# Allwinner_A13_SCH.net
KiCad netlist of a schematic drawn in Altium Designer
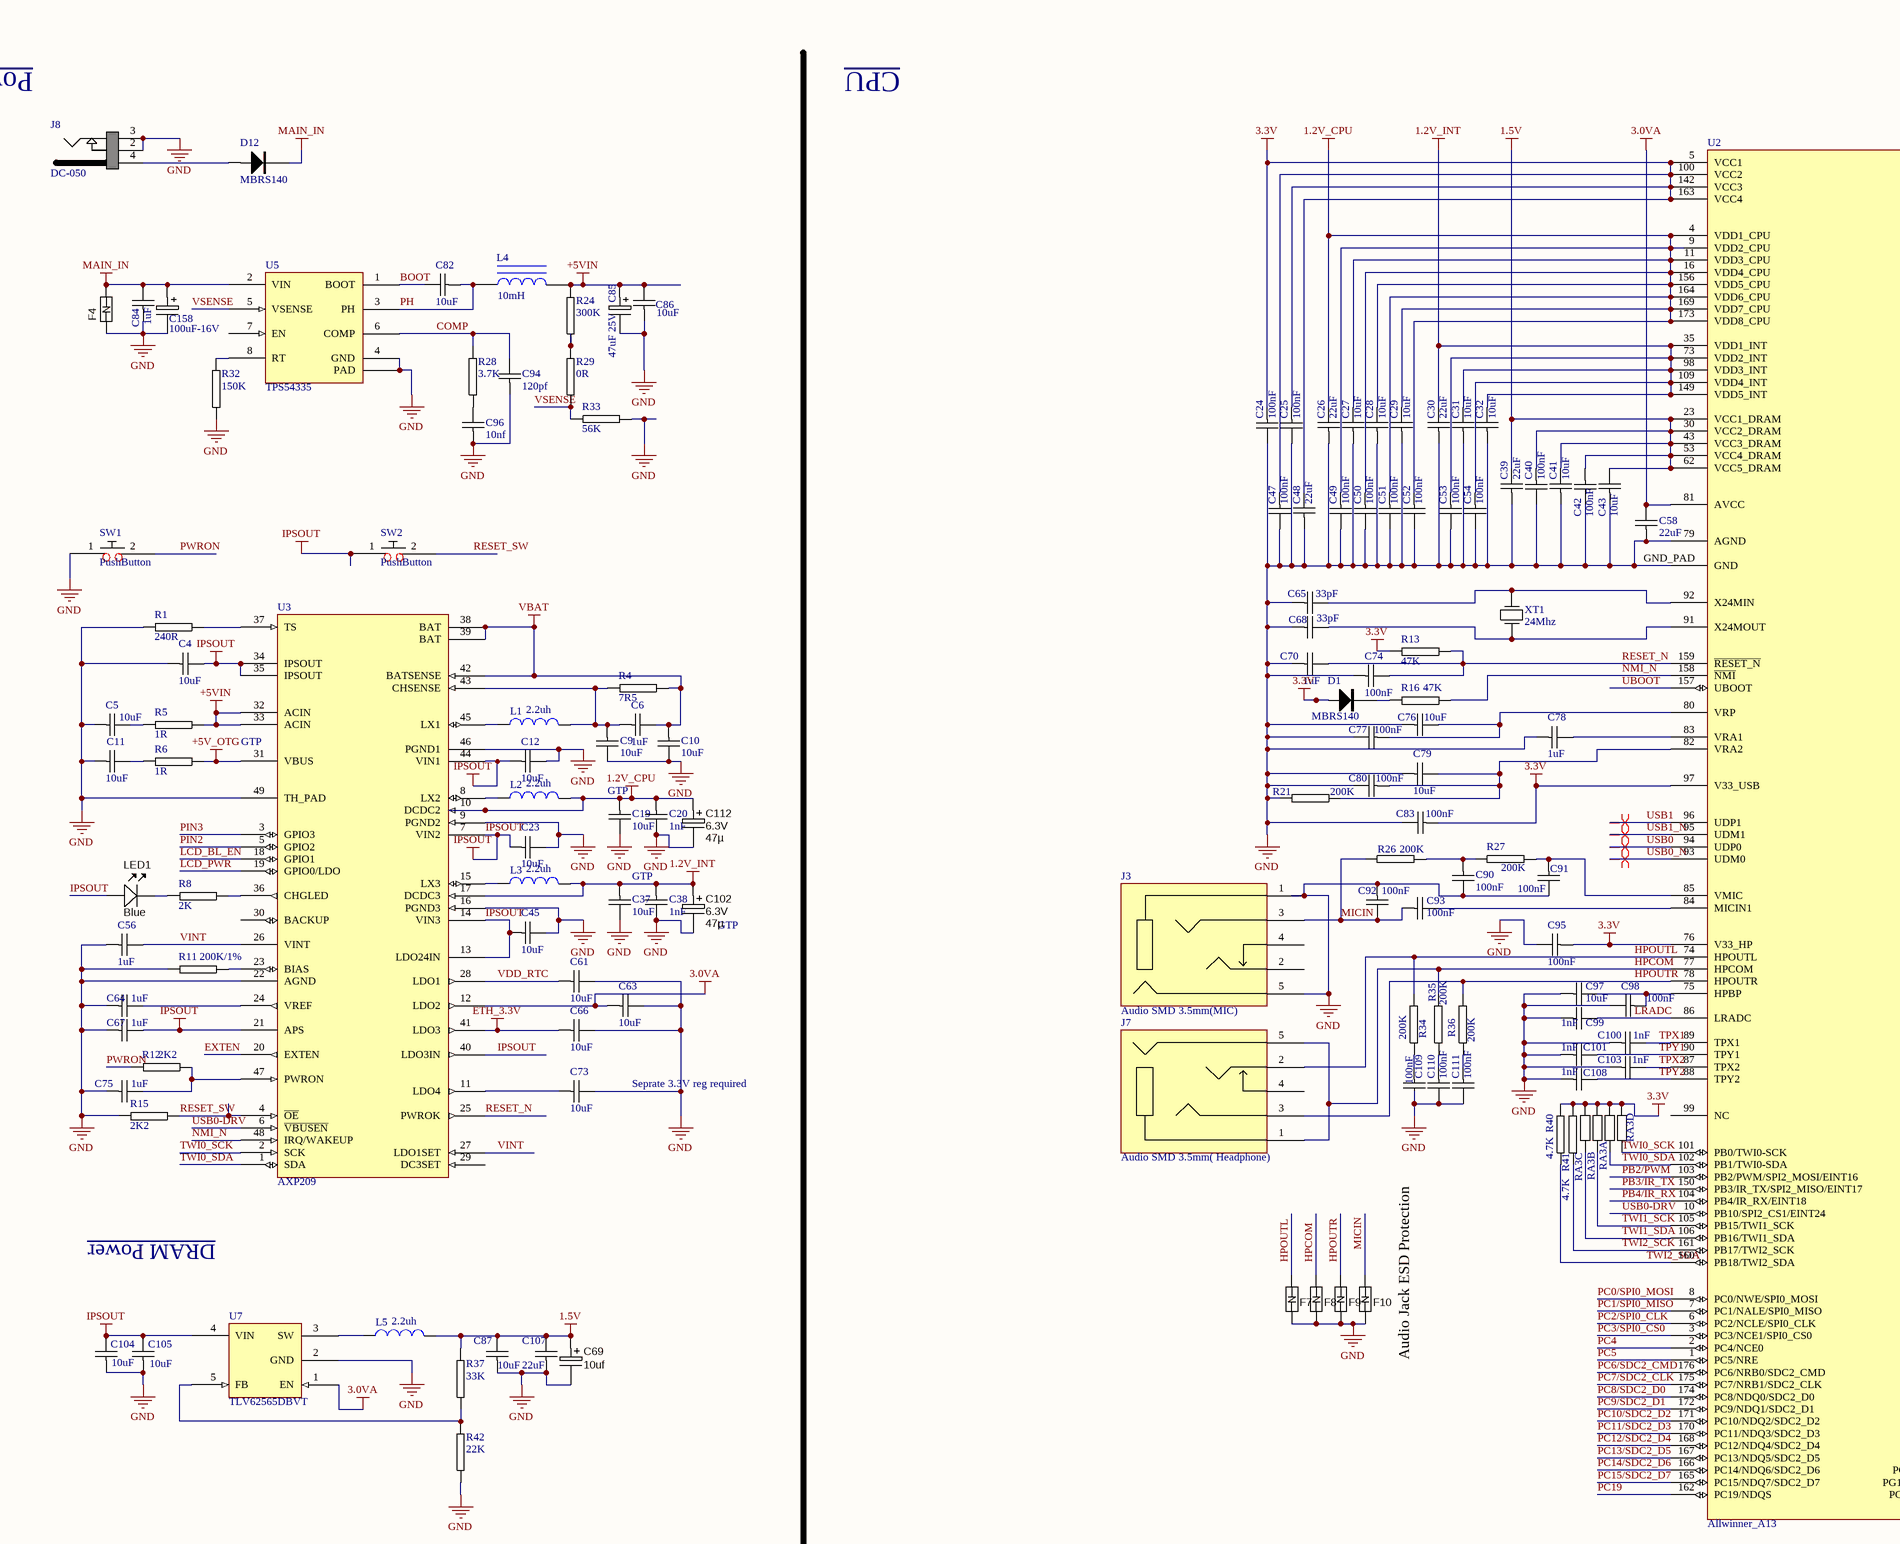
[diagram p0: Allwinner_A13_SCH.SchDoc, top left]
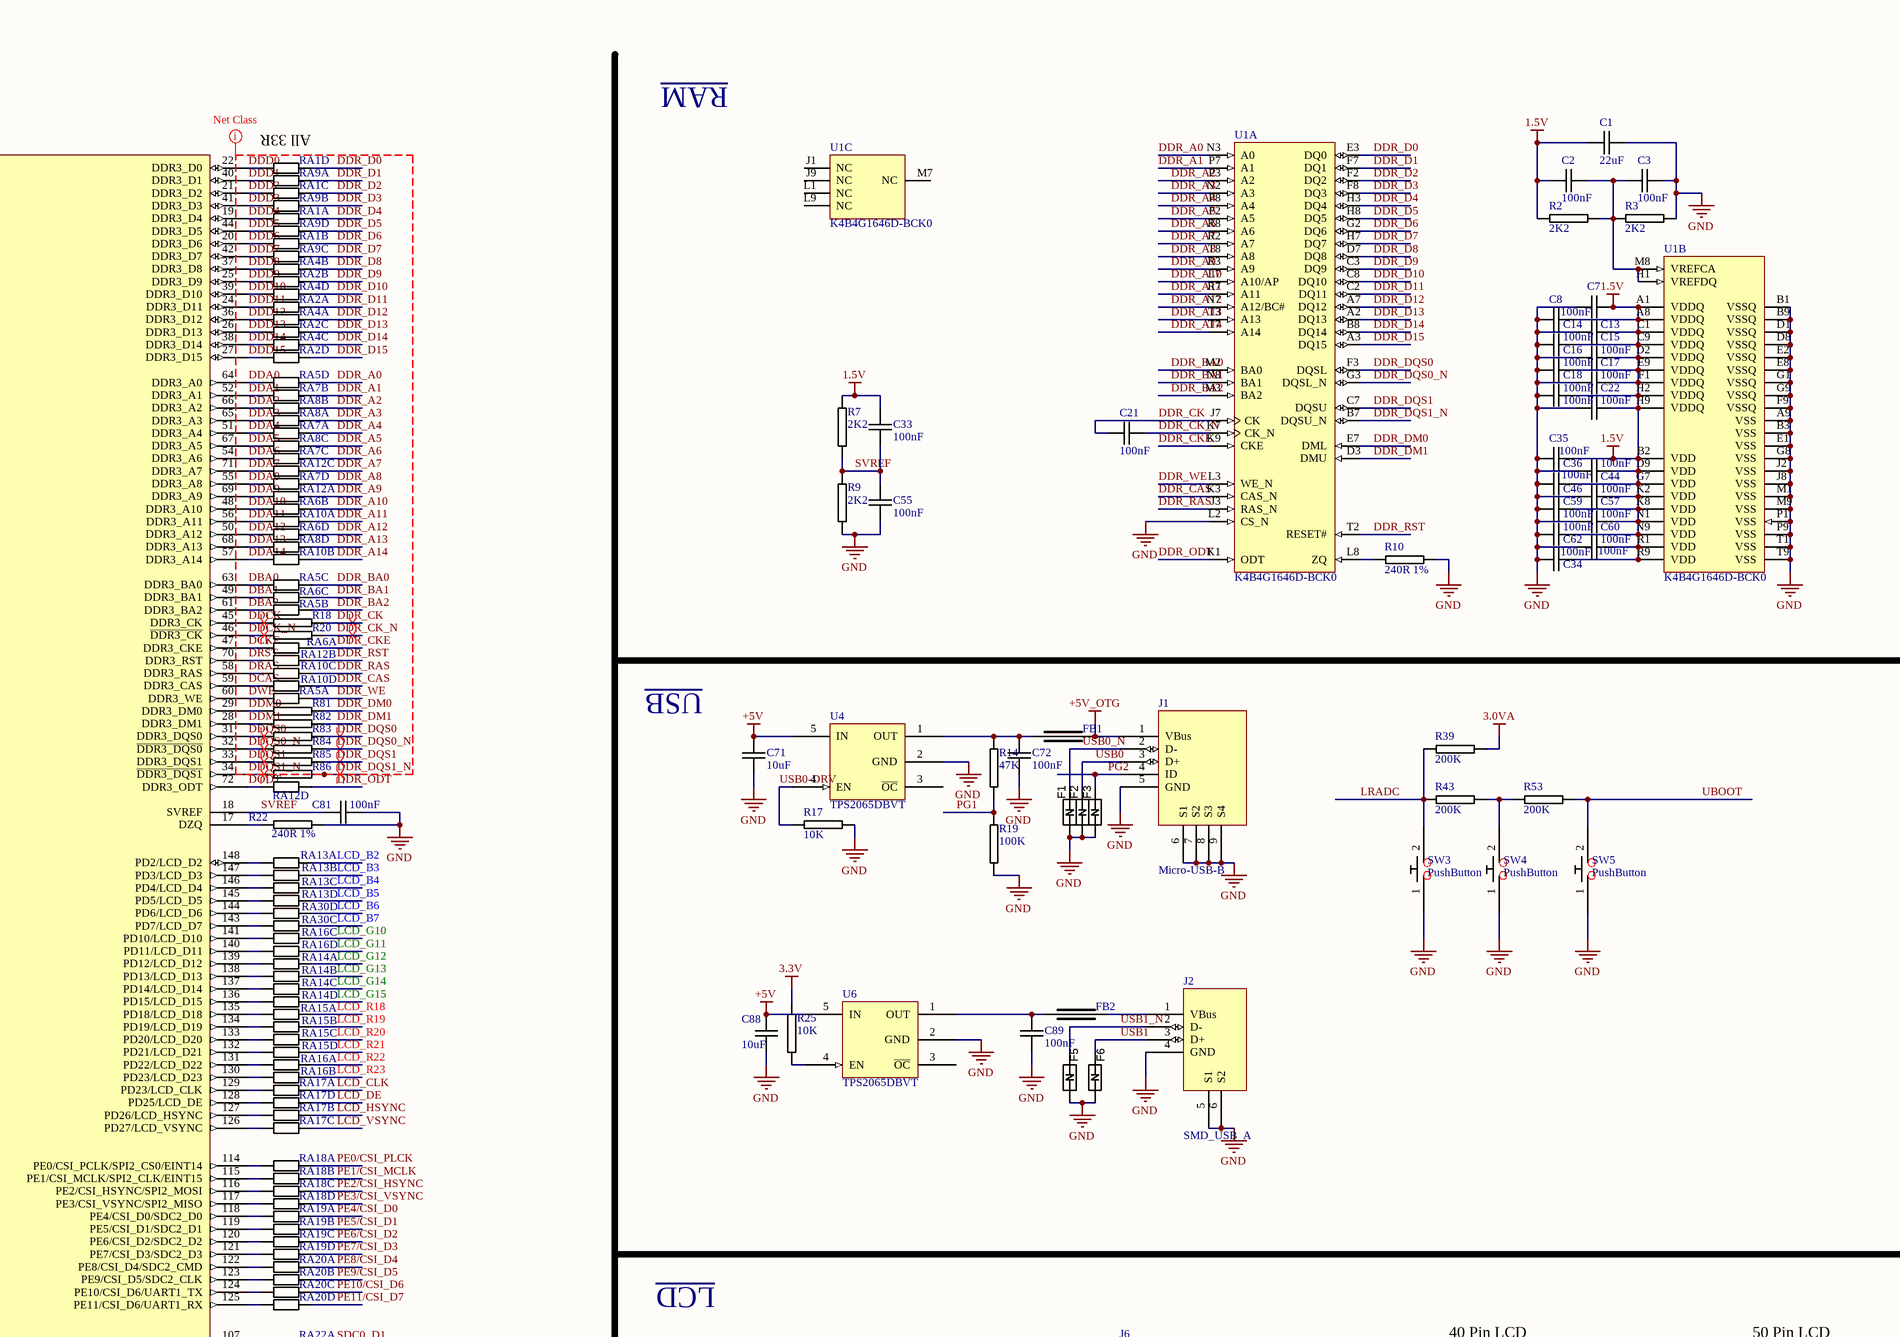
[diagram p1: Allwinner_A13_SCH.SchDoc, top right]
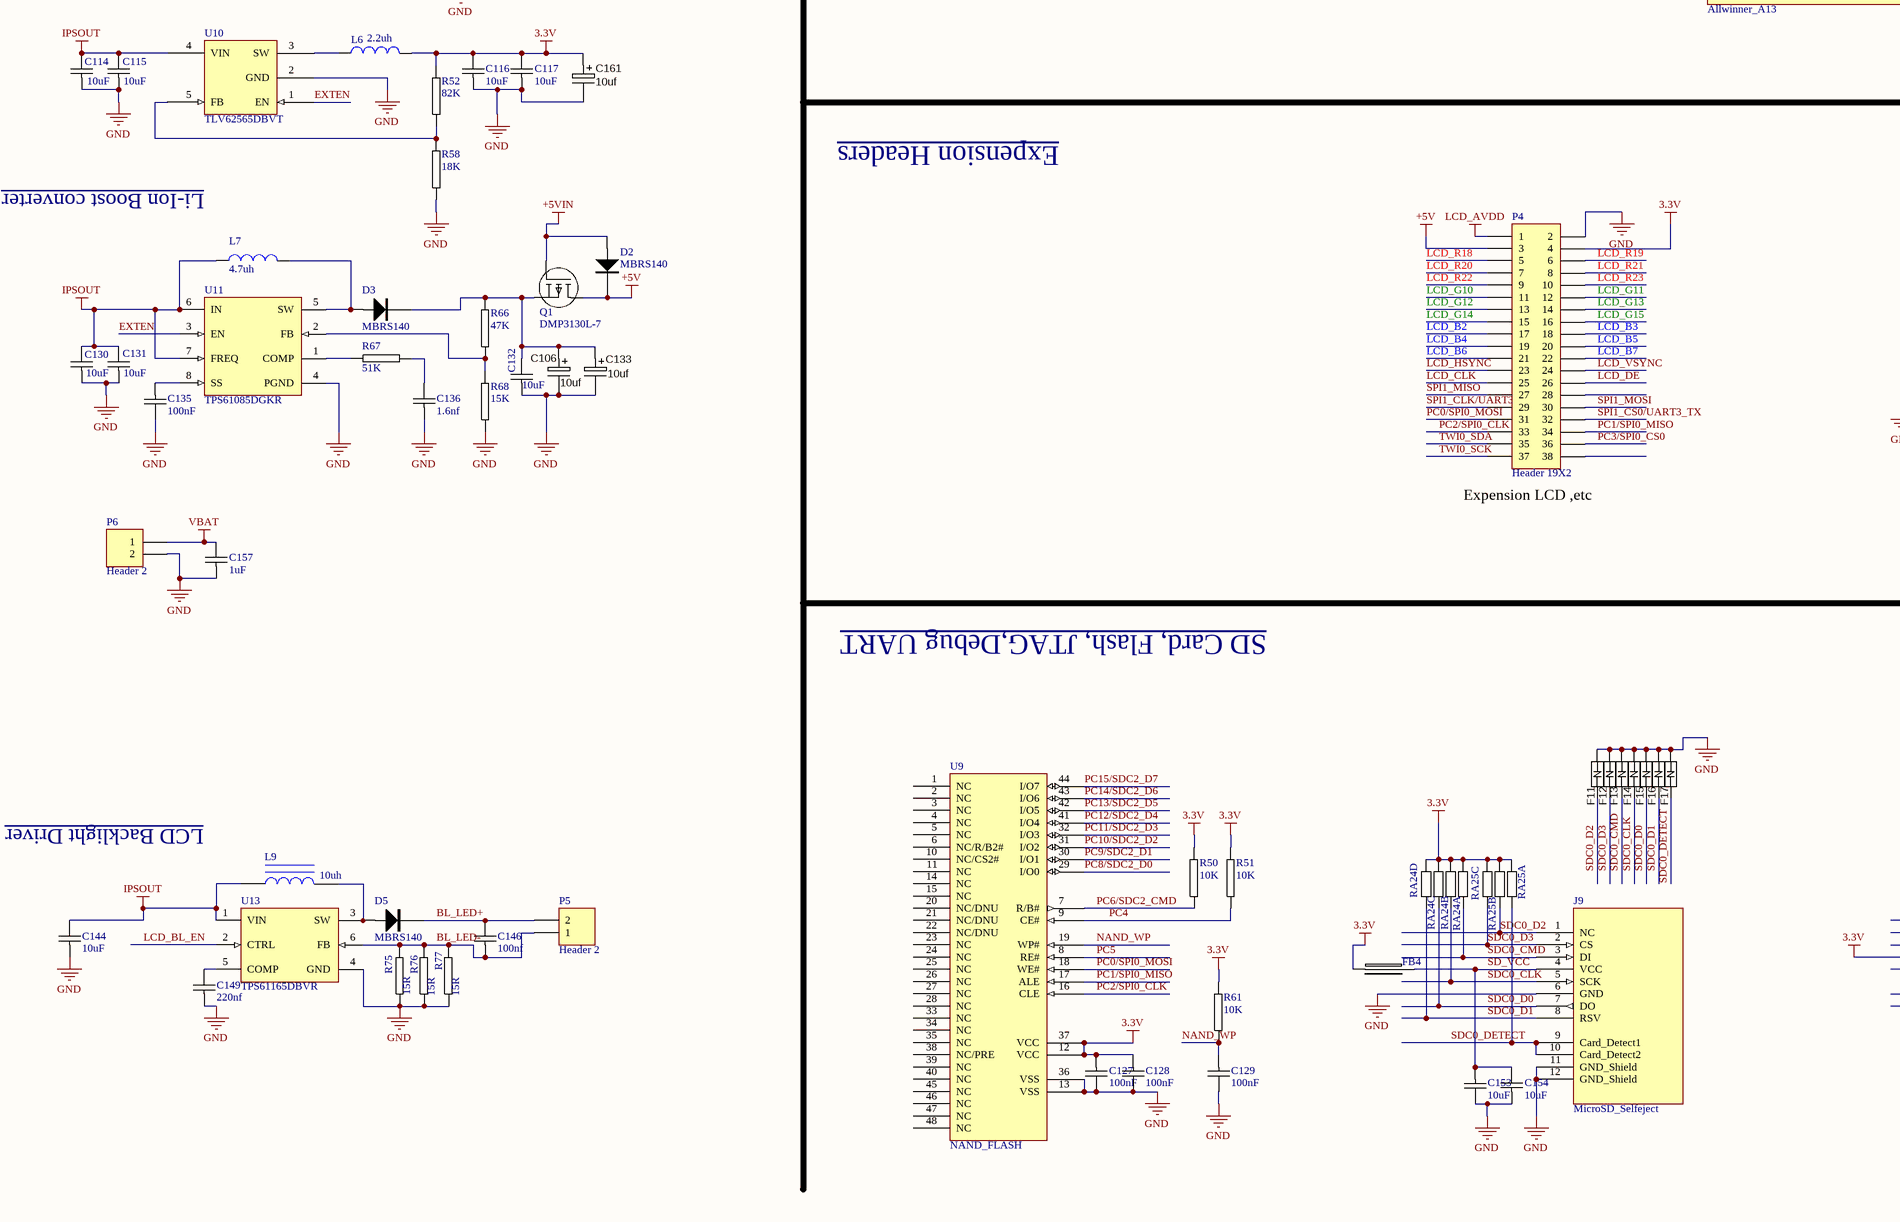
[diagram p2: Allwinner_A13_SCH.SchDoc, bottom left]
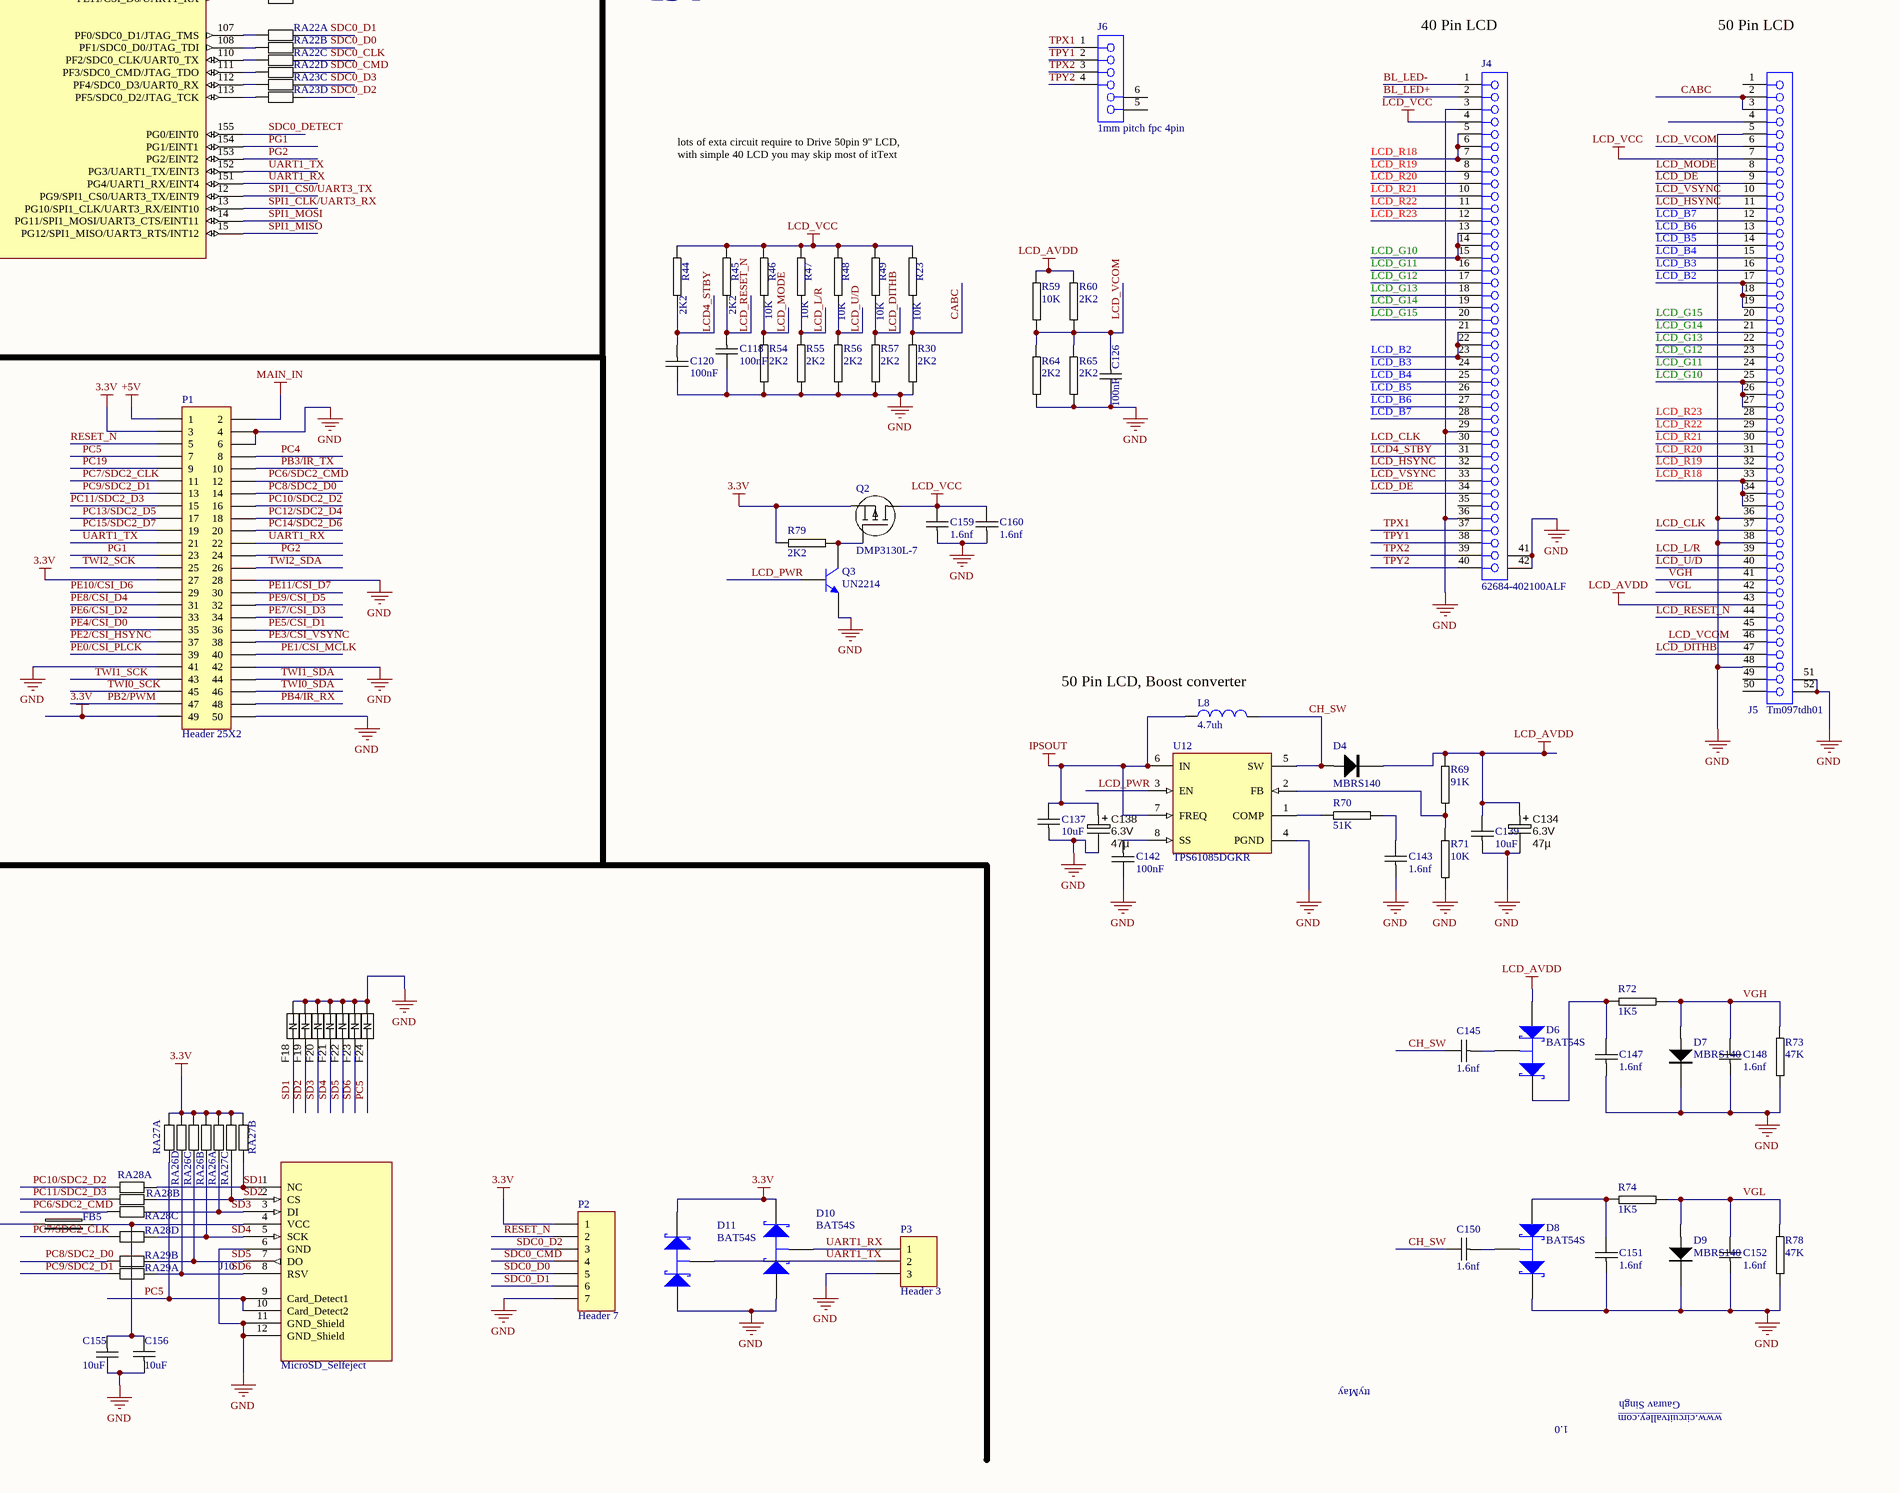
[diagram p3: Allwinner_A13_SCH.SchDoc, bottom right]

(export (version "E")
  (design (tool "Eeschema 10.0.6"))
  (components
    (comp (ref "C1")
      (value "22uF")
      (footprint "0603C-GENERIC")
      (description "CAPACITOR 0603 CERAMIC")
      (fields
        (field (name "MANUFACTURER") "Murata Electronics North America")
        (field (name "MANUFACTURER PART NUMBER") "GRM188R60J106ME47D")
      )
      (libsource (lib "Generic") (part "0603C-10UF-6V3-X5R-MUR"))
    )
    (comp (ref "C2")
      (value "100nF")
      (footprint "0603C-GENERIC")
      (description "CAPACITOR 0603 CERAMIC")
      (fields
        (field (name "MANUFACTURER") "Murata Electronics North America")
        (field (name "MANUFACTURER PART NUMBER") "GRM188R60J106ME47D")
      )
      (libsource (lib "Generic") (part "0603C-10UF-6V3-X5R-MUR"))
    )
    (comp (ref "C3")
      (value "100nF")
      (footprint "0603C-GENERIC")
      (description "CAPACITOR 0603 CERAMIC")
      (fields
        (field (name "MANUFACTURER") "Murata Electronics North America")
        (field (name "MANUFACTURER PART NUMBER") "GRM188R60J106ME47D")
      )
      (libsource (lib "Generic") (part "0603C-10UF-6V3-X5R-MUR"))
    )
    (comp (ref "C4")
      (value "10uF")
      (footprint "0603C-GENERIC")
      (description "CAPACITOR 0603 CERAMIC")
      (fields
        (field (name "MANUFACTURER") "Murata Electronics North America")
        (field (name "MANUFACTURER PART NUMBER") "GRM188R60J106ME47D")
      )
      (libsource (lib "Generic") (part "0603C-10UF-6V3-X5R-MUR"))
    )
    (comp (ref "C5")
      (value "10uF")
      (footprint "0603C-GENERIC")
      (description "CAPACITOR 0603 CERAMIC")
      (fields
        (field (name "MANUFACTURER") "Murata Electronics North America")
        (field (name "MANUFACTURER PART NUMBER") "GRM188R60J106ME47D")
      )
      (libsource (lib "Generic") (part "0603C-10UF-6V3-X5R-MUR"))
    )
    (comp (ref "C6")
      (value "1uF")
      (footprint "0603C-GENERIC")
      (description "CAPACITOR 0603 CERAMIC")
      (libsource (lib "Generic") (part "0603C-1UF-25V-X5R-SAM"))
    )
    (comp (ref "C7")
      (value "100nF")
      (footprint "0603C-GENERIC")
      (description "CAPACITOR 0603 CERAMIC")
      (fields
        (field (name "MANUFACTURER") "Murata Electronics North America")
        (field (name "MANUFACTURER PART NUMBER") "GRM188R60J106ME47D")
      )
      (libsource (lib "Generic") (part "0603C-10UF-6V3-X5R-MUR"))
    )
    (comp (ref "C8")
      (value "100nF")
      (footprint "0603C-GENERIC")
      (description "CAPACITOR 0603 CERAMIC")
      (fields
        (field (name "MANUFACTURER") "Murata Electronics North America")
        (field (name "MANUFACTURER PART NUMBER") "GRM188R60J106ME47D")
      )
      (libsource (lib "Generic") (part "0603C-10UF-6V3-X5R-MUR"))
    )
    (comp (ref "C9")
      (value "10uF")
      (footprint "0603C-GENERIC")
      (description "CAPACITOR 0603 CERAMIC")
      (fields
        (field (name "MANUFACTURER") "Murata Electronics North America")
        (field (name "MANUFACTURER PART NUMBER") "GRM188R60J106ME47D")
      )
      (libsource (lib "Generic") (part "0603C-10UF-6V3-X5R-MUR"))
    )
    (comp (ref "C10")
      (value "10uF")
      (footprint "0603C-GENERIC")
      (description "CAPACITOR 0603 CERAMIC")
      (fields
        (field (name "MANUFACTURER") "Murata Electronics North America")
        (field (name "MANUFACTURER PART NUMBER") "GRM188R60J106ME47D")
      )
      (libsource (lib "Generic") (part "0603C-10UF-6V3-X5R-MUR"))
    )
    (comp (ref "C11")
      (value "10uF")
      (footprint "0603C-GENERIC")
      (description "CAPACITOR 0603 CERAMIC")
      (fields
        (field (name "MANUFACTURER") "Murata Electronics North America")
        (field (name "MANUFACTURER PART NUMBER") "GRM188R60J106ME47D")
      )
      (libsource (lib "Generic") (part "0603C-10UF-6V3-X5R-MUR"))
    )
    (comp (ref "C12")
      (value "10uF")
      (footprint "0603C-GENERIC")
      (description "CAPACITOR 0603 CERAMIC")
      (fields
        (field (name "MANUFACTURER") "Murata Electronics North America")
        (field (name "MANUFACTURER PART NUMBER") "GRM188R60J106ME47D")
      )
      (libsource (lib "Generic") (part "0603C-10UF-6V3-X5R-MUR"))
    )
    (comp (ref "C13")
      (value "100nF")
      (footprint "0603C-GENERIC")
      (description "CAPACITOR 0603 CERAMIC")
      (fields
        (field (name "MANUFACTURER") "Murata Electronics North America")
        (field (name "MANUFACTURER PART NUMBER") "GRM188R60J106ME47D")
      )
      (libsource (lib "Generic") (part "0603C-10UF-6V3-X5R-MUR"))
    )
    (comp (ref "C14")
      (value "100nF")
      (footprint "0603C-GENERIC")
      (description "CAPACITOR 0603 CERAMIC")
      (fields
        (field (name "MANUFACTURER") "Murata Electronics North America")
        (field (name "MANUFACTURER PART NUMBER") "GRM188R60J106ME47D")
      )
      (libsource (lib "Generic") (part "0603C-10UF-6V3-X5R-MUR"))
    )
    (comp (ref "C15")
      (value "100nF")
      (footprint "0603C-GENERIC")
      (description "CAPACITOR 0603 CERAMIC")
      (fields
        (field (name "MANUFACTURER") "Murata Electronics North America")
        (field (name "MANUFACTURER PART NUMBER") "GRM188R60J106ME47D")
      )
      (libsource (lib "Generic") (part "0603C-10UF-6V3-X5R-MUR"))
    )
    (comp (ref "C16")
      (value "100nF")
      (footprint "0603C-GENERIC")
      (description "CAPACITOR 0603 CERAMIC")
      (fields
        (field (name "MANUFACTURER") "Murata Electronics North America")
        (field (name "MANUFACTURER PART NUMBER") "GRM188R60J106ME47D")
      )
      (libsource (lib "Generic") (part "0603C-10UF-6V3-X5R-MUR"))
    )
    (comp (ref "C17")
      (value "100nF")
      (footprint "0603C-GENERIC")
      (description "CAPACITOR 0603 CERAMIC")
      (fields
        (field (name "MANUFACTURER") "Murata Electronics North America")
        (field (name "MANUFACTURER PART NUMBER") "GRM188R60J106ME47D")
      )
      (libsource (lib "Generic") (part "0603C-10UF-6V3-X5R-MUR"))
    )
    (comp (ref "C18")
      (value "100nF")
      (footprint "0603C-GENERIC")
      (description "CAPACITOR 0603 CERAMIC")
      (fields
        (field (name "MANUFACTURER") "Murata Electronics North America")
        (field (name "MANUFACTURER PART NUMBER") "GRM188R60J106ME47D")
      )
      (libsource (lib "Generic") (part "0603C-10UF-6V3-X5R-MUR"))
    )
    (comp (ref "C19")
      (value "10uF")
      (footprint "0603C-GENERIC")
      (description "CAPACITOR 0603 CERAMIC")
      (fields
        (field (name "MANUFACTURER") "Murata Electronics North America")
        (field (name "MANUFACTURER PART NUMBER") "GRM188R60J106ME47D")
      )
      (libsource (lib "Generic") (part "0603C-10UF-6V3-X5R-MUR"))
    )
    (comp (ref "C20")
      (value "1nF")
      (footprint "0603C-GENERIC")
      (description "CAPACITOR 0603 CERAMIC")
      (libsource (lib "Generic") (part "0603C-1NF-50V-X7R-KEM"))
    )
    (comp (ref "C21")
      (value "100nF")
      (footprint "0603C-GENERIC")
      (description "CAPACITOR 0603 CERAMIC")
      (fields
        (field (name "MANUFACTURER") "Murata Electronics North America")
        (field (name "MANUFACTURER PART NUMBER") "GRM188R60J106ME47D")
      )
      (libsource (lib "Generic") (part "0603C-10UF-6V3-X5R-MUR"))
    )
    (comp (ref "C22")
      (value "100nF")
      (footprint "0603C-GENERIC")
      (description "CAPACITOR 0603 CERAMIC")
      (fields
        (field (name "MANUFACTURER") "Murata Electronics North America")
        (field (name "MANUFACTURER PART NUMBER") "GRM188R60J106ME47D")
      )
      (libsource (lib "Generic") (part "0603C-10UF-6V3-X5R-MUR"))
    )
    (comp (ref "C23")
      (value "10uF")
      (footprint "0603C-GENERIC")
      (description "CAPACITOR 0603 CERAMIC")
      (fields
        (field (name "MANUFACTURER") "Murata Electronics North America")
        (field (name "MANUFACTURER PART NUMBER") "GRM188R60J106ME47D")
      )
      (libsource (lib "Generic") (part "0603C-10UF-6V3-X5R-MUR"))
    )
    (comp (ref "C24")
      (value "100nF")
      (footprint "0603C-GENERIC")
      (description "CAPACITOR 0603 CERAMIC")
      (fields
        (field (name "MANUFACTURER PART NUMBER") "C1608X7R1E104K")
        (field (name "MANUFACTURER") "TDK Corporation")
      )
      (libsource (lib "Generic") (part "0603C-100NF-25V-X7R-TDK"))
    )
    (comp (ref "C25")
      (value "100nF")
      (footprint "0603C-GENERIC")
      (description "CAPACITOR 0603 CERAMIC")
      (fields
        (field (name "MANUFACTURER PART NUMBER") "C1608X7R1E104K")
        (field (name "MANUFACTURER") "TDK Corporation")
      )
      (libsource (lib "Generic") (part "0603C-100NF-25V-X7R-TDK"))
    )
    (comp (ref "C26")
      (value "22uF")
      (footprint "0603C-GENERIC")
      (description "CAPACITOR 0603 CERAMIC")
      (fields
        (field (name "MANUFACTURER") "Murata Electronics North America")
        (field (name "MANUFACTURER PART NUMBER") "GRM188R60J106ME47D")
      )
      (libsource (lib "Generic") (part "0603C-10UF-6V3-X5R-MUR"))
    )
    (comp (ref "C27")
      (value "10uF")
      (footprint "0603C-GENERIC")
      (description "CAPACITOR 0603 CERAMIC")
      (fields
        (field (name "MANUFACTURER") "Murata Electronics North America")
        (field (name "MANUFACTURER PART NUMBER") "GRM188R60J106ME47D")
      )
      (libsource (lib "Generic") (part "0603C-10UF-6V3-X5R-MUR"))
    )
    (comp (ref "C28")
      (value "10uF")
      (footprint "0603C-GENERIC")
      (description "CAPACITOR 0603 CERAMIC")
      (fields
        (field (name "MANUFACTURER") "Murata Electronics North America")
        (field (name "MANUFACTURER PART NUMBER") "GRM188R60J106ME47D")
      )
      (libsource (lib "Generic") (part "0603C-10UF-6V3-X5R-MUR"))
    )
    (comp (ref "C29")
      (value "10uF")
      (footprint "0603C-GENERIC")
      (description "CAPACITOR 0603 CERAMIC")
      (fields
        (field (name "MANUFACTURER") "Murata Electronics North America")
        (field (name "MANUFACTURER PART NUMBER") "GRM188R60J106ME47D")
      )
      (libsource (lib "Generic") (part "0603C-10UF-6V3-X5R-MUR"))
    )
    (comp (ref "C30")
      (value "22uF")
      (footprint "0603C-GENERIC")
      (description "CAPACITOR 0603 CERAMIC")
      (fields
        (field (name "MANUFACTURER") "Murata Electronics North America")
        (field (name "MANUFACTURER PART NUMBER") "GRM188R60J106ME47D")
      )
      (libsource (lib "Generic") (part "0603C-10UF-6V3-X5R-MUR"))
    )
    (comp (ref "C31")
      (value "10uF")
      (footprint "0603C-GENERIC")
      (description "CAPACITOR 0603 CERAMIC")
      (fields
        (field (name "MANUFACTURER") "Murata Electronics North America")
        (field (name "MANUFACTURER PART NUMBER") "GRM188R60J106ME47D")
      )
      (libsource (lib "Generic") (part "0603C-10UF-6V3-X5R-MUR"))
    )
    (comp (ref "C32")
      (value "10uF")
      (footprint "0603C-GENERIC")
      (description "CAPACITOR 0603 CERAMIC")
      (fields
        (field (name "MANUFACTURER") "Murata Electronics North America")
        (field (name "MANUFACTURER PART NUMBER") "GRM188R60J106ME47D")
      )
      (libsource (lib "Generic") (part "0603C-10UF-6V3-X5R-MUR"))
    )
    (comp (ref "C33")
      (value "100nF")
      (footprint "0603C-GENERIC")
      (description "CAPACITOR 0603 CERAMIC")
      (fields
        (field (name "MANUFACTURER") "Murata Electronics North America")
        (field (name "MANUFACTURER PART NUMBER") "GRM188R60J106ME47D")
      )
      (libsource (lib "Generic") (part "0603C-10UF-6V3-X5R-MUR"))
    )
    (comp (ref "C34")
      (value "100nF")
      (footprint "0603C-GENERIC")
      (description "CAPACITOR 0603 CERAMIC")
      (fields
        (field (name "MANUFACTURER") "Murata Electronics North America")
        (field (name "MANUFACTURER PART NUMBER") "GRM188R60J106ME47D")
      )
      (libsource (lib "Generic") (part "0603C-10UF-6V3-X5R-MUR"))
    )
    (comp (ref "C35")
      (value "100nF")
      (footprint "0603C-GENERIC")
      (description "CAPACITOR 0603 CERAMIC")
      (fields
        (field (name "MANUFACTURER") "Murata Electronics North America")
        (field (name "MANUFACTURER PART NUMBER") "GRM188R60J106ME47D")
      )
      (libsource (lib "Generic") (part "0603C-10UF-6V3-X5R-MUR"))
    )
    (comp (ref "C36")
      (value "100nF")
      (footprint "0603C-GENERIC")
      (description "CAPACITOR 0603 CERAMIC")
      (fields
        (field (name "MANUFACTURER") "Murata Electronics North America")
        (field (name "MANUFACTURER PART NUMBER") "GRM188R60J106ME47D")
      )
      (libsource (lib "Generic") (part "0603C-10UF-6V3-X5R-MUR"))
    )
    (comp (ref "C37")
      (value "10uF")
      (footprint "0603C-GENERIC")
      (description "CAPACITOR 0603 CERAMIC")
      (fields
        (field (name "MANUFACTURER") "Murata Electronics North America")
        (field (name "MANUFACTURER PART NUMBER") "GRM188R60J106ME47D")
      )
      (libsource (lib "Generic") (part "0603C-10UF-6V3-X5R-MUR"))
    )
    (comp (ref "C38")
      (value "1nF")
      (footprint "0603C-GENERIC")
      (description "CAPACITOR 0603 CERAMIC")
      (libsource (lib "Generic") (part "0603C-1NF-50V-X7R-KEM"))
    )
    (comp (ref "C39")
      (value "22uF")
      (footprint "0603C-GENERIC")
      (description "CAPACITOR 0603 CERAMIC")
      (fields
        (field (name "MANUFACTURER") "Murata Electronics North America")
        (field (name "MANUFACTURER PART NUMBER") "GRM188R60J106ME47D")
      )
      (libsource (lib "Generic") (part "0603C-10UF-6V3-X5R-MUR"))
    )
    (comp (ref "C40")
      (value "100nF")
      (footprint "0603C-GENERIC")
      (description "CAPACITOR 0603 CERAMIC")
      (fields
        (field (name "MANUFACTURER PART NUMBER") "C1608X7R1E104K")
        (field (name "MANUFACTURER") "TDK Corporation")
      )
      (libsource (lib "Generic") (part "0603C-100NF-25V-X7R-TDK"))
    )
    (comp (ref "C41")
      (value "10uF")
      (footprint "0603C-GENERIC")
      (description "CAPACITOR 0603 CERAMIC")
      (fields
        (field (name "MANUFACTURER") "Murata Electronics North America")
        (field (name "MANUFACTURER PART NUMBER") "GRM188R60J106ME47D")
      )
      (libsource (lib "Generic") (part "0603C-10UF-6V3-X5R-MUR"))
    )
    (comp (ref "C42")
      (value "100nF")
      (footprint "0603C-GENERIC")
      (description "CAPACITOR 0603 CERAMIC")
      (fields
        (field (name "MANUFACTURER PART NUMBER") "C1608X7R1E104K")
        (field (name "MANUFACTURER") "TDK Corporation")
      )
      (libsource (lib "Generic") (part "0603C-100NF-25V-X7R-TDK"))
    )
    (comp (ref "C43")
      (value "10uF")
      (footprint "0603C-GENERIC")
      (description "CAPACITOR 0603 CERAMIC")
      (fields
        (field (name "MANUFACTURER") "Murata Electronics North America")
        (field (name "MANUFACTURER PART NUMBER") "GRM188R60J106ME47D")
      )
      (libsource (lib "Generic") (part "0603C-10UF-6V3-X5R-MUR"))
    )
    (comp (ref "C44")
      (value "100nF")
      (footprint "0603C-GENERIC")
      (description "CAPACITOR 0603 CERAMIC")
      (fields
        (field (name "MANUFACTURER") "Murata Electronics North America")
        (field (name "MANUFACTURER PART NUMBER") "GRM188R60J106ME47D")
      )
      (libsource (lib "Generic") (part "0603C-10UF-6V3-X5R-MUR"))
    )
    (comp (ref "C45")
      (value "10uF")
      (footprint "0603C-GENERIC")
      (description "CAPACITOR 0603 CERAMIC")
      (fields
        (field (name "MANUFACTURER") "Murata Electronics North America")
        (field (name "MANUFACTURER PART NUMBER") "GRM188R60J106ME47D")
      )
      (libsource (lib "Generic") (part "0603C-10UF-6V3-X5R-MUR"))
    )
    (comp (ref "C46")
      (value "100nF")
      (footprint "0603C-GENERIC")
      (description "CAPACITOR 0603 CERAMIC")
      (fields
        (field (name "MANUFACTURER") "Murata Electronics North America")
        (field (name "MANUFACTURER PART NUMBER") "GRM188R60J106ME47D")
      )
      (libsource (lib "Generic") (part "0603C-10UF-6V3-X5R-MUR"))
    )
    (comp (ref "C47")
      (value "100nF")
      (footprint "0603C-GENERIC")
      (description "CAPACITOR 0603 CERAMIC")
      (fields
        (field (name "MANUFACTURER PART NUMBER") "C1608X7R1E104K")
        (field (name "MANUFACTURER") "TDK Corporation")
      )
      (libsource (lib "Generic") (part "0603C-100NF-25V-X7R-TDK"))
    )
    (comp (ref "C48")
      (value "22uF")
      (footprint "0603C-GENERIC")
      (description "CAPACITOR 0603 CERAMIC")
      (fields
        (field (name "MANUFACTURER") "Murata Electronics North America")
        (field (name "MANUFACTURER PART NUMBER") "GRM188R60J106ME47D")
      )
      (libsource (lib "Generic") (part "0603C-10UF-6V3-X5R-MUR"))
    )
    (comp (ref "C49")
      (value "100nF")
      (footprint "0603C-GENERIC")
      (description "CAPACITOR 0603 CERAMIC")
      (fields
        (field (name "MANUFACTURER PART NUMBER") "C1608X7R1E104K")
        (field (name "MANUFACTURER") "TDK Corporation")
      )
      (libsource (lib "Generic") (part "0603C-100NF-25V-X7R-TDK"))
    )
    (comp (ref "C50")
      (value "100nF")
      (footprint "0603C-GENERIC")
      (description "CAPACITOR 0603 CERAMIC")
      (fields
        (field (name "MANUFACTURER PART NUMBER") "C1608X7R1E104K")
        (field (name "MANUFACTURER") "TDK Corporation")
      )
      (libsource (lib "Generic") (part "0603C-100NF-25V-X7R-TDK"))
    )
    (comp (ref "C51")
      (value "100nF")
      (footprint "0603C-GENERIC")
      (description "CAPACITOR 0603 CERAMIC")
      (fields
        (field (name "MANUFACTURER PART NUMBER") "C1608X7R1E104K")
        (field (name "MANUFACTURER") "TDK Corporation")
      )
      (libsource (lib "Generic") (part "0603C-100NF-25V-X7R-TDK"))
    )
    (comp (ref "C52")
      (value "100nF")
      (footprint "0603C-GENERIC")
      (description "CAPACITOR 0603 CERAMIC")
      (fields
        (field (name "MANUFACTURER PART NUMBER") "C1608X7R1E104K")
        (field (name "MANUFACTURER") "TDK Corporation")
      )
      (libsource (lib "Generic") (part "0603C-100NF-25V-X7R-TDK"))
    )
    (comp (ref "C53")
      (value "100nF")
      (footprint "0603C-GENERIC")
      (description "CAPACITOR 0603 CERAMIC")
      (fields
        (field (name "MANUFACTURER PART NUMBER") "C1608X7R1E104K")
        (field (name "MANUFACTURER") "TDK Corporation")
      )
      (libsource (lib "Generic") (part "0603C-100NF-25V-X7R-TDK"))
    )
    (comp (ref "C54")
      (value "100nF")
      (footprint "0603C-GENERIC")
      (description "CAPACITOR 0603 CERAMIC")
      (fields
        (field (name "MANUFACTURER PART NUMBER") "C1608X7R1E104K")
        (field (name "MANUFACTURER") "TDK Corporation")
      )
      (libsource (lib "Generic") (part "0603C-100NF-25V-X7R-TDK"))
    )
    (comp (ref "C55")
      (value "100nF")
      (footprint "0603C-GENERIC")
      (description "CAPACITOR 0603 CERAMIC")
      (fields
        (field (name "MANUFACTURER") "Murata Electronics North America")
        (field (name "MANUFACTURER PART NUMBER") "GRM188R60J106ME47D")
      )
      (libsource (lib "Generic") (part "0603C-10UF-6V3-X5R-MUR"))
    )
    (comp (ref "C56")
      (value "1uF")
      (footprint "0603C-GENERIC")
      (description "CAPACITOR 0603 CERAMIC")
      (libsource (lib "Generic") (part "0603C-1UF-25V-X5R-SAM"))
    )
    (comp (ref "C57")
      (value "100nF")
      (footprint "0603C-GENERIC")
      (description "CAPACITOR 0603 CERAMIC")
      (fields
        (field (name "MANUFACTURER") "Murata Electronics North America")
        (field (name "MANUFACTURER PART NUMBER") "GRM188R60J106ME47D")
      )
      (libsource (lib "Generic") (part "0603C-10UF-6V3-X5R-MUR"))
    )
    (comp (ref "C58")
      (value "22uF")
      (footprint "0603C-GENERIC")
      (description "CAPACITOR 0603 CERAMIC")
      (fields
        (field (name "MANUFACTURER") "Murata Electronics North America")
        (field (name "MANUFACTURER PART NUMBER") "GRM188R60J106ME47D")
      )
      (libsource (lib "Generic") (part "0603C-10UF-6V3-X5R-MUR"))
    )
    (comp (ref "C59")
      (value "100nF")
      (footprint "0603C-GENERIC")
      (description "CAPACITOR 0603 CERAMIC")
      (fields
        (field (name "MANUFACTURER") "Murata Electronics North America")
        (field (name "MANUFACTURER PART NUMBER") "GRM188R60J106ME47D")
      )
      (libsource (lib "Generic") (part "0603C-10UF-6V3-X5R-MUR"))
    )
    (comp (ref "C60")
      (value "100nF")
      (footprint "0603C-GENERIC")
      (description "CAPACITOR 0603 CERAMIC")
      (fields
        (field (name "MANUFACTURER") "Murata Electronics North America")
        (field (name "MANUFACTURER PART NUMBER") "GRM188R60J106ME47D")
      )
      (libsource (lib "Generic") (part "0603C-10UF-6V3-X5R-MUR"))
    )
    (comp (ref "C61")
      (value "10uF")
      (footprint "0603C-GENERIC")
      (description "CAPACITOR 0603 CERAMIC")
      (fields
        (field (name "MANUFACTURER") "Murata Electronics North America")
        (field (name "MANUFACTURER PART NUMBER") "GRM188R60J106ME47D")
      )
      (libsource (lib "Generic") (part "0603C-10UF-6V3-X5R-MUR"))
    )
    (comp (ref "C62")
      (value "100nF")
      (footprint "0603C-GENERIC")
      (description "CAPACITOR 0603 CERAMIC")
      (fields
        (field (name "MANUFACTURER") "Murata Electronics North America")
        (field (name "MANUFACTURER PART NUMBER") "GRM188R60J106ME47D")
      )
      (libsource (lib "Generic") (part "0603C-10UF-6V3-X5R-MUR"))
    )
    (comp (ref "C63")
      (value "10uF")
      (footprint "0603C-GENERIC")
      (description "CAPACITOR 0603 CERAMIC")
      (fields
        (field (name "MANUFACTURER") "Murata Electronics North America")
        (field (name "MANUFACTURER PART NUMBER") "GRM188R60J106ME47D")
      )
      (libsource (lib "Generic") (part "0603C-10UF-6V3-X5R-MUR"))
    )
    (comp (ref "C64")
      (value "1uF")
      (footprint "0603C-GENERIC")
      (description "CAPACITOR 0603 CERAMIC")
      (libsource (lib "Generic") (part "0603C-1UF-25V-X5R-SAM"))
    )
    (comp (ref "C65")
      (value "33pF")
      (footprint "0603C-GENERIC")
      (description "CAPACITOR 0603 CERAMIC")
      (libsource (lib "Generic") (part "0603C-33PF-50V-C0G-PAN"))
    )
    (comp (ref "C66")
      (value "10uF")
      (footprint "0603C-GENERIC")
      (description "CAPACITOR 0603 CERAMIC")
      (fields
        (field (name "MANUFACTURER") "Murata Electronics North America")
        (field (name "MANUFACTURER PART NUMBER") "GRM188R60J106ME47D")
      )
      (libsource (lib "Generic") (part "0603C-10UF-6V3-X5R-MUR"))
    )
    (comp (ref "C67")
      (value "1uF")
      (footprint "0603C-GENERIC")
      (description "CAPACITOR 0603 CERAMIC")
      (libsource (lib "Generic") (part "0603C-1UF-25V-X5R-SAM"))
    )
    (comp (ref "C68")
      (value "33pF")
      (footprint "0603C-GENERIC")
      (description "CAPACITOR 0603 CERAMIC")
      (libsource (lib "Generic") (part "0603C-33PF-50V-C0G-PAN"))
    )
    (comp (ref "C69")
      (value "10uf")
      (footprint "CAPMP3528X210N")
      (description "Capacitor SMD Tantalum 47uF 20% 6.3V 1210")
      (fields (field (name "TOLERANCE") "±20%"))
      (libsource (lib "PBL - Capacitors") (part "CAPT_47u_1210_6V3"))
    )
    (comp (ref "C70")
      (value "1uF")
      (footprint "0603C-GENERIC")
      (description "CAPACITOR 0603 CERAMIC")
      (libsource (lib "Generic") (part "0603C-1UF-25V-X5R-SAM"))
    )
    (comp (ref "C71")
      (value "10uF")
      (footprint "0603C-GENERIC")
      (description "CAPACITOR 0603 CERAMIC")
      (fields
        (field (name "MANUFACTURER") "Murata Electronics North America")
        (field (name "MANUFACTURER PART NUMBER") "GRM188R60J106ME47D")
      )
      (libsource (lib "Generic") (part "0603C-10UF-6V3-X5R-MUR"))
    )
    (comp (ref "C72")
      (value "100nF")
      (footprint "0603C-GENERIC")
      (description "CAPACITOR 0603 CERAMIC")
      (fields
        (field (name "MANUFACTURER") "Murata Electronics North America")
        (field (name "MANUFACTURER PART NUMBER") "GRM188R60J106ME47D")
      )
      (libsource (lib "Generic") (part "0603C-10UF-6V3-X5R-MUR"))
    )
    (comp (ref "C73")
      (value "10uF")
      (footprint "0603C-GENERIC")
      (description "CAPACITOR 0603 CERAMIC")
      (fields
        (field (name "MANUFACTURER") "Murata Electronics North America")
        (field (name "MANUFACTURER PART NUMBER") "GRM188R60J106ME47D")
      )
      (libsource (lib "Generic") (part "0603C-10UF-6V3-X5R-MUR"))
    )
    (comp (ref "C74")
      (value "100nF")
      (footprint "0603C-GENERIC")
      (description "CAPACITOR 0603 CERAMIC")
      (fields
        (field (name "MANUFACTURER PART NUMBER") "C1608X7R1E104K")
        (field (name "MANUFACTURER") "TDK Corporation")
      )
      (libsource (lib "Generic") (part "0603C-100NF-25V-X7R-TDK"))
    )
    (comp (ref "C75")
      (value "1uF")
      (footprint "0603C-GENERIC")
      (description "CAPACITOR 0603 CERAMIC")
      (libsource (lib "Generic") (part "0603C-1UF-25V-X5R-SAM"))
    )
    (comp (ref "C76")
      (value "10uF")
      (footprint "0603C-GENERIC")
      (description "CAPACITOR 0603 CERAMIC")
      (fields
        (field (name "MANUFACTURER") "Murata Electronics North America")
        (field (name "MANUFACTURER PART NUMBER") "GRM188R60J106ME47D")
      )
      (libsource (lib "Generic") (part "0603C-10UF-6V3-X5R-MUR"))
    )
    (comp (ref "C77")
      (value "100nF")
      (footprint "0603C-GENERIC")
      (description "CAPACITOR 0603 CERAMIC")
      (fields
        (field (name "MANUFACTURER PART NUMBER") "C1608X7R1E104K")
        (field (name "MANUFACTURER") "TDK Corporation")
      )
      (libsource (lib "Generic") (part "0603C-100NF-25V-X7R-TDK"))
    )
    (comp (ref "C78")
      (value "1uF")
      (footprint "0603C-GENERIC")
      (description "CAPACITOR 0603 CERAMIC")
      (libsource (lib "Generic") (part "0603C-1UF-25V-X5R-SAM"))
    )
    (comp (ref "C79")
      (value "10uF")
      (footprint "0603C-GENERIC")
      (description "CAPACITOR 0603 CERAMIC")
      (fields
        (field (name "MANUFACTURER") "Murata Electronics North America")
        (field (name "MANUFACTURER PART NUMBER") "GRM188R60J106ME47D")
      )
      (libsource (lib "Generic") (part "0603C-10UF-6V3-X5R-MUR"))
    )
    (comp (ref "C80")
      (value "100nF")
      (footprint "0603C-GENERIC")
      (description "CAPACITOR 0603 CERAMIC")
      (fields
        (field (name "MANUFACTURER PART NUMBER") "C1608X7R1E104K")
        (field (name "MANUFACTURER") "TDK Corporation")
      )
      (libsource (lib "Generic") (part "0603C-100NF-25V-X7R-TDK"))
    )
    (comp (ref "C81")
      (value "100nF")
      (footprint "0603C-GENERIC")
      (description "CAPACITOR 0603 CERAMIC")
      (fields
        (field (name "MANUFACTURER") "Murata Electronics North America")
        (field (name "MANUFACTURER PART NUMBER") "GRM188R60J106ME47D")
      )
      (libsource (lib "Generic") (part "0603C-10UF-6V3-X5R-MUR"))
    )
    (comp (ref "C82")
      (value "10uF")
      (footprint "0603C-GENERIC")
      (description "CAPACITOR 0603 CERAMIC")
      (fields
        (field (name "MANUFACTURER") "Murata Electronics North America")
        (field (name "MANUFACTURER PART NUMBER") "GRM188R60J106ME47D")
      )
      (libsource (lib "Generic") (part "0603C-10UF-6V3-X5R-MUR"))
    )
    (comp (ref "C83")
      (value "100nF")
      (footprint "0603C-GENERIC")
      (description "CAPACITOR 0603 CERAMIC")
      (fields
        (field (name "MANUFACTURER PART NUMBER") "C1608X7R1E104K")
        (field (name "MANUFACTURER") "TDK Corporation")
      )
      (libsource (lib "Generic") (part "0603C-100NF-25V-X7R-TDK"))
    )
    (comp (ref "C84")
      (value "1uF")
      (footprint "0603C-GENERIC")
      (description "CAPACITOR 0603 CERAMIC")
      (libsource (lib "Generic") (part "0603C-1UF-25V-X5R-SAM"))
    )
    (comp (ref "C85")
      (value "47uF 25V")
      (footprint "PANACAP-E-GENERIC")
      (description "GENERIC CAPACITOR POLARISED")
      (libsource (lib "Generic") (part "PANACAP-47UF-50V-FK"))
    )
    (comp (ref "C86")
      (value "10uF")
      (footprint "0603C-GENERIC")
      (description "CAPACITOR 0603 CERAMIC")
      (fields
        (field (name "MANUFACTURER") "Murata Electronics North America")
        (field (name "MANUFACTURER PART NUMBER") "GRM188R60J106ME47D")
      )
      (libsource (lib "Generic") (part "0603C-10UF-6V3-X5R-MUR"))
    )
    (comp (ref "C87")
      (value "10uF")
      (footprint "0603C-GENERIC")
      (description "CAPACITOR 0603 CERAMIC")
      (fields
        (field (name "MANUFACTURER") "Murata Electronics North America")
        (field (name "MANUFACTURER PART NUMBER") "GRM188R60J106ME47D")
      )
      (libsource (lib "Generic") (part "0603C-10UF-6V3-X5R-MUR"))
    )
    (comp (ref "C88")
      (value "10uF")
      (footprint "0603C-GENERIC")
      (description "CAPACITOR 0603 CERAMIC")
      (fields
        (field (name "MANUFACTURER") "Murata Electronics North America")
        (field (name "MANUFACTURER PART NUMBER") "GRM188R60J106ME47D")
      )
      (libsource (lib "Generic") (part "0603C-10UF-6V3-X5R-MUR"))
    )
    (comp (ref "C89")
      (value "100nF")
      (footprint "0603C-GENERIC")
      (description "CAPACITOR 0603 CERAMIC")
      (fields
        (field (name "MANUFACTURER") "Murata Electronics North America")
        (field (name "MANUFACTURER PART NUMBER") "GRM188R60J106ME47D")
      )
      (libsource (lib "Generic") (part "0603C-10UF-6V3-X5R-MUR"))
    )
    (comp (ref "C90")
      (value "100nF")
      (footprint "0603C-GENERIC")
      (description "CAPACITOR 0603 CERAMIC")
      (fields
        (field (name "MANUFACTURER PART NUMBER") "C1608X7R1E104K")
        (field (name "MANUFACTURER") "TDK Corporation")
      )
      (libsource (lib "Generic") (part "0603C-100NF-25V-X7R-TDK"))
    )
    (comp (ref "C91")
      (value "100nF")
      (footprint "0603C-GENERIC")
      (description "CAPACITOR 0603 CERAMIC")
      (fields
        (field (name "MANUFACTURER PART NUMBER") "C1608X7R1E104K")
        (field (name "MANUFACTURER") "TDK Corporation")
      )
      (libsource (lib "Generic") (part "0603C-100NF-25V-X7R-TDK"))
    )
    (comp (ref "C92")
      (value "100nF")
      (footprint "0603C-GENERIC")
      (description "CAPACITOR 0603 CERAMIC")
      (fields
        (field (name "MANUFACTURER PART NUMBER") "C1608X7R1E104K")
        (field (name "MANUFACTURER") "TDK Corporation")
      )
      (libsource (lib "Generic") (part "0603C-100NF-25V-X7R-TDK"))
    )
    (comp (ref "C93")
      (value "100nF")
      (footprint "0603C-GENERIC")
      (description "CAPACITOR 0603 CERAMIC")
      (fields
        (field (name "MANUFACTURER PART NUMBER") "C1608X7R1E104K")
        (field (name "MANUFACTURER") "TDK Corporation")
      )
      (libsource (lib "Generic") (part "0603C-100NF-25V-X7R-TDK"))
    )
    (comp (ref "C94")
      (value "120pf")
      (footprint "0603C-GENERIC")
      (description "CAPACITOR 0603 CERAMIC")
      (fields
        (field (name "MANUFACTURER") "Murata Electronics North America")
        (field (name "MANUFACTURER PART NUMBER") "GRM188R60J106ME47D")
      )
      (libsource (lib "Generic") (part "0603C-10UF-6V3-X5R-MUR"))
    )
    (comp (ref "C95")
      (value "100nF")
      (footprint "0603C-GENERIC")
      (description "CAPACITOR 0603 CERAMIC")
      (fields
        (field (name "MANUFACTURER PART NUMBER") "C1608X7R1E104K")
        (field (name "MANUFACTURER") "TDK Corporation")
      )
      (libsource (lib "Generic") (part "0603C-100NF-25V-X7R-TDK"))
    )
    (comp (ref "C96")
      (value "10nf")
      (footprint "0603C-GENERIC")
      (description "CAPACITOR 0603 CERAMIC")
      (fields
        (field (name "MANUFACTURER") "Murata Electronics North America")
        (field (name "MANUFACTURER PART NUMBER") "GRM188R60J106ME47D")
      )
      (libsource (lib "Generic") (part "0603C-10UF-6V3-X5R-MUR"))
    )
    (comp (ref "C97")
      (value "10uF")
      (footprint "0603C-GENERIC")
      (description "CAPACITOR 0603 CERAMIC")
      (fields
        (field (name "MANUFACTURER") "Murata Electronics North America")
        (field (name "MANUFACTURER PART NUMBER") "GRM188R60J106ME47D")
      )
      (libsource (lib "Generic") (part "0603C-10UF-6V3-X5R-MUR"))
    )
    (comp (ref "C98")
      (value "100nF")
      (footprint "0603C-GENERIC")
      (description "CAPACITOR 0603 CERAMIC")
      (fields
        (field (name "MANUFACTURER PART NUMBER") "C1608X7R1E104K")
        (field (name "MANUFACTURER") "TDK Corporation")
      )
      (libsource (lib "Generic") (part "0603C-100NF-25V-X7R-TDK"))
    )
    (comp (ref "C99")
      (value "1nF")
      (footprint "0603C-GENERIC")
      (description "CAPACITOR 0603 CERAMIC")
      (libsource (lib "Generic") (part "0603C-1NF-50V-X7R"))
    )
    (comp (ref "C100")
      (value "1nF")
      (footprint "0603C-GENERIC")
      (description "CAPACITOR 0603 CERAMIC")
      (libsource (lib "Generic") (part "0603C-1NF-50V-X7R"))
    )
    (comp (ref "C101")
      (value "1nF")
      (footprint "0603C-GENERIC")
      (description "CAPACITOR 0603 CERAMIC")
      (libsource (lib "Generic") (part "0603C-1NF-50V-X7R"))
    )
    (comp (ref "C102")
      (value "47µ")
      (footprint "CAPMP3528X210N")
      (description "Capacitor SMD Tantalum 47uF 20% 6.3V 1210")
      (fields (field (name "TOLERANCE") "±20%") (field (name "RATINGS") "6.3V"))
      (libsource (lib "PBL - Capacitors") (part "CAPT_47u_1210_6V3"))
    )
    (comp (ref "C103")
      (value "1nF")
      (footprint "0603C-GENERIC")
      (description "CAPACITOR 0603 CERAMIC")
      (libsource (lib "Generic") (part "0603C-1NF-50V-X7R"))
    )
    (comp (ref "C104")
      (value "10uF")
      (footprint "0603C-GENERIC")
      (description "CAPACITOR 0603 CERAMIC")
      (fields
        (field (name "MANUFACTURER") "Murata Electronics North America")
        (field (name "MANUFACTURER PART NUMBER") "GRM188R60J106ME47D")
      )
      (libsource (lib "Generic") (part "0603C-10UF-6V3-X5R-MUR"))
    )
    (comp (ref "C105")
      (value "10uF")
      (footprint "0603C-GENERIC")
      (description "CAPACITOR 0603 CERAMIC")
      (fields
        (field (name "MANUFACTURER") "Murata Electronics North America")
        (field (name "MANUFACTURER PART NUMBER") "GRM188R60J106ME47D")
      )
      (libsource (lib "Generic") (part "0603C-10UF-6V3-X5R-MUR"))
    )
    (comp (ref "C106")
      (value "10uf")
      (footprint "CAPMP3528X210N")
      (description "Capacitor SMD Tantalum 47uF 20% 6.3V 1210")
      (fields (field (name "TOLERANCE") "±20%"))
      (libsource (lib "PBL - Capacitors") (part "CAPT_47u_1210_6V3"))
    )
    (comp (ref "C107")
      (value "22uF")
      (footprint "0603C-GENERIC")
      (description "CAPACITOR 0603 CERAMIC")
      (fields
        (field (name "MANUFACTURER") "Murata Electronics North America")
        (field (name "MANUFACTURER PART NUMBER") "GRM188R60J106ME47D")
      )
      (libsource (lib "Generic") (part "0603C-10UF-6V3-X5R-MUR"))
    )
    (comp (ref "C108")
      (value "1nF")
      (footprint "0603C-GENERIC")
      (description "CAPACITOR 0603 CERAMIC")
      (libsource (lib "Generic") (part "0603C-1NF-50V-X7R"))
    )
    (comp (ref "C109")
      (value "100nF")
      (footprint "0603C-GENERIC")
      (description "CAPACITOR 0603 CERAMIC")
      (fields
        (field (name "MANUFACTURER PART NUMBER") "C1608X7R1E104K")
        (field (name "MANUFACTURER") "TDK Corporation")
      )
      (libsource (lib "Generic") (part "0603C-100NF-25V-X7R-TDK"))
    )
    (comp (ref "C110")
      (value "100nF")
      (footprint "0603C-GENERIC")
      (description "CAPACITOR 0603 CERAMIC")
      (fields
        (field (name "MANUFACTURER PART NUMBER") "C1608X7R1E104K")
        (field (name "MANUFACTURER") "TDK Corporation")
      )
      (libsource (lib "Generic") (part "0603C-100NF-25V-X7R-TDK"))
    )
    (comp (ref "C111")
      (value "100nF")
      (footprint "0603C-GENERIC")
      (description "CAPACITOR 0603 CERAMIC")
      (fields
        (field (name "MANUFACTURER PART NUMBER") "C1608X7R1E104K")
        (field (name "MANUFACTURER") "TDK Corporation")
      )
      (libsource (lib "Generic") (part "0603C-100NF-25V-X7R-TDK"))
    )
    (comp (ref "C112")
      (value "47µ")
      (footprint "CAPMP3528X210N")
      (description "Capacitor SMD Tantalum 47uF 20% 6.3V 1210")
      (fields (field (name "TOLERANCE") "±20%") (field (name "RATINGS") "6.3V"))
      (libsource (lib "PBL - Capacitors") (part "CAPT_47u_1210_6V3"))
    )
    (comp (ref "C114")
      (value "10uF")
      (footprint "0603C-GENERIC")
      (description "CAPACITOR 0603 CERAMIC")
      (fields
        (field (name "MANUFACTURER") "Murata Electronics North America")
        (field (name "MANUFACTURER PART NUMBER") "GRM188R60J106ME47D")
      )
      (libsource (lib "Generic") (part "0603C-10UF-6V3-X5R-MUR"))
    )
    (comp (ref "C115")
      (value "10uF")
      (footprint "0603C-GENERIC")
      (description "CAPACITOR 0603 CERAMIC")
      (fields
        (field (name "MANUFACTURER") "Murata Electronics North America")
        (field (name "MANUFACTURER PART NUMBER") "GRM188R60J106ME47D")
      )
      (libsource (lib "Generic") (part "0603C-10UF-6V3-X5R-MUR"))
    )
    (comp (ref "C116")
      (value "10uF")
      (footprint "0603C-GENERIC")
      (description "CAPACITOR 0603 CERAMIC")
      (fields
        (field (name "MANUFACTURER") "Murata Electronics North America")
        (field (name "MANUFACTURER PART NUMBER") "GRM188R60J106ME47D")
      )
      (libsource (lib "Generic") (part "0603C-10UF-6V3-X5R-MUR"))
    )
    (comp (ref "C117")
      (value "10uF")
      (footprint "0603C-GENERIC")
      (description "CAPACITOR 0603 CERAMIC")
      (fields
        (field (name "MANUFACTURER") "Murata Electronics North America")
        (field (name "MANUFACTURER PART NUMBER") "GRM188R60J106ME47D")
      )
      (libsource (lib "Generic") (part "0603C-10UF-6V3-X5R-MUR"))
    )
    (comp (ref "C118")
      (value "100nF")
      (footprint "0603C-GENERIC")
      (description "CAPACITOR 0603 CERAMIC")
      (fields
        (field (name "MANUFACTURER PART NUMBER") "C1608X7R1E104K")
        (field (name "MANUFACTURER") "TDK Corporation")
      )
      (libsource (lib "Generic") (part "0603C-100NF-25V-X7R-TDK"))
    )
    (comp (ref "C120")
      (value "100nF")
      (footprint "0603C-GENERIC")
      (description "CAPACITOR 0603 CERAMIC")
      (fields
        (field (name "MANUFACTURER PART NUMBER") "C1608X7R1E104K")
        (field (name "MANUFACTURER") "TDK Corporation")
      )
      (libsource (lib "Generic") (part "0603C-100NF-25V-X7R-TDK"))
    )
    (comp (ref "C126")
      (value "100nF")
      (footprint "0603C-GENERIC")
      (description "CAPACITOR 0603 CERAMIC")
      (fields
        (field (name "MANUFACTURER PART NUMBER") "C1608X7R1E104K")
        (field (name "MANUFACTURER") "TDK Corporation")
      )
      (libsource (lib "Generic") (part "0603C-100NF-25V-X7R-TDK"))
    )
    (comp (ref "C127")
      (value "100nF")
      (footprint "0603C-GENERIC")
      (description "CAPACITOR 0603 CERAMIC")
      (fields
        (field (name "MANUFACTURER PART NUMBER") "C1608X7R1E104K")
        (field (name "MANUFACTURER") "TDK Corporation")
      )
      (libsource (lib "Generic") (part "0603C-100NF-25V-X7R-TDK"))
    )
    (comp (ref "C128")
      (value "100nF")
      (footprint "0603C-GENERIC")
      (description "CAPACITOR 0603 CERAMIC")
      (fields
        (field (name "MANUFACTURER PART NUMBER") "C1608X7R1E104K")
        (field (name "MANUFACTURER") "TDK Corporation")
      )
      (libsource (lib "Generic") (part "0603C-100NF-25V-X7R-TDK"))
    )
    (comp (ref "C129")
      (value "100nF")
      (footprint "0603C-GENERIC")
      (description "CAPACITOR 0603 CERAMIC")
      (fields
        (field (name "MANUFACTURER PART NUMBER") "C1608X7R1E104K")
        (field (name "MANUFACTURER") "TDK Corporation")
      )
      (libsource (lib "Generic") (part "0603C-100NF-25V-X7R-TDK"))
    )
    (comp (ref "C130")
      (value "10uF")
      (footprint "0603C-GENERIC")
      (description "CAPACITOR 0603 CERAMIC")
      (fields
        (field (name "MANUFACTURER") "Murata Electronics North America")
        (field (name "MANUFACTURER PART NUMBER") "GRM188R60J106ME47D")
      )
      (libsource (lib "Generic") (part "0603C-10UF-6V3-X5R-MUR"))
    )
    (comp (ref "C131")
      (value "10uF")
      (footprint "0603C-GENERIC")
      (description "CAPACITOR 0603 CERAMIC")
      (fields
        (field (name "MANUFACTURER") "Murata Electronics North America")
        (field (name "MANUFACTURER PART NUMBER") "GRM188R60J106ME47D")
      )
      (libsource (lib "Generic") (part "0603C-10UF-6V3-X5R-MUR"))
    )
    (comp (ref "C132")
      (value "10uF")
      (footprint "0603C-GENERIC")
      (description "CAPACITOR 0603 CERAMIC")
      (fields
        (field (name "MANUFACTURER") "Murata Electronics North America")
        (field (name "MANUFACTURER PART NUMBER") "GRM188R60J106ME47D")
      )
      (libsource (lib "Generic") (part "0603C-10UF-6V3-X5R-MUR"))
    )
    (comp (ref "C133")
      (value "10uf")
      (footprint "CAPMP6032X280N")
      (description "Capacitor SMD Tantalum 47uF 10% 16V 6032-28")
      (fields (field (name "TOLERANCE") "±10%"))
      (libsource (lib "PBL - Capacitors") (part "CAPT_47u_6032_16V"))
    )
    (comp (ref "C134")
      (value "47µ")
      (footprint "CAPMP3528X210N")
      (description "Capacitor SMD Tantalum 47uF 20% 6.3V 1210")
      (fields (field (name "TOLERANCE") "±20%") (field (name "RATINGS") "6.3V"))
      (libsource (lib "PBL - Capacitors") (part "CAPT_47u_1210_6V3"))
    )
    (comp (ref "C135")
      (value "100nF")
      (footprint "0603C-GENERIC")
      (description "CAPACITOR 0603 CERAMIC")
      (fields
        (field (name "MANUFACTURER PART NUMBER") "C1608X7R1E104K")
        (field (name "MANUFACTURER") "TDK Corporation")
      )
      (libsource (lib "Generic") (part "0603C-100NF-25V-X7R-TDK"))
    )
    (comp (ref "C136")
      (value "1.6nf")
      (footprint "0603C-GENERIC")
      (description "CAPACITOR 0603 CERAMIC")
      (fields
        (field (name "MANUFACTURER") "Murata Electronics North America")
        (field (name "MANUFACTURER PART NUMBER") "GRM188R60J106ME47D")
      )
      (libsource (lib "Generic") (part "0603C-10UF-6V3-X5R-MUR"))
    )
    (comp (ref "C137")
      (value "10uF")
      (footprint "0603C-GENERIC")
      (description "CAPACITOR 0603 CERAMIC")
      (fields
        (field (name "MANUFACTURER") "Murata Electronics North America")
        (field (name "MANUFACTURER PART NUMBER") "GRM188R60J106ME47D")
      )
      (libsource (lib "Generic") (part "0603C-10UF-6V3-X5R-MUR"))
    )
    (comp (ref "C138")
      (value "47µ")
      (footprint "CAPMP3528X210N")
      (description "Capacitor SMD Tantalum 47uF 20% 6.3V 1210")
      (fields (field (name "TOLERANCE") "±20%") (field (name "RATINGS") "6.3V"))
      (libsource (lib "PBL - Capacitors") (part "CAPT_47u_1210_6V3"))
    )
    (comp (ref "C139")
      (value "10uF")
      (footprint "0603C-GENERIC")
      (description "CAPACITOR 0603 CERAMIC")
      (fields
        (field (name "MANUFACTURER") "Murata Electronics North America")
        (field (name "MANUFACTURER PART NUMBER") "GRM188R60J106ME47D")
      )
      (libsource (lib "Generic") (part "0603C-10UF-6V3-X5R-MUR"))
    )
    (comp (ref "C142")
      (value "100nF")
      (footprint "0603C-GENERIC")
      (description "CAPACITOR 0603 CERAMIC")
      (fields
        (field (name "MANUFACTURER PART NUMBER") "C1608X7R1E104K")
        (field (name "MANUFACTURER") "TDK Corporation")
      )
      (libsource (lib "Generic") (part "0603C-100NF-25V-X7R-TDK"))
    )
    (comp (ref "C143")
      (value "1.6nf")
      (footprint "0603C-GENERIC")
      (description "CAPACITOR 0603 CERAMIC")
      (fields
        (field (name "MANUFACTURER") "Murata Electronics North America")
        (field (name "MANUFACTURER PART NUMBER") "GRM188R60J106ME47D")
      )
      (libsource (lib "Generic") (part "0603C-10UF-6V3-X5R-MUR"))
    )
    (comp (ref "C144")
      (value "10uF")
      (footprint "0603C-GENERIC")
      (description "CAPACITOR 0603 CERAMIC")
      (fields
        (field (name "MANUFACTURER") "Murata Electronics North America")
        (field (name "MANUFACTURER PART NUMBER") "GRM188R60J106ME47D")
      )
      (libsource (lib "Generic") (part "0603C-10UF-6V3-X5R-MUR"))
    )
    (comp (ref "C145")
      (value "1.6nf")
      (footprint "0603C-GENERIC")
      (description "CAPACITOR 0603 CERAMIC")
      (fields
        (field (name "MANUFACTURER") "Murata Electronics North America")
        (field (name "MANUFACTURER PART NUMBER") "GRM188R60J106ME47D")
      )
      (libsource (lib "Generic") (part "0603C-10UF-6V3-X5R-MUR"))
    )
    (comp (ref "C146")
      (value "100nf")
      (footprint "0603C-GENERIC")
      (description "CAPACITOR 0603 CERAMIC")
      (fields
        (field (name "MANUFACTURER") "Murata Electronics North America")
        (field (name "MANUFACTURER PART NUMBER") "GRM188R60J106ME47D")
      )
      (libsource (lib "Generic") (part "0603C-10UF-6V3-X5R-MUR"))
    )
    (comp (ref "C147")
      (value "1.6nf")
      (footprint "0603C-GENERIC")
      (description "CAPACITOR 0603 CERAMIC")
      (fields
        (field (name "MANUFACTURER") "Murata Electronics North America")
        (field (name "MANUFACTURER PART NUMBER") "GRM188R60J106ME47D")
      )
      (libsource (lib "Generic") (part "0603C-10UF-6V3-X5R-MUR"))
    )
    (comp (ref "C148")
      (value "1.6nf")
      (footprint "0603C-GENERIC")
      (description "CAPACITOR 0603 CERAMIC")
      (fields
        (field (name "MANUFACTURER") "Murata Electronics North America")
        (field (name "MANUFACTURER PART NUMBER") "GRM188R60J106ME47D")
      )
      (libsource (lib "Generic") (part "0603C-10UF-6V3-X5R-MUR"))
    )
    (comp (ref "C149")
      (value "220nf")
      (footprint "0603C-GENERIC")
      (description "CAPACITOR 0603 CERAMIC")
      (libsource (lib "Generic") (part "0603C-1UF-25V-X5R-SAM"))
    )
    (comp (ref "C150")
      (value "1.6nf")
      (footprint "0603C-GENERIC")
      (description "CAPACITOR 0603 CERAMIC")
      (fields
        (field (name "MANUFACTURER") "Murata Electronics North America")
        (field (name "MANUFACTURER PART NUMBER") "GRM188R60J106ME47D")
      )
      (libsource (lib "Generic") (part "0603C-10UF-6V3-X5R-MUR"))
    )
    (comp (ref "C151")
      (value "1.6nf")
      (footprint "0603C-GENERIC")
      (description "CAPACITOR 0603 CERAMIC")
      (fields
        (field (name "MANUFACTURER") "Murata Electronics North America")
        (field (name "MANUFACTURER PART NUMBER") "GRM188R60J106ME47D")
      )
      (libsource (lib "Generic") (part "0603C-10UF-6V3-X5R-MUR"))
    )
    (comp (ref "C152")
      (value "1.6nf")
      (footprint "0603C-GENERIC")
      (description "CAPACITOR 0603 CERAMIC")
      (fields
        (field (name "MANUFACTURER") "Murata Electronics North America")
        (field (name "MANUFACTURER PART NUMBER") "GRM188R60J106ME47D")
      )
      (libsource (lib "Generic") (part "0603C-10UF-6V3-X5R-MUR"))
    )
    (comp (ref "C153")
      (value "10uF")
      (footprint "0603C-GENERIC")
      (description "CAPACITOR 0603 CERAMIC")
      (fields
        (field (name "MANUFACTURER") "Murata Electronics North America")
        (field (name "MANUFACTURER PART NUMBER") "GRM188R60J106ME47D")
      )
      (libsource (lib "Generic") (part "0603C-10UF-6V3-X5R-MUR"))
    )
    (comp (ref "C154")
      (value "10uF")
      (footprint "0603C-GENERIC")
      (description "CAPACITOR 0603 CERAMIC")
      (fields
        (field (name "MANUFACTURER") "Murata Electronics North America")
        (field (name "MANUFACTURER PART NUMBER") "GRM188R60J106ME47D")
      )
      (libsource (lib "Generic") (part "0603C-10UF-6V3-X5R-MUR"))
    )
    (comp (ref "C155")
      (value "10uF")
      (footprint "0603C-GENERIC")
      (description "CAPACITOR 0603 CERAMIC")
      (fields
        (field (name "MANUFACTURER") "Murata Electronics North America")
        (field (name "MANUFACTURER PART NUMBER") "GRM188R60J106ME47D")
      )
      (libsource (lib "Generic") (part "0603C-10UF-6V3-X5R-MUR"))
    )
    (comp (ref "C156")
      (value "10uF")
      (footprint "0603C-GENERIC")
      (description "CAPACITOR 0603 CERAMIC")
      (fields
        (field (name "MANUFACTURER") "Murata Electronics North America")
        (field (name "MANUFACTURER PART NUMBER") "GRM188R60J106ME47D")
      )
      (libsource (lib "Generic") (part "0603C-10UF-6V3-X5R-MUR"))
    )
    (comp (ref "C157")
      (value "1uF")
      (footprint "0603C-GENERIC")
      (description "CAPACITOR 0603 CERAMIC")
      (libsource (lib "Generic") (part "0603C-1UF-25V-X5R-SAM"))
    )
    (comp (ref "C158")
      (value "100uF-16V")
      (footprint "PANACAP-D-GENERIC")
      (description "GENERIC CAPACITOR POLARISED")
      (libsource (lib "Generic") (part "PANACAP-100UF-16V-FK"))
    )
    (comp (ref "C159")
      (value "1.6nf")
      (footprint "0603C-GENERIC")
      (description "CAPACITOR 0603 CERAMIC")
      (fields
        (field (name "MANUFACTURER") "Murata Electronics North America")
        (field (name "MANUFACTURER PART NUMBER") "GRM188R60J106ME47D")
      )
      (libsource (lib "Generic") (part "0603C-10UF-6V3-X5R-MUR"))
    )
    (comp (ref "C160")
      (value "1.6nf")
      (footprint "0603C-GENERIC")
      (description "CAPACITOR 0603 CERAMIC")
      (fields
        (field (name "MANUFACTURER") "Murata Electronics North America")
        (field (name "MANUFACTURER PART NUMBER") "GRM188R60J106ME47D")
      )
      (libsource (lib "Generic") (part "0603C-10UF-6V3-X5R-MUR"))
    )
    (comp (ref "C161")
      (value "10uf")
      (footprint "CAPMP3528X210N")
      (description "Capacitor SMD Tantalum 47uF 20% 6.3V 1210")
      (fields (field (name "TOLERANCE") "±20%"))
      (libsource (lib "PBL - Capacitors") (part "CAPT_47u_1210_6V3"))
    )
    (comp (ref "D1")
      (value "MBRS140")
      (footprint "DIODE-SMA")
      (description "DIODE")
      (libsource (lib "Generic") (part "MBRS140"))
    )
    (comp (ref "D2")
      (value "MBRS140")
      (footprint "DIODE-SMA")
      (description "DIODE")
      (libsource (lib "Generic") (part "MBRS140"))
    )
    (comp (ref "D3")
      (value "MBRS140")
      (footprint "DIODE-SMA")
      (description "DIODE")
      (libsource (lib "Generic") (part "MBRS140"))
    )
    (comp (ref "D4")
      (value "MBRS140")
      (footprint "DIODE-SMA")
      (description "DIODE")
      (libsource (lib "Generic") (part "MBRS140"))
    )
    (comp (ref "D5")
      (value "MBRS140")
      (footprint "DIODE-SMA")
      (description "DIODE")
      (libsource (lib "Generic") (part "MBRS140"))
    )
    (comp (ref "D6")
      (value "BAT54S")
      (footprint "SOT23_N")
      (description "Schottky Barrier Double Diode")
      (fields (field (name "PUBLISHER") "Altium Limited"))
      (libsource (lib "Philips Discrete Diode - Schottky") (part "BAT54S"))
    )
    (comp (ref "D7")
      (value "MBRS140")
      (footprint "DIODE-SMA")
      (description "DIODE")
      (libsource (lib "Generic") (part "MBRS140"))
    )
    (comp (ref "D8")
      (value "BAT54S")
      (footprint "SOT23_N")
      (description "Schottky Barrier Double Diode")
      (fields (field (name "PUBLISHER") "Altium Limited"))
      (libsource (lib "Philips Discrete Diode - Schottky") (part "BAT54S"))
    )
    (comp (ref "D9")
      (value "MBRS140")
      (footprint "DIODE-SMA")
      (description "DIODE")
      (libsource (lib "Generic") (part "MBRS140"))
    )
    (comp (ref "D10")
      (value "BAT54S")
      (footprint "SOT23_N")
      (description "Schottky Barrier Double Diode")
      (fields (field (name "PUBLISHER") "Altium Limited"))
      (libsource (lib "Philips Discrete Diode - Schottky") (part "BAT54S"))
    )
    (comp (ref "D11")
      (value "BAT54S")
      (footprint "SOT23_N")
      (description "Schottky Barrier Double Diode")
      (fields (field (name "PUBLISHER") "Altium Limited"))
      (libsource (lib "Philips Discrete Diode - Schottky") (part "BAT54S"))
    )
    (comp (ref "D12")
      (value "MBRS140")
      (footprint "DIODE-SMA")
      (description "DIODE")
      (libsource (lib "Generic") (part "MBRS140"))
    )
    (comp (ref "F1")
      (value "ESD suppressor")
      (footprint "0603ESDA")
      (description "ESD Suppressor 24VDC 0603 SMD")
      (libsource (lib "PBL - Fuses and Protection") (part "ESD_SUPPRESSOR_24VDC"))
    )
    (comp (ref "F2")
      (value "ESD suppressor")
      (footprint "0603ESDA")
      (description "ESD Suppressor 24VDC 0603 SMD")
      (libsource (lib "PBL - Fuses and Protection") (part "ESD_SUPPRESSOR_24VDC"))
    )
    (comp (ref "F3")
      (value "ESD suppressor")
      (footprint "0603ESDA")
      (description "ESD Suppressor 24VDC 0603 SMD")
      (libsource (lib "PBL - Fuses and Protection") (part "ESD_SUPPRESSOR_24VDC"))
    )
    (comp (ref "F4")
      (value "ESD suppressor")
      (footprint "0603ESDA")
      (description "ESD Suppressor 24VDC 0603 SMD")
      (libsource (lib "PBL - Fuses and Protection") (part "ESD_SUPPRESSOR_24VDC"))
    )
    (comp (ref "F5")
      (value "ESD suppressor")
      (footprint "0603ESDA")
      (description "ESD Suppressor 24VDC 0603 SMD")
      (libsource (lib "PBL - Fuses and Protection") (part "ESD_SUPPRESSOR_24VDC"))
    )
    (comp (ref "F6")
      (value "ESD suppressor")
      (footprint "0603ESDA")
      (description "ESD Suppressor 24VDC 0603 SMD")
      (libsource (lib "PBL - Fuses and Protection") (part "ESD_SUPPRESSOR_24VDC"))
    )
    (comp (ref "F7")
      (value "ESD suppressor")
      (footprint "0603ESDA")
      (description "ESD Suppressor 24VDC 0603 SMD")
      (libsource (lib "PBL - Fuses and Protection") (part "ESD_SUPPRESSOR_24VDC"))
    )
    (comp (ref "F8")
      (value "ESD suppressor")
      (footprint "0603ESDA")
      (description "ESD Suppressor 24VDC 0603 SMD")
      (libsource (lib "PBL - Fuses and Protection") (part "ESD_SUPPRESSOR_24VDC"))
    )
    (comp (ref "F9")
      (value "ESD suppressor")
      (footprint "0603ESDA")
      (description "ESD Suppressor 24VDC 0603 SMD")
      (libsource (lib "PBL - Fuses and Protection") (part "ESD_SUPPRESSOR_24VDC"))
    )
    (comp (ref "F10")
      (value "ESD suppressor")
      (footprint "0603ESDA")
      (description "ESD Suppressor 24VDC 0603 SMD")
      (libsource (lib "PBL - Fuses and Protection") (part "ESD_SUPPRESSOR_24VDC"))
    )
    (comp (ref "F11")
      (value "ESD suppressor")
      (footprint "0603ESDA")
      (description "ESD Suppressor 24VDC 0603 SMD")
      (libsource (lib "PBL - Fuses and Protection") (part "ESD_SUPPRESSOR_24VDC"))
    )
    (comp (ref "F12")
      (value "ESD suppressor")
      (footprint "0603ESDA")
      (description "ESD Suppressor 24VDC 0603 SMD")
      (libsource (lib "PBL - Fuses and Protection") (part "ESD_SUPPRESSOR_24VDC"))
    )
    (comp (ref "F13")
      (value "ESD suppressor")
      (footprint "0603ESDA")
      (description "ESD Suppressor 24VDC 0603 SMD")
      (libsource (lib "PBL - Fuses and Protection") (part "ESD_SUPPRESSOR_24VDC"))
    )
    (comp (ref "F14")
      (value "ESD suppressor")
      (footprint "0603ESDA")
      (description "ESD Suppressor 24VDC 0603 SMD")
      (libsource (lib "PBL - Fuses and Protection") (part "ESD_SUPPRESSOR_24VDC"))
    )
    (comp (ref "F15")
      (value "ESD suppressor")
      (footprint "0603ESDA")
      (description "ESD Suppressor 24VDC 0603 SMD")
      (libsource (lib "PBL - Fuses and Protection") (part "ESD_SUPPRESSOR_24VDC"))
    )
    (comp (ref "F16")
      (value "ESD suppressor")
      (footprint "0603ESDA")
      (description "ESD Suppressor 24VDC 0603 SMD")
      (libsource (lib "PBL - Fuses and Protection") (part "ESD_SUPPRESSOR_24VDC"))
    )
    (comp (ref "F17")
      (value "ESD suppressor")
      (footprint "0603ESDA")
      (description "ESD Suppressor 24VDC 0603 SMD")
      (libsource (lib "PBL - Fuses and Protection") (part "ESD_SUPPRESSOR_24VDC"))
    )
    (comp (ref "F18")
      (value "ESD suppressor")
      (footprint "0603ESDA")
      (description "ESD Suppressor 24VDC 0603 SMD")
      (libsource (lib "PBL - Fuses and Protection") (part "ESD_SUPPRESSOR_24VDC"))
    )
    (comp (ref "F19")
      (value "ESD suppressor")
      (footprint "0603ESDA")
      (description "ESD Suppressor 24VDC 0603 SMD")
      (libsource (lib "PBL - Fuses and Protection") (part "ESD_SUPPRESSOR_24VDC"))
    )
    (comp (ref "F20")
      (value "ESD suppressor")
      (footprint "0603ESDA")
      (description "ESD Suppressor 24VDC 0603 SMD")
      (libsource (lib "PBL - Fuses and Protection") (part "ESD_SUPPRESSOR_24VDC"))
    )
    (comp (ref "F21")
      (value "ESD suppressor")
      (footprint "0603ESDA")
      (description "ESD Suppressor 24VDC 0603 SMD")
      (libsource (lib "PBL - Fuses and Protection") (part "ESD_SUPPRESSOR_24VDC"))
    )
    (comp (ref "F22")
      (value "ESD suppressor")
      (footprint "0603ESDA")
      (description "ESD Suppressor 24VDC 0603 SMD")
      (libsource (lib "PBL - Fuses and Protection") (part "ESD_SUPPRESSOR_24VDC"))
    )
    (comp (ref "F23")
      (value "ESD suppressor")
      (footprint "0603ESDA")
      (description "ESD Suppressor 24VDC 0603 SMD")
      (libsource (lib "PBL - Fuses and Protection") (part "ESD_SUPPRESSOR_24VDC"))
    )
    (comp (ref "F24")
      (value "ESD suppressor")
      (footprint "0603ESDA")
      (description "ESD Suppressor 24VDC 0603 SMD")
      (libsource (lib "PBL - Fuses and Protection") (part "ESD_SUPPRESSOR_24VDC"))
    )
    (comp (ref "FB1")
      (value "~")
      (footprint "0805FB-GENERIC")
      (description "FERRITE BEAD SMD")
      (libsource (lib "Generic") (part "0805FB-GENERIC"))
    )
    (comp (ref "FB2")
      (value "~")
      (footprint "0805FB-GENERIC")
      (description "FERRITE BEAD SMD")
      (libsource (lib "Generic") (part "0805FB-GENERIC"))
    )
    (comp (ref "FB4")
      (value "~")
      (footprint "0805FB-GENERIC")
      (description "FERRITE BEAD SMD")
      (libsource (lib "Generic") (part "0805FB-GENERIC"))
    )
    (comp (ref "FB5")
      (value "~")
      (footprint "0805FB-GENERIC")
      (description "FERRITE BEAD SMD")
      (libsource (lib "Generic") (part "0805FB-GENERIC"))
    )
    (comp (ref "J1")
      (value "Micro-USB-B")
      (footprint "USB-MICRO-HW-MC-5F")
      (libsource (lib "USB-MICROB-HW-MC-5F") (part "Micro-USB-B"))
    )
    (comp (ref "J2")
      (value "SMD_USB_A")
      (footprint "USBA_HW-UAF-12")
      (libsource (lib "USB-MICROB-HW-MC-5F") (part "SMD_USB_A"))
    )
    (comp (ref "J3")
      (value "Audio SMD 3.5mm(MIC)")
      (footprint "SMDAudio3.5mm")
      (libsource (lib "") (part "Audio SMD 3.5mm_1"))
    )
    (comp (ref "J4")
      (value "62684-402100ALF")
      (footprint "62684-402100ALF")
      (libsource (lib "FCI_FPC") (part "62684-402100ALF"))
    )
    (comp (ref "J5")
      (value "Tm097tdh01")
      (footprint "FH12A-50S-0.5SH")
      (description "FH12 Series, \"Flip-Lock\" SMT/ZIF FFC/FPC Connector - 0.5mm Spaced Top Contact")
      (fields (field (name "PUBLISHER") "Altium Limited"))
      (libsource (lib "HRS FPC-FFC FH12 Series") (part "CL586-0559-3"))
    )
    (comp (ref "J6")
      (value "1mm pitch fpc 4pin")
      (footprint "52793-0470")
      (libsource (lib "Molexfpc") (part "52793-0470"))
    )
    (comp (ref "J7")
      (value "Audio SMD 3.5mm( Headphone)")
      (footprint "SMDAudio3.5mm")
      (libsource (lib "Audio SMD 3.5mm") (part "Audio SMD 3.5mm"))
    )
    (comp (ref "J8") (value "DC-050") (footprint "DC-050") (libsource (lib "DC_JACK") (part "DC-050")))
    (comp (ref "J9")
      (value "MicroSD_Selfeject")
      (footprint "MicroSD_Selfeject")
      (libsource (lib "MicroSDCard") (part "MicroSD_Selfeject"))
    )
    (comp (ref "J10")
      (value "MicroSD_Selfeject")
      (footprint "MicroSD_Selfeject")
      (libsource (lib "MicroSDCard") (part "MicroSD_Selfeject"))
    )
    (comp (ref "L1")
      (value "2.2uh")
      (footprint "TAIYO_NRS4018T2R2MDGJ")
      (libsource (lib "Inductor") (part "inductor_smd"))
    )
    (comp (ref "L2")
      (value "2.2uh")
      (footprint "TAIYO_NRS4018T2R2MDGJ")
      (libsource (lib "Inductor") (part "inductor_smd"))
    )
    (comp (ref "L3")
      (value "2.2uh")
      (footprint "TAIYO_NRS4018T2R2MDGJ")
      (libsource (lib "Inductor") (part "inductor_smd"))
    )
    (comp (ref "L4")
      (value "10mH")
      (footprint "Inductor-Multicomp-MCSDC060")
      (description "Magnetic-Core Inductor")
      (fields (field (name "PUBLISHER") "Altium Limited"))
      (libsource (lib "Miscellaneous Devices") (part "Inductor Iron"))
    )
    (comp (ref "L5")
      (value "2.2uh")
      (footprint "TAIYO_NRS4018T2R2MDGJ")
      (libsource (lib "Inductor") (part "inductor_smd"))
    )
    (comp (ref "L6")
      (value "2.2uh")
      (footprint "TAIYO_NRS4018T2R2MDGJ")
      (libsource (lib "Inductor") (part "inductor_smd"))
    )
    (comp (ref "L7")
      (value "4.7uh")
      (footprint "TAIYO_NR6028T4R7M")
      (libsource (lib "Inductor") (part "inductor_smd"))
    )
    (comp (ref "L8")
      (value "4.7uh")
      (footprint "TAIYO_NR6028T4R7M")
      (libsource (lib "Inductor") (part "inductor_smd"))
    )
    (comp (ref "L9")
      (value "10uh")
      (footprint "Inductor-Multicomp-MCSDC060")
      (description "Magnetic-Core Inductor")
      (fields (field (name "PUBLISHER") "Altium Limited"))
      (libsource (lib "Miscellaneous Devices") (part "Inductor Iron"))
    )
    (comp (ref "LED1")
      (value "Blue")
      (footprint "LED-0805-K")
      (description "LED 0805 SMD Blue 100mcd 470nm")
      (fields (field (name "COLOR") "Blue"))
      (libsource (lib "PBL - Light Sources") (part "LED_SMD_Blue_0805_100mcd"))
    )
    (comp (ref "P1")
      (value "Header 25X2")
      (footprint "HDR2X25")
      (description "Header, 25-Pin, Dual row")
      (fields (field (name "PUBLISHER") "Altium Limited"))
      (libsource (lib "Miscellaneous Connectors") (part "Header 25X2"))
    )
    (comp (ref "P2")
      (value "Header 7")
      (footprint "HDR1X7")
      (description "Header, 7-Pin")
      (fields (field (name "PUBLISHER") "Altium Limited"))
      (libsource (lib "Miscellaneous Connectors") (part "Header 7"))
    )
    (comp (ref "P3")
      (value "Header 3")
      (footprint "HDR1X3")
      (description "Header, 3-Pin")
      (fields (field (name "PUBLISHER") "Altium Limited"))
      (libsource (lib "Miscellaneous Connectors") (part "Header 3"))
    )
    (comp (ref "P4")
      (value "Header 19X2")
      (footprint "HDR2X19")
      (description "Header, 19-Pin, Dual row")
      (fields (field (name "PUBLISHER") "Altium Limited"))
      (libsource (lib "Miscellaneous Connectors") (part "Header 19X2"))
    )
    (comp (ref "P5")
      (value "Header 2")
      (footprint "HDR1X2")
      (description "Header, 2-Pin")
      (fields (field (name "PUBLISHER") "Altium Limited"))
      (libsource (lib "") (part "Header 2_1"))
    )
    (comp (ref "P6")
      (value "Header 2")
      (footprint "HDR1X2")
      (description "Header, 2-Pin")
      (fields (field (name "PUBLISHER") "Altium Limited"))
      (libsource (lib "Miscellaneous Connectors") (part "Header 2"))
    )
    (comp (ref "Q1")
      (value "DMP3130L-7")
      (footprint "SOT23-GDS")
      (description "P CHANNEL MOSFET")
      (fields
        (field (name "MANUFACTURER PART NUMBER") "DMP2305U-7")
        (field (name "MANUFACTURER") "Diodes Inc")
      )
      (libsource (lib "Generic") (part "DMP2305"))
    )
    (comp (ref "Q2")
      (value "DMP3130L-7")
      (footprint "SOT23-GDS")
      (description "P CHANNEL MOSFET")
      (fields
        (field (name "MANUFACTURER PART NUMBER") "DMP2305U-7")
        (field (name "MANUFACTURER") "Diodes Inc")
      )
      (libsource (lib "Generic") (part "DMP2305"))
    )
    (comp (ref "Q3")
      (value "UN2214")
      (footprint "SOT23_N")
      (description "NPN General-purpose Transistor")
      (fields (field (name "PUBLISHER") "Altium Limited"))
      (libsource (lib "Philips Discrete BJT - Low Power") (part "BC847"))
    )
    (comp (ref "R1")
      (value "240R")
      (footprint "0603R-GENERIC")
      (description "GENERIC RESISTOR 0603")
      (fields (field (name "MANUFACTURER PART NUMBER") "RMCF 1/16 15K 1% R") (field (name "TOLERANCE") "±1%"))
      (libsource (lib "Generic") (part "0603R-240"))
    )
    (comp (ref "R2")
      (value "2K2")
      (footprint "0603R-10K")
      (description "GENERIC RESISTOR 0603")
      (fields (field (name "MANUFACTURER") "Stackpole Electronics Inc") (field (name "TOLERANCE") "±1%"))
      (libsource (lib "Generic") (part "0603R-10K"))
    )
    (comp (ref "R3")
      (value "2K2")
      (footprint "0603R-10K")
      (description "GENERIC RESISTOR 0603")
      (fields (field (name "MANUFACTURER") "Stackpole Electronics Inc") (field (name "TOLERANCE") "±1%"))
      (libsource (lib "Generic") (part "0603R-10K"))
    )
    (comp (ref "R4")
      (value "7R5")
      (footprint "2512R-GENERIC")
      (description "GENERIC RESISTOR 2512")
      (fields
        (field (name "MANUFACTURER PART NUMBER") "CRCW25127R50JNEG")
        (field (name "MANUFACTURER") "Vishay/Dale")
      )
      (libsource (lib "Generic") (part "2512R-7R5"))
    )
    (comp (ref "R5")
      (value "1R")
      (footprint "0603R-GENERIC")
      (description "GENERIC RESISTOR 0603")
      (fields
        (field (name "MANUFACTURER PART NUMBER") "CSR 1/8 1 1% I")
        (field (name "MANUFACTURER") "Stackpole Electronics Inc")
      )
      (libsource (lib "Generic") (part "0603R-1R"))
    )
    (comp (ref "R6")
      (value "1R")
      (footprint "0603R-GENERIC")
      (description "GENERIC RESISTOR 0603")
      (fields
        (field (name "MANUFACTURER PART NUMBER") "CSR 1/8 1 1% I")
        (field (name "MANUFACTURER") "Stackpole Electronics Inc")
      )
      (libsource (lib "Generic") (part "0603R-1R"))
    )
    (comp (ref "R7")
      (value "2K2")
      (footprint "0603R-10K")
      (description "GENERIC RESISTOR 0603")
      (fields (field (name "MANUFACTURER") "Stackpole Electronics Inc") (field (name "TOLERANCE") "±1%"))
      (libsource (lib "Generic") (part "0603R-10K"))
    )
    (comp (ref "R8")
      (value "2K")
      (footprint "0603R-220K")
      (description "GENERIC RESISTOR 0603")
      (fields
        (field (name "MANUFACTURER") "Stackpole Electronics Inc")
        (field (name "MANUFACTURER PART NUMBER") "RMCF 1/16 220K 1% R")
      )
      (libsource (lib "Generic") (part "0603R-220K"))
    )
    (comp (ref "R9")
      (value "2K2")
      (footprint "0603R-10K")
      (description "GENERIC RESISTOR 0603")
      (fields (field (name "MANUFACTURER") "Stackpole Electronics Inc") (field (name "TOLERANCE") "±1%"))
      (libsource (lib "Generic") (part "0603R-10K"))
    )
    (comp (ref "R10")
      (value "240R 1%")
      (footprint "0603R-10K")
      (description "GENERIC RESISTOR 0603")
      (fields (field (name "MANUFACTURER") "Stackpole Electronics Inc") (field (name "TOLERANCE") "±1%"))
      (libsource (lib "Generic") (part "0603R-10K"))
    )
    (comp (ref "R11")
      (value "200K/1%")
      (footprint "0603R-220K")
      (description "GENERIC RESISTOR 0603")
      (fields
        (field (name "MANUFACTURER") "Stackpole Electronics Inc")
        (field (name "MANUFACTURER PART NUMBER") "RMCF 1/16 220K 1% R")
      )
      (libsource (lib "Generic") (part "0603R-220K"))
    )
    (comp (ref "R12")
      (value "2K2")
      (footprint "0603R-2K2")
      (description "GENERIC RESISTOR 0603")
      (fields
        (field (name "MANUFACTURER PART NUMBER") "RMC 1/16 2.2K 1% R")
        (field (name "MANUFACTURER") "Stackpole Electronics Inc")
      )
      (libsource (lib "Generic") (part "0603R-2K2"))
    )
    (comp (ref "R13")
      (value "47K")
      (footprint "0603R-47K")
      (description "GENERIC RESISTOR 0603")
      (fields (field (name "TOLERANCE") "±1%") (field (name "MANUFACTURER") "Stackpole Electronics Inc"))
      (libsource (lib "Generic") (part "0603R-47K"))
    )
    (comp (ref "R14")
      (value "47K")
      (footprint "0603R-10K")
      (description "GENERIC RESISTOR 0603")
      (fields (field (name "MANUFACTURER") "Stackpole Electronics Inc") (field (name "TOLERANCE") "±1%"))
      (libsource (lib "Generic") (part "0603R-10K"))
    )
    (comp (ref "R15")
      (value "2K2")
      (footprint "0603R-2K2")
      (description "GENERIC RESISTOR 0603")
      (fields
        (field (name "MANUFACTURER PART NUMBER") "RMC 1/16 2.2K 1% R")
        (field (name "MANUFACTURER") "Stackpole Electronics Inc")
      )
      (libsource (lib "Generic") (part "0603R-2K2"))
    )
    (comp (ref "R16")
      (value "47K")
      (footprint "0603R-47K")
      (description "GENERIC RESISTOR 0603")
      (fields (field (name "TOLERANCE") "±1%") (field (name "MANUFACTURER") "Stackpole Electronics Inc"))
      (libsource (lib "Generic") (part "0603R-47K"))
    )
    (comp (ref "R17")
      (value "10K")
      (footprint "0603R-10K")
      (description "GENERIC RESISTOR 0603")
      (fields (field (name "MANUFACTURER") "Stackpole Electronics Inc") (field (name "TOLERANCE") "±1%"))
      (libsource (lib "Generic") (part "0603R-10K"))
    )
    (comp (ref "R18")
      (value "~")
      (footprint "0402R-GENERIC")
      (description "RESISTOR 0402 GENERIC")
      (libsource (lib "Generic") (part "0402R-GENERIC"))
    )
    (comp (ref "R19")
      (value "100K")
      (footprint "0603R-10K")
      (description "GENERIC RESISTOR 0603")
      (fields (field (name "MANUFACTURER") "Stackpole Electronics Inc") (field (name "TOLERANCE") "±1%"))
      (libsource (lib "Generic") (part "0603R-10K"))
    )
    (comp (ref "R20")
      (value "~")
      (footprint "0402R-GENERIC")
      (description "RESISTOR 0402 GENERIC")
      (libsource (lib "Generic") (part "0402R-GENERIC"))
    )
    (comp (ref "R21")
      (value "200K")
      (footprint "0603R-220K")
      (description "GENERIC RESISTOR 0603")
      (fields
        (field (name "MANUFACTURER") "Stackpole Electronics Inc")
        (field (name "MANUFACTURER PART NUMBER") "RMCF 1/16 220K 1% R")
      )
      (libsource (lib "Generic") (part "0603R-220K"))
    )
    (comp (ref "R22")
      (value "240R 1%")
      (footprint "0603R-10K")
      (description "GENERIC RESISTOR 0603")
      (fields (field (name "MANUFACTURER") "Stackpole Electronics Inc") (field (name "TOLERANCE") "±1%"))
      (libsource (lib "Generic") (part "0603R-10K"))
    )
    (comp (ref "R23")
      (value "10K")
      (footprint "0603R-10K")
      (description "GENERIC RESISTOR 0603")
      (fields (field (name "MANUFACTURER") "Stackpole Electronics Inc") (field (name "TOLERANCE") "±1%"))
      (libsource (lib "Generic") (part "0603R-10K"))
    )
    (comp (ref "R24")
      (value "300K")
      (footprint "0603R-2K2")
      (description "GENERIC RESISTOR 0603")
      (fields
        (field (name "MANUFACTURER PART NUMBER") "RMC 1/16 2.2K 1% R")
        (field (name "MANUFACTURER") "Stackpole Electronics Inc")
      )
      (libsource (lib "Generic") (part "0603R-2K2"))
    )
    (comp (ref "R25")
      (value "10K")
      (footprint "0603R-10K")
      (description "GENERIC RESISTOR 0603")
      (fields (field (name "MANUFACTURER") "Stackpole Electronics Inc") (field (name "TOLERANCE") "±1%"))
      (libsource (lib "Generic") (part "0603R-10K"))
    )
    (comp (ref "R26")
      (value "200K")
      (footprint "0603R-220K")
      (description "GENERIC RESISTOR 0603")
      (fields
        (field (name "MANUFACTURER") "Stackpole Electronics Inc")
        (field (name "MANUFACTURER PART NUMBER") "RMCF 1/16 220K 1% R")
      )
      (libsource (lib "Generic") (part "0603R-220K"))
    )
    (comp (ref "R27")
      (value "200K")
      (footprint "0603R-220K")
      (description "GENERIC RESISTOR 0603")
      (fields
        (field (name "MANUFACTURER") "Stackpole Electronics Inc")
        (field (name "MANUFACTURER PART NUMBER") "RMCF 1/16 220K 1% R")
      )
      (libsource (lib "Generic") (part "0603R-220K"))
    )
    (comp (ref "R28")
      (value "3.7K")
      (footprint "0603R-2K2")
      (description "GENERIC RESISTOR 0603")
      (fields
        (field (name "MANUFACTURER PART NUMBER") "RMC 1/16 2.2K 1% R")
        (field (name "MANUFACTURER") "Stackpole Electronics Inc")
      )
      (libsource (lib "Generic") (part "0603R-2K2"))
    )
    (comp (ref "R29")
      (value "0R")
      (footprint "0603R-2K2")
      (description "GENERIC RESISTOR 0603")
      (fields
        (field (name "MANUFACTURER PART NUMBER") "RMC 1/16 2.2K 1% R")
        (field (name "MANUFACTURER") "Stackpole Electronics Inc")
      )
      (libsource (lib "Generic") (part "0603R-2K2"))
    )
    (comp (ref "R30")
      (value "2K2")
      (footprint "0603R-2K2")
      (description "GENERIC RESISTOR 0603")
      (fields
        (field (name "MANUFACTURER PART NUMBER") "RMC 1/16 2.2K 1% R")
        (field (name "MANUFACTURER") "Stackpole Electronics Inc")
      )
      (libsource (lib "Generic") (part "0603R-2K2"))
    )
    (comp (ref "R32")
      (value "150K")
      (footprint "0603R-2K2")
      (description "GENERIC RESISTOR 0603")
      (fields
        (field (name "MANUFACTURER PART NUMBER") "RMC 1/16 2.2K 1% R")
        (field (name "MANUFACTURER") "Stackpole Electronics Inc")
      )
      (libsource (lib "Generic") (part "0603R-2K2"))
    )
    (comp (ref "R33")
      (value "56K")
      (footprint "0603R-2K2")
      (description "GENERIC RESISTOR 0603")
      (fields
        (field (name "MANUFACTURER PART NUMBER") "RMC 1/16 2.2K 1% R")
        (field (name "MANUFACTURER") "Stackpole Electronics Inc")
      )
      (libsource (lib "Generic") (part "0603R-2K2"))
    )
    (comp (ref "R34")
      (value "200K")
      (footprint "0603R-220K")
      (description "GENERIC RESISTOR 0603")
      (fields
        (field (name "MANUFACTURER") "Stackpole Electronics Inc")
        (field (name "MANUFACTURER PART NUMBER") "RMCF 1/16 220K 1% R")
      )
      (libsource (lib "Generic") (part "0603R-220K"))
    )
    (comp (ref "R35")
      (value "200K")
      (footprint "0603R-220K")
      (description "GENERIC RESISTOR 0603")
      (fields
        (field (name "MANUFACTURER") "Stackpole Electronics Inc")
        (field (name "MANUFACTURER PART NUMBER") "RMCF 1/16 220K 1% R")
      )
      (libsource (lib "Generic") (part "0603R-220K"))
    )
    (comp (ref "R36")
      (value "200K")
      (footprint "0603R-220K")
      (description "GENERIC RESISTOR 0603")
      (fields
        (field (name "MANUFACTURER") "Stackpole Electronics Inc")
        (field (name "MANUFACTURER PART NUMBER") "RMCF 1/16 220K 1% R")
      )
      (libsource (lib "Generic") (part "0603R-220K"))
    )
    (comp (ref "R37")
      (value "33K")
      (footprint "0603R-2K2")
      (description "GENERIC RESISTOR 0603")
      (fields
        (field (name "MANUFACTURER PART NUMBER") "RMC 1/16 2.2K 1% R")
        (field (name "MANUFACTURER") "Stackpole Electronics Inc")
      )
      (libsource (lib "Generic") (part "0603R-2K2"))
    )
    (comp (ref "R39")
      (value "200K")
      (footprint "0603R-220K")
      (description "GENERIC RESISTOR 0603")
      (fields
        (field (name "MANUFACTURER") "Stackpole Electronics Inc")
        (field (name "MANUFACTURER PART NUMBER") "RMCF 1/16 220K 1% R")
      )
      (libsource (lib "Generic") (part "0603R-220K"))
    )
    (comp (ref "R40")
      (value "4.7K")
      (footprint "0603R-220K")
      (description "GENERIC RESISTOR 0603")
      (fields
        (field (name "MANUFACTURER") "Stackpole Electronics Inc")
        (field (name "MANUFACTURER PART NUMBER") "RMCF 1/16 220K 1% R")
      )
      (libsource (lib "Generic") (part "0603R-220K"))
    )
    (comp (ref "R41")
      (value "4.7K")
      (footprint "0603R-220K")
      (description "GENERIC RESISTOR 0603")
      (fields
        (field (name "MANUFACTURER") "Stackpole Electronics Inc")
        (field (name "MANUFACTURER PART NUMBER") "RMCF 1/16 220K 1% R")
      )
      (libsource (lib "Generic") (part "0603R-220K"))
    )
    (comp (ref "R42")
      (value "22K")
      (footprint "0603R-2K2")
      (description "GENERIC RESISTOR 0603")
      (fields
        (field (name "MANUFACTURER PART NUMBER") "RMC 1/16 2.2K 1% R")
        (field (name "MANUFACTURER") "Stackpole Electronics Inc")
      )
      (libsource (lib "Generic") (part "0603R-2K2"))
    )
    (comp (ref "R43")
      (value "200K")
      (footprint "0603R-220K")
      (description "GENERIC RESISTOR 0603")
      (fields
        (field (name "MANUFACTURER") "Stackpole Electronics Inc")
        (field (name "MANUFACTURER PART NUMBER") "RMCF 1/16 220K 1% R")
      )
      (libsource (lib "Generic") (part "0603R-220K"))
    )
    (comp (ref "R44")
      (value "2K2")
      (footprint "0603R-2K2")
      (description "GENERIC RESISTOR 0603")
      (fields
        (field (name "MANUFACTURER PART NUMBER") "RMC 1/16 2.2K 1% R")
        (field (name "MANUFACTURER") "Stackpole Electronics Inc")
      )
      (libsource (lib "Generic") (part "0603R-2K2"))
    )
    (comp (ref "R45")
      (value "2K2")
      (footprint "0603R-2K2")
      (description "GENERIC RESISTOR 0603")
      (fields
        (field (name "MANUFACTURER PART NUMBER") "RMC 1/16 2.2K 1% R")
        (field (name "MANUFACTURER") "Stackpole Electronics Inc")
      )
      (libsource (lib "Generic") (part "0603R-2K2"))
    )
    (comp (ref "R46")
      (value "10K")
      (footprint "0603R-10K")
      (description "GENERIC RESISTOR 0603")
      (fields (field (name "MANUFACTURER") "Stackpole Electronics Inc") (field (name "TOLERANCE") "±1%"))
      (libsource (lib "Generic") (part "0603R-10K"))
    )
    (comp (ref "R47")
      (value "10K")
      (footprint "0603R-10K")
      (description "GENERIC RESISTOR 0603")
      (fields (field (name "MANUFACTURER") "Stackpole Electronics Inc") (field (name "TOLERANCE") "±1%"))
      (libsource (lib "Generic") (part "0603R-10K"))
    )
    (comp (ref "R48")
      (value "10K")
      (footprint "0603R-10K")
      (description "GENERIC RESISTOR 0603")
      (fields (field (name "MANUFACTURER") "Stackpole Electronics Inc") (field (name "TOLERANCE") "±1%"))
      (libsource (lib "Generic") (part "0603R-10K"))
    )
    (comp (ref "R49")
      (value "10K")
      (footprint "0603R-10K")
      (description "GENERIC RESISTOR 0603")
      (fields (field (name "MANUFACTURER") "Stackpole Electronics Inc") (field (name "TOLERANCE") "±1%"))
      (libsource (lib "Generic") (part "0603R-10K"))
    )
    (comp (ref "R50")
      (value "10K")
      (footprint "0603R-220K")
      (description "GENERIC RESISTOR 0603")
      (fields
        (field (name "MANUFACTURER") "Stackpole Electronics Inc")
        (field (name "MANUFACTURER PART NUMBER") "RMCF 1/16 220K 1% R")
      )
      (libsource (lib "Generic") (part "0603R-220K"))
    )
    (comp (ref "R51")
      (value "10K")
      (footprint "0603R-220K")
      (description "GENERIC RESISTOR 0603")
      (fields
        (field (name "MANUFACTURER") "Stackpole Electronics Inc")
        (field (name "MANUFACTURER PART NUMBER") "RMCF 1/16 220K 1% R")
      )
      (libsource (lib "Generic") (part "0603R-220K"))
    )
    (comp (ref "R52")
      (value "82K")
      (footprint "0603R-2K2")
      (description "GENERIC RESISTOR 0603")
      (fields
        (field (name "MANUFACTURER PART NUMBER") "RMC 1/16 2.2K 1% R")
        (field (name "MANUFACTURER") "Stackpole Electronics Inc")
      )
      (libsource (lib "Generic") (part "0603R-2K2"))
    )
    (comp (ref "R53")
      (value "200K")
      (footprint "0603R-220K")
      (description "GENERIC RESISTOR 0603")
      (fields
        (field (name "MANUFACTURER") "Stackpole Electronics Inc")
        (field (name "MANUFACTURER PART NUMBER") "RMCF 1/16 220K 1% R")
      )
      (libsource (lib "Generic") (part "0603R-220K"))
    )
    (comp (ref "R54")
      (value "2K2")
      (footprint "0603R-2K2")
      (description "GENERIC RESISTOR 0603")
      (fields
        (field (name "MANUFACTURER PART NUMBER") "RMC 1/16 2.2K 1% R")
        (field (name "MANUFACTURER") "Stackpole Electronics Inc")
      )
      (libsource (lib "Generic") (part "0603R-2K2"))
    )
    (comp (ref "R55")
      (value "2K2")
      (footprint "0603R-2K2")
      (description "GENERIC RESISTOR 0603")
      (fields
        (field (name "MANUFACTURER PART NUMBER") "RMC 1/16 2.2K 1% R")
        (field (name "MANUFACTURER") "Stackpole Electronics Inc")
      )
      (libsource (lib "Generic") (part "0603R-2K2"))
    )
    (comp (ref "R56")
      (value "2K2")
      (footprint "0603R-2K2")
      (description "GENERIC RESISTOR 0603")
      (fields
        (field (name "MANUFACTURER PART NUMBER") "RMC 1/16 2.2K 1% R")
        (field (name "MANUFACTURER") "Stackpole Electronics Inc")
      )
      (libsource (lib "Generic") (part "0603R-2K2"))
    )
    (comp (ref "R57")
      (value "2K2")
      (footprint "0603R-2K2")
      (description "GENERIC RESISTOR 0603")
      (fields
        (field (name "MANUFACTURER PART NUMBER") "RMC 1/16 2.2K 1% R")
        (field (name "MANUFACTURER") "Stackpole Electronics Inc")
      )
      (libsource (lib "Generic") (part "0603R-2K2"))
    )
    (comp (ref "R58")
      (value "18K")
      (footprint "0603R-2K2")
      (description "GENERIC RESISTOR 0603")
      (fields
        (field (name "MANUFACTURER PART NUMBER") "RMC 1/16 2.2K 1% R")
        (field (name "MANUFACTURER") "Stackpole Electronics Inc")
      )
      (libsource (lib "Generic") (part "0603R-2K2"))
    )
    (comp (ref "R59")
      (value "10K")
      (footprint "0603R-10K")
      (description "GENERIC RESISTOR 0603")
      (fields (field (name "MANUFACTURER") "Stackpole Electronics Inc") (field (name "TOLERANCE") "±1%"))
      (libsource (lib "Generic") (part "0603R-10K"))
    )
    (comp (ref "R60")
      (value "2K2")
      (footprint "0603R-2K2")
      (description "GENERIC RESISTOR 0603")
      (fields
        (field (name "MANUFACTURER PART NUMBER") "RMC 1/16 2.2K 1% R")
        (field (name "MANUFACTURER") "Stackpole Electronics Inc")
      )
      (libsource (lib "Generic") (part "0603R-2K2"))
    )
    (comp (ref "R61")
      (value "10K")
      (footprint "0603R-220K")
      (description "GENERIC RESISTOR 0603")
      (fields
        (field (name "MANUFACTURER") "Stackpole Electronics Inc")
        (field (name "MANUFACTURER PART NUMBER") "RMCF 1/16 220K 1% R")
      )
      (libsource (lib "Generic") (part "0603R-220K"))
    )
    (comp (ref "R64")
      (value "2K2")
      (footprint "0603R-2K2")
      (description "GENERIC RESISTOR 0603")
      (fields
        (field (name "MANUFACTURER PART NUMBER") "RMC 1/16 2.2K 1% R")
        (field (name "MANUFACTURER") "Stackpole Electronics Inc")
      )
      (libsource (lib "Generic") (part "0603R-2K2"))
    )
    (comp (ref "R65")
      (value "2K2")
      (footprint "0603R-2K2")
      (description "GENERIC RESISTOR 0603")
      (fields
        (field (name "MANUFACTURER PART NUMBER") "RMC 1/16 2.2K 1% R")
        (field (name "MANUFACTURER") "Stackpole Electronics Inc")
      )
      (libsource (lib "Generic") (part "0603R-2K2"))
    )
    (comp (ref "R66")
      (value "47K")
      (footprint "0603R-2K2")
      (description "GENERIC RESISTOR 0603")
      (fields
        (field (name "MANUFACTURER PART NUMBER") "RMC 1/16 2.2K 1% R")
        (field (name "MANUFACTURER") "Stackpole Electronics Inc")
      )
      (libsource (lib "Generic") (part "0603R-2K2"))
    )
    (comp (ref "R67")
      (value "51K")
      (footprint "0603R-2K2")
      (description "GENERIC RESISTOR 0603")
      (fields
        (field (name "MANUFACTURER PART NUMBER") "RMC 1/16 2.2K 1% R")
        (field (name "MANUFACTURER") "Stackpole Electronics Inc")
      )
      (libsource (lib "Generic") (part "0603R-2K2"))
    )
    (comp (ref "R68")
      (value "15K")
      (footprint "0603R-2K2")
      (description "GENERIC RESISTOR 0603")
      (fields
        (field (name "MANUFACTURER PART NUMBER") "RMC 1/16 2.2K 1% R")
        (field (name "MANUFACTURER") "Stackpole Electronics Inc")
      )
      (libsource (lib "Generic") (part "0603R-2K2"))
    )
    (comp (ref "R69")
      (value "91K")
      (footprint "0603R-2K2")
      (description "GENERIC RESISTOR 0603")
      (fields
        (field (name "MANUFACTURER PART NUMBER") "RMC 1/16 2.2K 1% R")
        (field (name "MANUFACTURER") "Stackpole Electronics Inc")
      )
      (libsource (lib "Generic") (part "0603R-2K2"))
    )
    (comp (ref "R70")
      (value "51K")
      (footprint "0603R-2K2")
      (description "GENERIC RESISTOR 0603")
      (fields
        (field (name "MANUFACTURER PART NUMBER") "RMC 1/16 2.2K 1% R")
        (field (name "MANUFACTURER") "Stackpole Electronics Inc")
      )
      (libsource (lib "Generic") (part "0603R-2K2"))
    )
    (comp (ref "R71")
      (value "10K")
      (footprint "0603R-2K2")
      (description "GENERIC RESISTOR 0603")
      (fields
        (field (name "MANUFACTURER PART NUMBER") "RMC 1/16 2.2K 1% R")
        (field (name "MANUFACTURER") "Stackpole Electronics Inc")
      )
      (libsource (lib "Generic") (part "0603R-2K2"))
    )
    (comp (ref "R72")
      (value "1K5")
      (footprint "0603R-2K2")
      (description "GENERIC RESISTOR 0603")
      (fields
        (field (name "MANUFACTURER PART NUMBER") "RMC 1/16 2.2K 1% R")
        (field (name "MANUFACTURER") "Stackpole Electronics Inc")
      )
      (libsource (lib "Generic") (part "0603R-2K2"))
    )
    (comp (ref "R73")
      (value "47K")
      (footprint "0603R-2K2")
      (description "GENERIC RESISTOR 0603")
      (fields
        (field (name "MANUFACTURER PART NUMBER") "RMC 1/16 2.2K 1% R")
        (field (name "MANUFACTURER") "Stackpole Electronics Inc")
      )
      (libsource (lib "Generic") (part "0603R-2K2"))
    )
    (comp (ref "R74")
      (value "1K5")
      (footprint "0603R-2K2")
      (description "GENERIC RESISTOR 0603")
      (fields
        (field (name "MANUFACTURER PART NUMBER") "RMC 1/16 2.2K 1% R")
        (field (name "MANUFACTURER") "Stackpole Electronics Inc")
      )
      (libsource (lib "Generic") (part "0603R-2K2"))
    )
    (comp (ref "R75")
      (value "15R")
      (footprint "0603R-2K2")
      (description "GENERIC RESISTOR 0603")
      (fields
        (field (name "MANUFACTURER PART NUMBER") "RMC 1/16 2.2K 1% R")
        (field (name "MANUFACTURER") "Stackpole Electronics Inc")
      )
      (libsource (lib "Generic") (part "0603R-2K2"))
    )
    (comp (ref "R76")
      (value "15R")
      (footprint "0603R-2K2")
      (description "GENERIC RESISTOR 0603")
      (fields
        (field (name "MANUFACTURER PART NUMBER") "RMC 1/16 2.2K 1% R")
        (field (name "MANUFACTURER") "Stackpole Electronics Inc")
      )
      (libsource (lib "Generic") (part "0603R-2K2"))
    )
    (comp (ref "R77")
      (value "15R")
      (footprint "0603R-2K2")
      (description "GENERIC RESISTOR 0603")
      (fields
        (field (name "MANUFACTURER PART NUMBER") "RMC 1/16 2.2K 1% R")
        (field (name "MANUFACTURER") "Stackpole Electronics Inc")
      )
      (libsource (lib "Generic") (part "0603R-2K2"))
    )
    (comp (ref "R78")
      (value "47K")
      (footprint "0603R-2K2")
      (description "GENERIC RESISTOR 0603")
      (fields
        (field (name "MANUFACTURER PART NUMBER") "RMC 1/16 2.2K 1% R")
        (field (name "MANUFACTURER") "Stackpole Electronics Inc")
      )
      (libsource (lib "Generic") (part "0603R-2K2"))
    )
    (comp (ref "R79")
      (value "2K2")
      (footprint "0603R-2K2")
      (description "GENERIC RESISTOR 0603")
      (fields
        (field (name "MANUFACTURER PART NUMBER") "RMC 1/16 2.2K 1% R")
        (field (name "MANUFACTURER") "Stackpole Electronics Inc")
      )
      (libsource (lib "Generic") (part "0603R-2K2"))
    )
    (comp (ref "R81")
      (value "~")
      (footprint "0402R-GENERIC")
      (description "RESISTOR 0402 GENERIC")
      (libsource (lib "Generic") (part "0402R-GENERIC"))
    )
    (comp (ref "R82")
      (value "~")
      (footprint "0402R-GENERIC")
      (description "RESISTOR 0402 GENERIC")
      (libsource (lib "Generic") (part "0402R-GENERIC"))
    )
    (comp (ref "R83")
      (value "~")
      (footprint "0402R-GENERIC")
      (description "RESISTOR 0402 GENERIC")
      (libsource (lib "Generic") (part "0402R-GENERIC"))
    )
    (comp (ref "R84")
      (value "~")
      (footprint "0402R-GENERIC")
      (description "RESISTOR 0402 GENERIC")
      (libsource (lib "Generic") (part "0402R-GENERIC"))
    )
    (comp (ref "R85")
      (value "~")
      (footprint "0402R-GENERIC")
      (description "RESISTOR 0402 GENERIC")
      (libsource (lib "Generic") (part "0402R-GENERIC"))
    )
    (comp (ref "R86")
      (value "~")
      (footprint "0402R-GENERIC")
      (description "RESISTOR 0402 GENERIC")
      (libsource (lib "Generic") (part "0402R-GENERIC"))
    )
    (comp (ref "RA1")
      (value "Thick Film")
      (footprint "EXV28V")
      (description "Resistor array 4-pack 5% 0402 SMD")
      (libsource (lib "resistors") (part "RES_ARRAY_0402_5%"))
    )
    (comp (ref "RA2")
      (value "Thick Film")
      (footprint "EXV28V")
      (description "Resistor array 4-pack 5% 0402 SMD")
      (libsource (lib "resistors") (part "RES_ARRAY_0402_5%"))
    )
    (comp (ref "RA3")
      (value "Thick Film")
      (footprint "EXV28V")
      (description "Resistor array 4-pack 5% 0402 SMD")
      (libsource (lib "") (part "RES_ARRAY_0402_5%_1"))
    )
    (comp (ref "RA4")
      (value "Thick Film")
      (footprint "EXV28V")
      (description "Resistor array 4-pack 5% 0402 SMD")
      (libsource (lib "resistors") (part "RES_ARRAY_0402_5%"))
    )
    (comp (ref "RA5")
      (value "Thick Film")
      (footprint "EXV28V")
      (description "Resistor array 4-pack 5% 0402 SMD")
      (libsource (lib "resistors") (part "RES_ARRAY_0402_5%"))
    )
    (comp (ref "RA6")
      (value "Thick Film")
      (footprint "EXV28V")
      (description "Resistor array 4-pack 5% 0402 SMD")
      (libsource (lib "resistors") (part "RES_ARRAY_0402_5%"))
    )
    (comp (ref "RA7")
      (value "Thick Film")
      (footprint "EXV28V")
      (description "Resistor array 4-pack 5% 0402 SMD")
      (libsource (lib "resistors") (part "RES_ARRAY_0402_5%"))
    )
    (comp (ref "RA8")
      (value "Thick Film")
      (footprint "EXV28V")
      (description "Resistor array 4-pack 5% 0402 SMD")
      (libsource (lib "resistors") (part "RES_ARRAY_0402_5%"))
    )
    (comp (ref "RA9")
      (value "Thick Film")
      (footprint "EXV28V")
      (description "Resistor array 4-pack 5% 0402 SMD")
      (libsource (lib "resistors") (part "RES_ARRAY_0402_5%"))
    )
    (comp (ref "RA10")
      (value "Thick Film")
      (footprint "EXV28V")
      (description "Resistor array 4-pack 5% 0402 SMD")
      (libsource (lib "resistors") (part "RES_ARRAY_0402_5%"))
    )
    (comp (ref "RA12")
      (value "Thick Film")
      (footprint "EXV28V")
      (description "Resistor array 4-pack 5% 0402 SMD")
      (libsource (lib "resistors") (part "RES_ARRAY_0402_5%"))
    )
    (comp (ref "RA13")
      (value "Thick Film")
      (footprint "EXV28V")
      (description "Resistor array 4-pack 5% 0402 SMD")
      (libsource (lib "resistors") (part "RES_ARRAY_0402_5%"))
    )
    (comp (ref "RA14")
      (value "Thick Film")
      (footprint "EXV28V")
      (description "Resistor array 4-pack 5% 0402 SMD")
      (libsource (lib "resistors") (part "RES_ARRAY_0402_5%"))
    )
    (comp (ref "RA15")
      (value "Thick Film")
      (footprint "EXV28V")
      (description "Resistor array 4-pack 5% 0402 SMD")
      (libsource (lib "resistors") (part "RES_ARRAY_0402_5%"))
    )
    (comp (ref "RA16")
      (value "Thick Film")
      (footprint "EXV28V")
      (description "Resistor array 4-pack 5% 0402 SMD")
      (libsource (lib "resistors") (part "RES_ARRAY_0402_5%"))
    )
    (comp (ref "RA17")
      (value "Thick Film")
      (footprint "EXV28V")
      (description "Resistor array 4-pack 5% 0402 SMD")
      (libsource (lib "resistors") (part "RES_ARRAY_0402_5%"))
    )
    (comp (ref "RA18")
      (value "Thick Film")
      (footprint "EXV28V")
      (description "Resistor array 4-pack 5% 0402 SMD")
      (libsource (lib "resistors") (part "RES_ARRAY_0402_5%"))
    )
    (comp (ref "RA19")
      (value "Thick Film")
      (footprint "EXV28V")
      (description "Resistor array 4-pack 5% 0402 SMD")
      (libsource (lib "resistors") (part "RES_ARRAY_0402_5%"))
    )
    (comp (ref "RA20")
      (value "Thick Film")
      (footprint "EXV28V")
      (description "Resistor array 4-pack 5% 0402 SMD")
      (libsource (lib "resistors") (part "RES_ARRAY_0402_5%"))
    )
    (comp (ref "RA22")
      (value "Thick Film")
      (footprint "EXV28V")
      (description "Resistor array 4-pack 5% 0402 SMD")
      (libsource (lib "resistors") (part "RES_ARRAY_0402_5%"))
    )
    (comp (ref "RA23")
      (value "Thick Film")
      (footprint "EXV28V")
      (description "Resistor array 4-pack 5% 0402 SMD")
      (libsource (lib "resistors") (part "RES_ARRAY_0402_5%"))
    )
    (comp (ref "RA24")
      (value "Thick Film")
      (footprint "EXV28V")
      (description "Resistor array 4-pack 5% 0402 SMD")
      (libsource (lib "") (part "RES_ARRAY_0402_5%_1"))
    )
    (comp (ref "RA25")
      (value "Thick Film")
      (footprint "EXV28V")
      (description "Resistor array 4-pack 5% 0402 SMD")
      (libsource (lib "") (part "RES_ARRAY_0402_5%_1"))
    )
    (comp (ref "RA26")
      (value "Thick Film")
      (footprint "EXV28V")
      (description "Resistor array 4-pack 5% 0402 SMD")
      (libsource (lib "") (part "RES_ARRAY_0402_5%_1"))
    )
    (comp (ref "RA27")
      (value "Thick Film")
      (footprint "EXV28V")
      (description "Resistor array 4-pack 5% 0402 SMD")
      (libsource (lib "") (part "RES_ARRAY_0402_5%_1"))
    )
    (comp (ref "RA28")
      (value "Thick Film")
      (footprint "EXV28V")
      (description "Resistor array 4-pack 5% 0402 SMD")
      (libsource (lib "resistors") (part "RES_ARRAY_0402_5%"))
    )
    (comp (ref "RA29")
      (value "Thick Film")
      (footprint "EXV28V")
      (description "Resistor array 4-pack 5% 0402 SMD")
      (libsource (lib "resistors") (part "RES_ARRAY_0402_5%"))
    )
    (comp (ref "RA30")
      (value "Thick Film")
      (footprint "EXV28V")
      (description "Resistor array 4-pack 5% 0402 SMD")
      (libsource (lib "") (part "RES_ARRAY_0402_5%_2"))
    )
    (comp (ref "SW1")
      (value "PushButton")
      (footprint "PushButtonGrid5.08x3.81")
      (libsource (lib "PushSwitchSmall") (part "PushButton"))
    )
    (comp (ref "SW2")
      (value "PushButton")
      (footprint "PushButtonGrid5.08x3.81")
      (libsource (lib "PushSwitchSmall") (part "PushButton"))
    )
    (comp (ref "SW3")
      (value "PushButton")
      (footprint "PushButtonGrid5.08x3.81")
      (libsource (lib "PushSwitchSmall") (part "PushButton"))
    )
    (comp (ref "SW4")
      (value "PushButton")
      (footprint "PushButtonGrid5.08x3.81")
      (libsource (lib "PushSwitchSmall") (part "PushButton"))
    )
    (comp (ref "SW5")
      (value "PushButton")
      (footprint "PushButtonGrid5.08x3.81")
      (libsource (lib "PushSwitchSmall") (part "PushButton"))
    )
    (comp (ref "U1")
      (value "K4B4G1646D-BCK0")
      (footprint "MICT-JT-96")
      (description "1Gb DDR3-1333 SDRAM, 256Mb x 16, 1.5ns, 1.5V, -40 to 95 degC, 96-Ball FBGA, Pb-Free")
      (fields (field (name "VOLTAGE") "1.5V ") (field (name "MANUFACTURER") "Micron"))
      (libsource (lib "samsung_ddr3_ram") (part "K4B4G1646D-BCK0"))
    )
    (comp (ref "U2")
      (value "Allwinner_A13")
      (footprint "LQFP176L")
      (libsource (lib "Allwinner_A13") (part "Allwinner_A13"))
    )
    (comp (ref "U3") (value "AXP209") (footprint "QFN48") (libsource (lib "Allwinner_A13") (part "AXP209")))
    (comp (ref "U4")
      (value "TPS2065DBVT")
      (footprint "TSOT23-5")
      (libsource (lib "TPS62260") (part "TPS2065DBVT"))
    )
    (comp (ref "U5")
      (value "TPS54335")
      (footprint "D008_L_PowerPad")
      (libsource (lib "TI Power Management") (part "TPS54335"))
    )
    (comp (ref "U6")
      (value "TPS2065DBVT")
      (footprint "TSOT23-5")
      (libsource (lib "TPS62260") (part "TPS2065DBVT"))
    )
    (comp (ref "U7")
      (value "TLV62565DBVT")
      (footprint "TSOT23-5")
      (libsource (lib "TPS62260") (part "TLV62565DBVT"))
    )
    (comp (ref "U9")
      (value "NAND_FLASH")
      (footprint "TSOP-48")
      (libsource (lib "nand_flash") (part "NAND_FLASH"))
    )
    (comp (ref "U10")
      (value "TLV62565DBVT")
      (footprint "TSOT23-5")
      (libsource (lib "TPS62260") (part "TLV62565DBVT"))
    )
    (comp (ref "U11")
      (value "TPS61085DGKR")
      (footprint "TI-DGK8_N")
      (fields (field (name "MANUFACTURER") "Texas Instruments"))
      (libsource (lib "TI Power Management Lighting and Display") (part "TPS61085DGKR"))
    )
    (comp (ref "U12")
      (value "TPS61085DGKR")
      (footprint "TI-DGK8_N")
      (fields (field (name "MANUFACTURER") "Texas Instruments"))
      (libsource (lib "TI Power Management Lighting and Display") (part "TPS61085DGKR"))
    )
    (comp (ref "U13")
      (value "TPS61165DBVR")
      (footprint "TI-DBV6_N")
      (fields (field (name "MANUFACTURER") "Texas Instruments"))
      (libsource (lib "TI Power Management Lighting and Display") (part "TPS61165DBVR"))
    )
    (comp (ref "XT1")
      (value "24Mhz")
      (footprint "Ceramic_crystal_5x3.2")
      (libsource (lib "cermaic_crystal") (part "crystal_cermaic"))
    )
  )
  (nets
    (net (code "1") (name "+5V") (class "Default")
      (node (ref "C71") (pin "2") (pintype "passive"))
      (node (ref "C88") (pin "2") (pintype "passive"))
      (node (ref "D2") (pin "K") (pinfunction "K_K") (pintype "passive"))
      (node (ref "P1") (pin "1") (pinfunction "1_1") (pintype "passive"))
      (node (ref "P4") (pin "3") (pinfunction "3_3") (pintype "passive"))
      (node (ref "Q1") (pin "D") (pintype "passive"))
      (node (ref "U4") (pin "5") (pinfunction "IN_5") (pintype "power_in"))
      (node (ref "U6") (pin "5") (pinfunction "IN_5") (pintype "power_in"))
    )
    (net (code "2") (name "+5VIN") (class "Default")
      (node (ref "C85") (pin "+") (pinfunction "+_+") (pintype "passive"))
      (node (ref "C86") (pin "2") (pintype "passive"))
      (node (ref "D2") (pin "A") (pinfunction "A_A") (pintype "passive"))
      (node (ref "L4") (pin "2") (pinfunction "2_2") (pintype "passive"))
      (node (ref "Q1") (pin "G") (pintype "passive"))
      (node (ref "R24") (pin "2") (pintype "passive"))
      (node (ref "R5") (pin "2") (pintype "passive"))
      (node (ref "U3") (pin "32") (pinfunction "ACIN_32") (pintype "power_in"))
      (node (ref "U3") (pin "33") (pinfunction "ACIN_33") (pintype "power_in"))
    )
    (net (code "3") (name "+5V_OTG") (class "Default")
      (node (ref "FB1") (pin "2") (pintype "passive"))
      (node (ref "J1") (pin "1") (pinfunction "VBus_1") (pintype "power_in"))
      (node (ref "R6") (pin "2") (pintype "passive"))
      (node (ref "U3") (pin "31") (pinfunction "VBUS_31") (pintype "power_in"))
    )
    (net (code "4") (name "/BL_LED+") (class "Default")
      (node (ref "C146") (pin "2") (pintype "passive"))
      (node (ref "D5") (pin "K") (pinfunction "K_K") (pintype "passive"))
      (node (ref "J4") (pin "2") (pinfunction "2_2") (pintype "passive"))
      (node (ref "P5") (pin "2") (pinfunction "2_2") (pintype "passive"))
    )
    (net (code "5") (name "/BL_LED-") (class "Default")
      (node (ref "C146") (pin "1") (pintype "passive"))
      (node (ref "J4") (pin "1") (pinfunction "1_1") (pintype "passive"))
      (node (ref "P5") (pin "1") (pinfunction "1_1") (pintype "passive"))
      (node (ref "R75") (pin "2") (pintype "passive"))
      (node (ref "R76") (pin "2") (pintype "passive"))
      (node (ref "R77") (pin "2") (pintype "passive"))
      (node (ref "U13") (pin "6") (pinfunction "FB_6") (pintype "input"))
    )
    (net (code "6") (name "/BOOT") (class "Default")
      (node (ref "C82") (pin "2") (pintype "passive"))
      (node (ref "U5") (pin "1") (pinfunction "BOOT_1") (pintype "passive"))
    )
    (net (code "7") (name "/CABC") (class "Default")
      (node (ref "J5") (pin "2") (pinfunction "2_2") (pintype "passive"))
      (node (ref "J5") (pin "3") (pinfunction "3_3") (pintype "passive"))
      (node (ref "R23") (pin "2") (pintype "passive"))
      (node (ref "R30") (pin "1") (pintype "passive"))
    )
    (net (code "8") (name "/CH_SW") (class "Default")
      (node (ref "C145") (pin "2") (pintype "passive"))
      (node (ref "C150") (pin "2") (pintype "passive"))
      (node (ref "D4") (pin "A") (pinfunction "A_A") (pintype "passive"))
      (node (ref "L8") (pin "2") (pinfunction "2_2") (pintype "passive"))
      (node (ref "U12") (pin "5") (pinfunction "SW_5") (pintype "power_in"))
    )
    (net (code "9") (name "/COMP") (class "Default")
      (node (ref "C94") (pin "2") (pintype "passive"))
      (node (ref "R28") (pin "2") (pintype "passive"))
      (node (ref "U5") (pin "6") (pinfunction "COMP_6") (pintype "passive"))
    )
    (net (code "10") (name "/DBA0") (class "Default")
      (node (ref "RA5") (pin "6") (pinfunction "6_6") (pintype "passive"))
      (node (ref "U2") (pin "63") (pinfunction "DDR3_BA0_63") (pintype "output"))
    )
    (net (code "11") (name "/DBA1") (class "Default")
      (node (ref "RA6") (pin "6") (pinfunction "6_6") (pintype "passive"))
      (node (ref "U2") (pin "49") (pinfunction "DDR3_BA1_49") (pintype "output"))
    )
    (net (code "12") (name "/DBA2") (class "Default")
      (node (ref "RA5") (pin "7") (pinfunction "7_7") (pintype "passive"))
      (node (ref "U2") (pin "61") (pinfunction "DDR3_BA2_61") (pintype "output"))
    )
    (net (code "13") (name "/DCAS") (class "Default")
      (node (ref "RA10") (pin "5") (pinfunction "5_5") (pintype "passive"))
      (node (ref "U2") (pin "59") (pinfunction "DDR3_CAS_59") (pintype "output"))
    )
    (net (code "14") (name "/DCKE") (class "Default")
      (node (ref "RA6") (pin "8") (pinfunction "8_8") (pintype "passive"))
      (node (ref "U2") (pin "47") (pinfunction "DDR3_CKE_47") (pintype "output"))
    )
    (net (code "15") (name "/DDA0") (class "Default")
      (node (ref "RA5") (pin "5") (pinfunction "5_5") (pintype "passive"))
      (node (ref "U2") (pin "64") (pinfunction "DDR3_A0_64") (pintype "output"))
    )
    (net (code "16") (name "/DDA1") (class "Default")
      (node (ref "RA7") (pin "7") (pinfunction "7_7") (pintype "passive"))
      (node (ref "U2") (pin "52") (pinfunction "DDR3_A1_52") (pintype "output"))
    )
    (net (code "17") (name "/DDA2") (class "Default")
      (node (ref "RA8") (pin "7") (pinfunction "7_7") (pintype "passive"))
      (node (ref "U2") (pin "66") (pinfunction "DDR3_A2_66") (pintype "output"))
    )
    (net (code "18") (name "/DDA3") (class "Default")
      (node (ref "RA8") (pin "8") (pinfunction "8_8") (pintype "passive"))
      (node (ref "U2") (pin "65") (pinfunction "DDR3_A3_65") (pintype "output"))
    )
    (net (code "19") (name "/DDA4") (class "Default")
      (node (ref "RA7") (pin "8") (pinfunction "8_8") (pintype "passive"))
      (node (ref "U2") (pin "51") (pinfunction "DDR3_A4_51") (pintype "output"))
    )
    (net (code "20") (name "/DDA5") (class "Default")
      (node (ref "RA8") (pin "6") (pinfunction "6_6") (pintype "passive"))
      (node (ref "U2") (pin "67") (pinfunction "DDR3_A5_67") (pintype "output"))
    )
    (net (code "21") (name "/DDA6") (class "Default")
      (node (ref "RA7") (pin "6") (pinfunction "6_6") (pintype "passive"))
      (node (ref "U2") (pin "54") (pinfunction "DDR3_A6_54") (pintype "output"))
    )
    (net (code "22") (name "/DDA7") (class "Default")
      (node (ref "RA12") (pin "6") (pinfunction "6_6") (pintype "passive"))
      (node (ref "U2") (pin "71") (pinfunction "DDR3_A7_71") (pintype "output"))
    )
    (net (code "23") (name "/DDA8") (class "Default")
      (node (ref "RA7") (pin "5") (pinfunction "5_5") (pintype "passive"))
      (node (ref "U2") (pin "55") (pinfunction "DDR3_A8_55") (pintype "output"))
    )
    (net (code "24") (name "/DDA9") (class "Default")
      (node (ref "RA12") (pin "8") (pinfunction "8_8") (pintype "passive"))
      (node (ref "U2") (pin "69") (pinfunction "DDR3_A9_69") (pintype "output"))
    )
    (net (code "25") (name "/DDA10") (class "Default")
      (node (ref "RA6") (pin "7") (pinfunction "7_7") (pintype "passive"))
      (node (ref "U2") (pin "48") (pinfunction "DDR3_A10_48") (pintype "output"))
    )
    (net (code "26") (name "/DDA11") (class "Default")
      (node (ref "RA10") (pin "8") (pinfunction "8_8") (pintype "passive"))
      (node (ref "U2") (pin "56") (pinfunction "DDR3_A11_56") (pintype "output"))
    )
    (net (code "27") (name "/DDA12") (class "Default")
      (node (ref "RA6") (pin "5") (pinfunction "5_5") (pintype "passive"))
      (node (ref "U2") (pin "50") (pinfunction "DDR3_A12_50") (pintype "output"))
    )
    (net (code "28") (name "/DDA13") (class "Default")
      (node (ref "RA8") (pin "5") (pinfunction "5_5") (pintype "passive"))
      (node (ref "U2") (pin "68") (pinfunction "DDR3_A13_68") (pintype "output"))
    )
    (net (code "29") (name "/DDA14") (class "Default")
      (node (ref "RA10") (pin "7") (pinfunction "7_7") (pintype "passive"))
      (node (ref "U2") (pin "57") (pinfunction "DDR3_A14_57") (pintype "output"))
    )
    (net (code "30") (name "/DDCK") (class "Default")
      (node (ref "R18") (pin "1") (pintype "passive"))
      (node (ref "U2") (pin "45") (pinfunction "DDR3_CK_45") (pintype "output"))
    )
    (net (code "31") (name "/DDCK_N") (class "Default")
      (node (ref "R20") (pin "1") (pintype "passive"))
      (node (ref "U2") (pin "46") (pinfunction "~{DDR3_CK}_46") (pintype "output"))
    )
    (net (code "32") (name "/DDD0") (class "Default")
      (node (ref "RA1") (pin "5") (pinfunction "5_5") (pintype "passive"))
      (node (ref "U2") (pin "22") (pinfunction "DDR3_D0_22") (pintype "bidirectional"))
    )
    (net (code "33") (name "/DDD1") (class "Default")
      (node (ref "RA9") (pin "8") (pinfunction "8_8") (pintype "passive"))
      (node (ref "U2") (pin "40") (pinfunction "DDR3_D1_40") (pintype "bidirectional"))
    )
    (net (code "34") (name "/DDD2") (class "Default")
      (node (ref "RA1") (pin "6") (pinfunction "6_6") (pintype "passive"))
      (node (ref "U2") (pin "21") (pinfunction "DDR3_D2_21") (pintype "bidirectional"))
    )
    (net (code "35") (name "/DDD3") (class "Default")
      (node (ref "RA9") (pin "7") (pinfunction "7_7") (pintype "passive"))
      (node (ref "U2") (pin "41") (pinfunction "DDR3_D3_41") (pintype "bidirectional"))
    )
    (net (code "36") (name "/DDD4") (class "Default")
      (node (ref "RA1") (pin "8") (pinfunction "8_8") (pintype "passive"))
      (node (ref "U2") (pin "19") (pinfunction "DDR3_D4_19") (pintype "bidirectional"))
    )
    (net (code "37") (name "/DDD5") (class "Default")
      (node (ref "RA9") (pin "5") (pinfunction "5_5") (pintype "passive"))
      (node (ref "U2") (pin "44") (pinfunction "DDR3_D5_44") (pintype "bidirectional"))
    )
    (net (code "38") (name "/DDD6") (class "Default")
      (node (ref "RA1") (pin "7") (pinfunction "7_7") (pintype "passive"))
      (node (ref "U2") (pin "20") (pinfunction "DDR3_D6_20") (pintype "bidirectional"))
    )
    (net (code "39") (name "/DDD7") (class "Default")
      (node (ref "RA9") (pin "6") (pinfunction "6_6") (pintype "passive"))
      (node (ref "U2") (pin "42") (pinfunction "DDR3_D7_42") (pintype "bidirectional"))
    )
    (net (code "40") (name "/DDD8") (class "Default")
      (node (ref "RA4") (pin "7") (pinfunction "7_7") (pintype "passive"))
      (node (ref "U2") (pin "37") (pinfunction "DDR3_D8_37") (pintype "bidirectional"))
    )
    (net (code "41") (name "/DDD9") (class "Default")
      (node (ref "RA2") (pin "7") (pinfunction "7_7") (pintype "passive"))
      (node (ref "U2") (pin "25") (pinfunction "DDR3_D9_25") (pintype "bidirectional"))
    )
    (net (code "42") (name "/DDD10") (class "Default")
      (node (ref "RA4") (pin "5") (pinfunction "5_5") (pintype "passive"))
      (node (ref "U2") (pin "39") (pinfunction "DDR3_D10_39") (pintype "bidirectional"))
    )
    (net (code "43") (name "/DDD11") (class "Default")
      (node (ref "RA2") (pin "8") (pinfunction "8_8") (pintype "passive"))
      (node (ref "U2") (pin "24") (pinfunction "DDR3_D11_24") (pintype "bidirectional"))
    )
    (net (code "44") (name "/DDD12") (class "Default")
      (node (ref "RA4") (pin "8") (pinfunction "8_8") (pintype "passive"))
      (node (ref "U2") (pin "36") (pinfunction "DDR3_D12_36") (pintype "bidirectional"))
    )
    (net (code "45") (name "/DDD13") (class "Default")
      (node (ref "RA2") (pin "6") (pinfunction "6_6") (pintype "passive"))
      (node (ref "U2") (pin "26") (pinfunction "DDR3_D13_26") (pintype "bidirectional"))
    )
    (net (code "46") (name "/DDD14") (class "Default")
      (node (ref "RA4") (pin "6") (pinfunction "6_6") (pintype "passive"))
      (node (ref "U2") (pin "38") (pinfunction "DDR3_D14_38") (pintype "bidirectional"))
    )
    (net (code "47") (name "/DDD15") (class "Default")
      (node (ref "RA2") (pin "5") (pinfunction "5_5") (pintype "passive"))
      (node (ref "U2") (pin "27") (pinfunction "DDR3_D15_27") (pintype "bidirectional"))
    )
    (net (code "48") (name "/DDM0") (class "Default")
      (node (ref "R81") (pin "1") (pintype "passive"))
      (node (ref "U2") (pin "29") (pinfunction "DDR3_DM0_29") (pintype "output"))
    )
    (net (code "49") (name "/DDM1") (class "Default")
      (node (ref "R82") (pin "1") (pintype "passive"))
      (node (ref "U2") (pin "28") (pinfunction "DDR3_DM1_28") (pintype "output"))
    )
    (net (code "50") (name "/DDQS0") (class "Default")
      (node (ref "R83") (pin "1") (pintype "passive"))
      (node (ref "U2") (pin "31") (pinfunction "DDR3_DQS0_31") (pintype "output"))
    )
    (net (code "51") (name "/DDQS0_N") (class "Default")
      (node (ref "R84") (pin "1") (pintype "passive"))
      (node (ref "U2") (pin "32") (pinfunction "~{DDR3_DQS0}_32") (pintype "output"))
    )
    (net (code "52") (name "/DDQS1") (class "Default")
      (node (ref "R85") (pin "1") (pintype "passive"))
      (node (ref "U2") (pin "33") (pinfunction "DDR3_DQS1_33") (pintype "output"))
    )
    (net (code "53") (name "/DDQS1_N") (class "Default")
      (node (ref "R86") (pin "1") (pintype "passive"))
      (node (ref "U2") (pin "34") (pinfunction "~{DDR3_DQS1}_34") (pintype "output"))
    )
    (net (code "54") (name "/DDR_A0") (class "Default")
      (node (ref "RA5") (pin "4") (pinfunction "4_4") (pintype "passive"))
      (node (ref "U1") (pin "N3") (pinfunction "A0_N3") (pintype "input"))
    )
    (net (code "55") (name "/DDR_A1") (class "Default")
      (node (ref "RA7") (pin "2") (pinfunction "2_2") (pintype "passive"))
      (node (ref "U1") (pin "P7") (pinfunction "A1_P7") (pintype "input"))
    )
    (net (code "56") (name "/DDR_A2") (class "Default")
      (node (ref "RA8") (pin "2") (pinfunction "2_2") (pintype "passive"))
      (node (ref "U1") (pin "P3") (pinfunction "A2_P3") (pintype "input"))
    )
    (net (code "57") (name "/DDR_A3") (class "Default")
      (node (ref "RA8") (pin "1") (pinfunction "1_1") (pintype "passive"))
      (node (ref "U1") (pin "N2") (pinfunction "A3_N2") (pintype "input"))
    )
    (net (code "58") (name "/DDR_A4") (class "Default")
      (node (ref "RA7") (pin "1") (pinfunction "1_1") (pintype "passive"))
      (node (ref "U1") (pin "P8") (pinfunction "A4_P8") (pintype "input"))
    )
    (net (code "59") (name "/DDR_A5") (class "Default")
      (node (ref "RA8") (pin "3") (pinfunction "3_3") (pintype "passive"))
      (node (ref "U1") (pin "P2") (pinfunction "A5_P2") (pintype "input"))
    )
    (net (code "60") (name "/DDR_A6") (class "Default")
      (node (ref "RA7") (pin "3") (pinfunction "3_3") (pintype "passive"))
      (node (ref "U1") (pin "R8") (pinfunction "A6_R8") (pintype "input"))
    )
    (net (code "61") (name "/DDR_A7") (class "Default")
      (node (ref "RA12") (pin "3") (pinfunction "3_3") (pintype "passive"))
      (node (ref "U1") (pin "R2") (pinfunction "A7_R2") (pintype "input"))
    )
    (net (code "62") (name "/DDR_A8") (class "Default")
      (node (ref "RA7") (pin "4") (pinfunction "4_4") (pintype "passive"))
      (node (ref "U1") (pin "T8") (pinfunction "A8_T8") (pintype "input"))
    )
    (net (code "63") (name "/DDR_A9") (class "Default")
      (node (ref "RA12") (pin "1") (pinfunction "1_1") (pintype "passive"))
      (node (ref "U1") (pin "R3") (pinfunction "A9_R3") (pintype "input"))
    )
    (net (code "64") (name "/DDR_A10") (class "Default")
      (node (ref "RA6") (pin "2") (pinfunction "2_2") (pintype "passive"))
      (node (ref "U1") (pin "L7") (pinfunction "A10/AP_L7") (pintype "input"))
    )
    (net (code "65") (name "/DDR_A11") (class "Default")
      (node (ref "RA10") (pin "1") (pinfunction "1_1") (pintype "passive"))
      (node (ref "U1") (pin "R7") (pinfunction "A11_R7") (pintype "input"))
    )
    (net (code "66") (name "/DDR_A12") (class "Default")
      (node (ref "RA6") (pin "4") (pinfunction "4_4") (pintype "passive"))
      (node (ref "U1") (pin "N7") (pinfunction "A12/BC#_N7") (pintype "input"))
    )
    (net (code "67") (name "/DDR_A13") (class "Default")
      (node (ref "RA8") (pin "4") (pinfunction "4_4") (pintype "passive"))
      (node (ref "U1") (pin "T3") (pinfunction "A13_T3") (pintype "input"))
    )
    (net (code "68") (name "/DDR_A14") (class "Default")
      (node (ref "RA10") (pin "2") (pinfunction "2_2") (pintype "passive"))
      (node (ref "U1") (pin "T7") (pinfunction "A14_T7") (pintype "input"))
    )
    (net (code "69") (name "/DDR_BA0") (class "Default")
      (node (ref "RA5") (pin "3") (pinfunction "3_3") (pintype "passive"))
      (node (ref "U1") (pin "M2") (pinfunction "BA0_M2") (pintype "input"))
    )
    (net (code "70") (name "/DDR_BA1") (class "Default")
      (node (ref "RA6") (pin "3") (pinfunction "3_3") (pintype "passive"))
      (node (ref "U1") (pin "N8") (pinfunction "BA1_N8") (pintype "input"))
    )
    (net (code "71") (name "/DDR_BA2") (class "Default")
      (node (ref "RA5") (pin "2") (pinfunction "2_2") (pintype "passive"))
      (node (ref "U1") (pin "M3") (pinfunction "BA2_M3") (pintype "input"))
    )
    (net (code "72") (name "/DDR_CAS") (class "Default")
      (node (ref "RA10") (pin "4") (pinfunction "4_4") (pintype "passive"))
      (node (ref "U1") (pin "K3") (pinfunction "CAS_N_K3") (pintype "input"))
    )
    (net (code "73") (name "/DDR_CK") (class "Default")
      (node (ref "C21") (pin "2") (pintype "passive"))
      (node (ref "R18") (pin "2") (pintype "passive"))
      (node (ref "U1") (pin "J7") (pinfunction "CK_J7") (pintype "input"))
    )
    (net (code "74") (name "/DDR_CKE") (class "Default")
      (node (ref "RA6") (pin "1") (pinfunction "1_1") (pintype "passive"))
      (node (ref "U1") (pin "K9") (pinfunction "CKE_K9") (pintype "input"))
    )
    (net (code "75") (name "/DDR_CK_N") (class "Default")
      (node (ref "C21") (pin "1") (pintype "passive"))
      (node (ref "R20") (pin "2") (pintype "passive"))
      (node (ref "U1") (pin "K7") (pinfunction "CK_N_K7") (pintype "input"))
    )
    (net (code "76") (name "/DDR_D0") (class "Default")
      (node (ref "RA1") (pin "4") (pinfunction "4_4") (pintype "passive"))
      (node (ref "U1") (pin "E3") (pinfunction "DQ0_E3") (pintype "bidirectional"))
    )
    (net (code "77") (name "/DDR_D1") (class "Default")
      (node (ref "RA9") (pin "1") (pinfunction "1_1") (pintype "passive"))
      (node (ref "U1") (pin "F7") (pinfunction "DQ1_F7") (pintype "bidirectional"))
    )
    (net (code "78") (name "/DDR_D2") (class "Default")
      (node (ref "RA1") (pin "3") (pinfunction "3_3") (pintype "passive"))
      (node (ref "U1") (pin "F2") (pinfunction "DQ2_F2") (pintype "bidirectional"))
    )
    (net (code "79") (name "/DDR_D3") (class "Default")
      (node (ref "RA9") (pin "2") (pinfunction "2_2") (pintype "passive"))
      (node (ref "U1") (pin "F8") (pinfunction "DQ3_F8") (pintype "bidirectional"))
    )
    (net (code "80") (name "/DDR_D4") (class "Default")
      (node (ref "RA1") (pin "1") (pinfunction "1_1") (pintype "passive"))
      (node (ref "U1") (pin "H3") (pinfunction "DQ4_H3") (pintype "bidirectional"))
    )
    (net (code "81") (name "/DDR_D5") (class "Default")
      (node (ref "RA9") (pin "4") (pinfunction "4_4") (pintype "passive"))
      (node (ref "U1") (pin "H8") (pinfunction "DQ5_H8") (pintype "bidirectional"))
    )
    (net (code "82") (name "/DDR_D6") (class "Default")
      (node (ref "RA1") (pin "2") (pinfunction "2_2") (pintype "passive"))
      (node (ref "U1") (pin "G2") (pinfunction "DQ6_G2") (pintype "bidirectional"))
    )
    (net (code "83") (name "/DDR_D7") (class "Default")
      (node (ref "RA9") (pin "3") (pinfunction "3_3") (pintype "passive"))
      (node (ref "U1") (pin "H7") (pinfunction "DQ7_H7") (pintype "bidirectional"))
    )
    (net (code "84") (name "/DDR_D8") (class "Default")
      (node (ref "RA4") (pin "2") (pinfunction "2_2") (pintype "passive"))
      (node (ref "U1") (pin "D7") (pinfunction "DQ8_D7") (pintype "bidirectional"))
    )
    (net (code "85") (name "/DDR_D9") (class "Default")
      (node (ref "RA2") (pin "2") (pinfunction "2_2") (pintype "passive"))
      (node (ref "U1") (pin "C3") (pinfunction "DQ9_C3") (pintype "bidirectional"))
    )
    (net (code "86") (name "/DDR_D10") (class "Default")
      (node (ref "RA4") (pin "4") (pinfunction "4_4") (pintype "passive"))
      (node (ref "U1") (pin "C8") (pinfunction "DQ10_C8") (pintype "bidirectional"))
    )
    (net (code "87") (name "/DDR_D11") (class "Default")
      (node (ref "RA2") (pin "1") (pinfunction "1_1") (pintype "passive"))
      (node (ref "U1") (pin "C2") (pinfunction "DQ11_C2") (pintype "bidirectional"))
    )
    (net (code "88") (name "/DDR_D12") (class "Default")
      (node (ref "RA4") (pin "1") (pinfunction "1_1") (pintype "passive"))
      (node (ref "U1") (pin "A7") (pinfunction "DQ12_A7") (pintype "bidirectional"))
    )
    (net (code "89") (name "/DDR_D13") (class "Default")
      (node (ref "RA2") (pin "3") (pinfunction "3_3") (pintype "passive"))
      (node (ref "U1") (pin "A2") (pinfunction "DQ13_A2") (pintype "bidirectional"))
    )
    (net (code "90") (name "/DDR_D14") (class "Default")
      (node (ref "RA4") (pin "3") (pinfunction "3_3") (pintype "passive"))
      (node (ref "U1") (pin "B8") (pinfunction "DQ14_B8") (pintype "bidirectional"))
    )
    (net (code "91") (name "/DDR_D15") (class "Default")
      (node (ref "RA2") (pin "4") (pinfunction "4_4") (pintype "passive"))
      (node (ref "U1") (pin "A3") (pinfunction "DQ15_A3") (pintype "bidirectional"))
    )
    (net (code "92") (name "/DDR_DM0") (class "Default")
      (node (ref "R81") (pin "2") (pintype "passive"))
      (node (ref "U1") (pin "E7") (pinfunction "DML_E7") (pintype "input"))
    )
    (net (code "93") (name "/DDR_DM1") (class "Default")
      (node (ref "R82") (pin "2") (pintype "passive"))
      (node (ref "U1") (pin "D3") (pinfunction "DMU_D3") (pintype "input"))
    )
    (net (code "94") (name "/DDR_DQS0") (class "Default")
      (node (ref "R83") (pin "2") (pintype "passive"))
      (node (ref "U1") (pin "F3") (pinfunction "DQSL_F3") (pintype "bidirectional"))
    )
    (net (code "95") (name "/DDR_DQS0_N") (class "Default")
      (node (ref "R84") (pin "2") (pintype "passive"))
      (node (ref "U1") (pin "G3") (pinfunction "DQSL_N_G3") (pintype "bidirectional"))
    )
    (net (code "96") (name "/DDR_DQS1") (class "Default")
      (node (ref "R85") (pin "2") (pintype "passive"))
      (node (ref "U1") (pin "C7") (pinfunction "DQSU_C7") (pintype "bidirectional"))
    )
    (net (code "97") (name "/DDR_DQS1_N") (class "Default")
      (node (ref "R86") (pin "2") (pintype "passive"))
      (node (ref "U1") (pin "B7") (pinfunction "DQSU_N_B7") (pintype "bidirectional"))
    )
    (net (code "98") (name "/DDR_ODT") (class "Default")
      (node (ref "RA12") (pin "4") (pinfunction "4_4") (pintype "passive"))
      (node (ref "U1") (pin "K1") (pinfunction "ODT_K1") (pintype "input"))
    )
    (net (code "99") (name "/DDR_RAS") (class "Default")
      (node (ref "RA10") (pin "3") (pinfunction "3_3") (pintype "passive"))
      (node (ref "U1") (pin "J3") (pinfunction "RAS_N_J3") (pintype "input"))
    )
    (net (code "100") (name "/DDR_RST") (class "Default")
      (node (ref "RA12") (pin "2") (pinfunction "2_2") (pintype "passive"))
      (node (ref "U1") (pin "T2") (pinfunction "RESET#_T2") (pintype "input"))
    )
    (net (code "101") (name "/DDR_WE") (class "Default")
      (node (ref "RA5") (pin "1") (pinfunction "1_1") (pintype "passive"))
      (node (ref "U1") (pin "L3") (pinfunction "WE_N_L3") (pintype "input"))
    )
    (net (code "102") (name "/DODT") (class "Default")
      (node (ref "RA12") (pin "5") (pinfunction "5_5") (pintype "passive"))
      (node (ref "U2") (pin "72") (pinfunction "DDR3_ODT_72") (pintype "output"))
    )
    (net (code "103") (name "/DRAS") (class "Default")
      (node (ref "RA10") (pin "6") (pinfunction "6_6") (pintype "passive"))
      (node (ref "U2") (pin "58") (pinfunction "DDR3_RAS_58") (pintype "output"))
    )
    (net (code "104") (name "/DRST") (class "Default")
      (node (ref "RA12") (pin "7") (pinfunction "7_7") (pintype "passive"))
      (node (ref "U2") (pin "70") (pinfunction "DDR3_RST_70") (pintype "output"))
    )
    (net (code "105") (name "/DWE") (class "Default")
      (node (ref "RA5") (pin "8") (pinfunction "8_8") (pintype "passive"))
      (node (ref "U2") (pin "60") (pinfunction "DDR3_WE_60") (pintype "output"))
    )
    (net (code "106") (name "/EXTEN") (class "Default")
      (node (ref "U10") (pin "1") (pinfunction "EN_1") (pintype "input"))
      (node (ref "U11") (pin "3") (pinfunction "EN_3") (pintype "input"))
      (node (ref "U3") (pin "20") (pinfunction "EXTEN_20") (pintype "output"))
    )
    (net (code "107") (name "/HPCOM") (class "Default")
      (node (ref "F8") (pin "2") (pinfunction "2_2") (pintype "passive"))
      (node (ref "J7") (pin "1") (pinfunction "1_1") (pintype "power_in"))
      (node (ref "J7") (pin "5") (pinfunction "5_5") (pintype "power_in"))
      (node (ref "R35") (pin "2") (pintype "passive"))
      (node (ref "U2") (pin "77") (pinfunction "HPCOM_77") (pintype "power_in"))
    )
    (net (code "108") (name "/HPOUTL") (class "Default")
      (node (ref "F7") (pin "2") (pinfunction "2_2") (pintype "passive"))
      (node (ref "J7") (pin "2") (pinfunction "2_2") (pintype "power_in"))
      (node (ref "R34") (pin "2") (pintype "passive"))
      (node (ref "U2") (pin "74") (pinfunction "HPOUTL_74") (pintype "power_in"))
    )
    (net (code "109") (name "/HPOUTR") (class "Default")
      (node (ref "F9") (pin "2") (pinfunction "2_2") (pintype "passive"))
      (node (ref "J7") (pin "3") (pinfunction "3_3") (pintype "power_in"))
      (node (ref "R36") (pin "2") (pintype "passive"))
      (node (ref "U2") (pin "78") (pinfunction "HPOUTR_78") (pintype "power_in"))
    )
    (net (code "110") (name "/LCD4_STBY") (class "Default")
      (node (ref "C120") (pin "1") (pintype "passive"))
      (node (ref "J4") (pin "31") (pinfunction "31_31") (pintype "passive"))
      (node (ref "R44") (pin "2") (pintype "passive"))
    )
    (net (code "111") (name "/LCD_B2") (class "Default")
      (node (ref "J4") (pin "21") (pinfunction "21_21") (pintype "passive"))
      (node (ref "J4") (pin "22") (pinfunction "22_22") (pintype "passive"))
      (node (ref "J4") (pin "23") (pinfunction "23_23") (pintype "passive"))
      (node (ref "J5") (pin "17") (pinfunction "17_17") (pintype "passive"))
      (node (ref "J5") (pin "18") (pinfunction "18_18") (pintype "passive"))
      (node (ref "J5") (pin "19") (pinfunction "19_19") (pintype "passive"))
      (node (ref "P4") (pin "17") (pinfunction "17_17") (pintype "passive"))
      (node (ref "RA13") (pin "1") (pinfunction "1_1") (pintype "passive"))
    )
    (net (code "112") (name "/LCD_B3") (class "Default")
      (node (ref "J4") (pin "24") (pinfunction "24_24") (pintype "passive"))
      (node (ref "J5") (pin "16") (pinfunction "16_16") (pintype "passive"))
      (node (ref "P4") (pin "18") (pinfunction "18_18") (pintype "passive"))
      (node (ref "RA13") (pin "2") (pinfunction "2_2") (pintype "passive"))
    )
    (net (code "113") (name "/LCD_B4") (class "Default")
      (node (ref "J4") (pin "25") (pinfunction "25_25") (pintype "passive"))
      (node (ref "J5") (pin "15") (pinfunction "15_15") (pintype "passive"))
      (node (ref "P4") (pin "19") (pinfunction "19_19") (pintype "passive"))
      (node (ref "RA13") (pin "3") (pinfunction "3_3") (pintype "passive"))
    )
    (net (code "114") (name "/LCD_B5") (class "Default")
      (node (ref "J4") (pin "26") (pinfunction "26_26") (pintype "passive"))
      (node (ref "J5") (pin "14") (pinfunction "14_14") (pintype "passive"))
      (node (ref "P4") (pin "20") (pinfunction "20_20") (pintype "passive"))
      (node (ref "RA13") (pin "4") (pinfunction "4_4") (pintype "passive"))
    )
    (net (code "115") (name "/LCD_B6") (class "Default")
      (node (ref "J4") (pin "27") (pinfunction "27_27") (pintype "passive"))
      (node (ref "J5") (pin "13") (pinfunction "13_13") (pintype "passive"))
      (node (ref "P4") (pin "21") (pinfunction "21_21") (pintype "passive"))
      (node (ref "RA30") (pin "5") (pinfunction "5_5") (pintype "passive"))
    )
    (net (code "116") (name "/LCD_B7") (class "Default")
      (node (ref "J4") (pin "28") (pinfunction "28_28") (pintype "passive"))
      (node (ref "J5") (pin "12") (pinfunction "12_12") (pintype "passive"))
      (node (ref "P4") (pin "22") (pinfunction "22_22") (pintype "passive"))
      (node (ref "RA30") (pin "6") (pinfunction "6_6") (pintype "passive"))
    )
    (net (code "117") (name "/LCD_BL_EN") (class "Default")
      (node (ref "U13") (pin "2") (pinfunction "CTRL_2") (pintype "input"))
      (node (ref "U3") (pin "18") (pinfunction "GPIO1_18") (pintype "bidirectional"))
    )
    (net (code "118") (name "/LCD_CLK") (class "Default")
      (node (ref "J4") (pin "30") (pinfunction "30_30") (pintype "passive"))
      (node (ref "J5") (pin "37") (pinfunction "37_37") (pintype "passive"))
      (node (ref "P4") (pin "25") (pinfunction "25_25") (pintype "passive"))
      (node (ref "RA17") (pin "1") (pinfunction "1_1") (pintype "passive"))
    )
    (net (code "119") (name "/LCD_DE") (class "Default")
      (node (ref "J4") (pin "34") (pinfunction "34_34") (pintype "passive"))
      (node (ref "J5") (pin "9") (pinfunction "9_9") (pintype "passive"))
      (node (ref "P4") (pin "26") (pinfunction "26_26") (pintype "passive"))
      (node (ref "RA17") (pin "4") (pinfunction "4_4") (pintype "passive"))
    )
    (net (code "120") (name "/LCD_DITHB") (class "Default")
      (node (ref "J5") (pin "47") (pinfunction "47_47") (pintype "passive"))
      (node (ref "R49") (pin "2") (pintype "passive"))
      (node (ref "R57") (pin "1") (pintype "passive"))
    )
    (net (code "121") (name "/LCD_G10") (class "Default")
      (node (ref "J4") (pin "13") (pinfunction "13_13") (pintype "passive"))
      (node (ref "J4") (pin "14") (pinfunction "14_14") (pintype "passive"))
      (node (ref "J4") (pin "15") (pinfunction "15_15") (pintype "passive"))
      (node (ref "J5") (pin "25") (pinfunction "25_25") (pintype "passive"))
      (node (ref "J5") (pin "26") (pinfunction "26_26") (pintype "passive"))
      (node (ref "J5") (pin "27") (pinfunction "27_27") (pintype "passive"))
      (node (ref "P4") (pin "11") (pinfunction "11_11") (pintype "passive"))
      (node (ref "RA16") (pin "3") (pinfunction "3_3") (pintype "passive"))
    )
    (net (code "122") (name "/LCD_G11") (class "Default")
      (node (ref "J4") (pin "16") (pinfunction "16_16") (pintype "passive"))
      (node (ref "J5") (pin "24") (pinfunction "24_24") (pintype "passive"))
      (node (ref "P4") (pin "12") (pinfunction "12_12") (pintype "passive"))
      (node (ref "RA16") (pin "4") (pinfunction "4_4") (pintype "passive"))
    )
    (net (code "123") (name "/LCD_G12") (class "Default")
      (node (ref "J4") (pin "17") (pinfunction "17_17") (pintype "passive"))
      (node (ref "J5") (pin "23") (pinfunction "23_23") (pintype "passive"))
      (node (ref "P4") (pin "13") (pinfunction "13_13") (pintype "passive"))
      (node (ref "RA14") (pin "1") (pinfunction "1_1") (pintype "passive"))
    )
    (net (code "124") (name "/LCD_G13") (class "Default")
      (node (ref "J4") (pin "18") (pinfunction "18_18") (pintype "passive"))
      (node (ref "J5") (pin "22") (pinfunction "22_22") (pintype "passive"))
      (node (ref "P4") (pin "14") (pinfunction "14_14") (pintype "passive"))
      (node (ref "RA14") (pin "2") (pinfunction "2_2") (pintype "passive"))
    )
    (net (code "125") (name "/LCD_G14") (class "Default")
      (node (ref "J4") (pin "19") (pinfunction "19_19") (pintype "passive"))
      (node (ref "J5") (pin "21") (pinfunction "21_21") (pintype "passive"))
      (node (ref "P4") (pin "15") (pinfunction "15_15") (pintype "passive"))
      (node (ref "RA14") (pin "3") (pinfunction "3_3") (pintype "passive"))
    )
    (net (code "126") (name "/LCD_G15") (class "Default")
      (node (ref "J4") (pin "20") (pinfunction "20_20") (pintype "passive"))
      (node (ref "J5") (pin "20") (pinfunction "20_20") (pintype "passive"))
      (node (ref "P4") (pin "16") (pinfunction "16_16") (pintype "passive"))
      (node (ref "RA14") (pin "4") (pinfunction "4_4") (pintype "passive"))
    )
    (net (code "127") (name "/LCD_HSYNC") (class "Default")
      (node (ref "J4") (pin "32") (pinfunction "32_32") (pintype "passive"))
      (node (ref "J5") (pin "11") (pinfunction "11_11") (pintype "passive"))
      (node (ref "P4") (pin "23") (pinfunction "23_23") (pintype "passive"))
      (node (ref "RA17") (pin "2") (pinfunction "2_2") (pintype "passive"))
    )
    (net (code "128") (name "/LCD_L{slash}R") (class "Default")
      (node (ref "J5") (pin "39") (pinfunction "39_39") (pintype "passive"))
      (node (ref "R47") (pin "2") (pintype "passive"))
      (node (ref "R55") (pin "1") (pintype "passive"))
    )
    (net (code "129") (name "/LCD_MODE") (class "Default")
      (node (ref "J5") (pin "8") (pinfunction "8_8") (pintype "passive"))
      (node (ref "R46") (pin "2") (pintype "passive"))
      (node (ref "R54") (pin "1") (pintype "passive"))
    )
    (net (code "130") (name "/LCD_PWR") (class "Default")
      (node (ref "Q3") (pin "1") (pinfunction "B_1") (pintype "passive"))
      (node (ref "U12") (pin "3") (pinfunction "EN_3") (pintype "input"))
      (node (ref "U3") (pin "19") (pinfunction "GPIO0/LDO_19") (pintype "bidirectional"))
    )
    (net (code "131") (name "/LCD_R18") (class "Default")
      (node (ref "J4") (pin "5") (pinfunction "5_5") (pintype "passive"))
      (node (ref "J4") (pin "6") (pinfunction "6_6") (pintype "passive"))
      (node (ref "J4") (pin "7") (pinfunction "7_7") (pintype "passive"))
      (node (ref "J5") (pin "33") (pinfunction "33_33") (pintype "passive"))
      (node (ref "J5") (pin "34") (pinfunction "34_34") (pintype "passive"))
      (node (ref "J5") (pin "35") (pinfunction "35_35") (pintype "passive"))
      (node (ref "P4") (pin "5") (pinfunction "5_5") (pintype "passive"))
      (node (ref "RA15") (pin "1") (pinfunction "1_1") (pintype "passive"))
    )
    (net (code "132") (name "/LCD_R19") (class "Default")
      (node (ref "J4") (pin "8") (pinfunction "8_8") (pintype "passive"))
      (node (ref "J5") (pin "32") (pinfunction "32_32") (pintype "passive"))
      (node (ref "P4") (pin "6") (pinfunction "6_6") (pintype "passive"))
      (node (ref "RA15") (pin "2") (pinfunction "2_2") (pintype "passive"))
    )
    (net (code "133") (name "/LCD_R20") (class "Default")
      (node (ref "J4") (pin "9") (pinfunction "9_9") (pintype "passive"))
      (node (ref "J5") (pin "31") (pinfunction "31_31") (pintype "passive"))
      (node (ref "P4") (pin "7") (pinfunction "7_7") (pintype "passive"))
      (node (ref "RA15") (pin "3") (pinfunction "3_3") (pintype "passive"))
    )
    (net (code "134") (name "/LCD_R21") (class "Default")
      (node (ref "J4") (pin "10") (pinfunction "10_10") (pintype "passive"))
      (node (ref "J5") (pin "30") (pinfunction "30_30") (pintype "passive"))
      (node (ref "P4") (pin "8") (pinfunction "8_8") (pintype "passive"))
      (node (ref "RA15") (pin "4") (pinfunction "4_4") (pintype "passive"))
    )
    (net (code "135") (name "/LCD_R22") (class "Default")
      (node (ref "J4") (pin "11") (pinfunction "11_11") (pintype "passive"))
      (node (ref "J5") (pin "29") (pinfunction "29_29") (pintype "passive"))
      (node (ref "P4") (pin "9") (pinfunction "9_9") (pintype "passive"))
      (node (ref "RA16") (pin "1") (pinfunction "1_1") (pintype "passive"))
    )
    (net (code "136") (name "/LCD_R23") (class "Default")
      (node (ref "J4") (pin "12") (pinfunction "12_12") (pintype "passive"))
      (node (ref "J5") (pin "28") (pinfunction "28_28") (pintype "passive"))
      (node (ref "P4") (pin "10") (pinfunction "10_10") (pintype "passive"))
      (node (ref "RA16") (pin "2") (pinfunction "2_2") (pintype "passive"))
    )
    (net (code "137") (name "/LCD_RESET_N") (class "Default")
      (node (ref "C118") (pin "1") (pintype "passive"))
      (node (ref "J5") (pin "44") (pinfunction "44_44") (pintype "passive"))
      (node (ref "R45") (pin "2") (pintype "passive"))
    )
    (net (code "138") (name "/LCD_U{slash}D") (class "Default")
      (node (ref "J5") (pin "40") (pinfunction "40_40") (pintype "passive"))
      (node (ref "R48") (pin "2") (pintype "passive"))
      (node (ref "R56") (pin "1") (pintype "passive"))
    )
    (net (code "139") (name "/LCD_VCOM") (class "Default")
      (node (ref "C126") (pin "1") (pintype "passive"))
      (node (ref "J5") (pin "46") (pinfunction "46_46") (pintype "passive"))
      (node (ref "J5") (pin "6") (pinfunction "6_6") (pintype "passive"))
      (node (ref "R59") (pin "2") (pintype "passive"))
      (node (ref "R60") (pin "2") (pintype "passive"))
      (node (ref "R64") (pin "1") (pintype "passive"))
      (node (ref "R65") (pin "1") (pintype "passive"))
    )
    (net (code "140") (name "/LCD_VSYNC") (class "Default")
      (node (ref "J4") (pin "33") (pinfunction "33_33") (pintype "passive"))
      (node (ref "J5") (pin "10") (pinfunction "10_10") (pintype "passive"))
      (node (ref "P4") (pin "24") (pinfunction "24_24") (pintype "passive"))
      (node (ref "RA17") (pin "3") (pinfunction "3_3") (pintype "passive"))
    )
    (net (code "141") (name "/LRADC") (class "Default")
      (node (ref "C99") (pin "2") (pintype "passive"))
      (node (ref "R39") (pin "2") (pintype "passive"))
      (node (ref "R43") (pin "2") (pintype "passive"))
      (node (ref "SW3") (pin "2") (pinfunction "P2_2") (pintype "passive"))
      (node (ref "U2") (pin "86") (pinfunction "LRADC_86") (pintype "power_in"))
    )
    (net (code "142") (name "/MICIN") (class "Default")
      (node (ref "C92") (pin "2") (pintype "passive"))
      (node (ref "C93") (pin "1") (pintype "passive"))
      (node (ref "F10") (pin "2") (pinfunction "2_2") (pintype "passive"))
      (node (ref "J3") (pin "3") (pinfunction "3_3") (pintype "power_in"))
      (node (ref "R26") (pin "2") (pintype "passive"))
    )
    (net (code "143") (name "/NAND_WP") (class "Default")
      (node (ref "C129") (pin "1") (pintype "passive"))
      (node (ref "R61") (pin "1") (pintype "passive"))
      (node (ref "U9") (pin "19") (pinfunction "WP#_19") (pintype "input"))
    )
    (net (code "144") (name "/NMI_N") (class "Default")
      (node (ref "R16") (pin "2") (pintype "passive"))
      (node (ref "U2") (pin "158") (pinfunction "~{NMI}_158") (pintype "passive"))
      (node (ref "U3") (pin "48") (pinfunction "IRQ/WAKEUP_48") (pintype "input"))
    )
    (net (code "145") (name "/PB2{slash}PWM") (class "Default")
      (node (ref "P1") (pin "47") (pinfunction "47_47") (pintype "passive"))
      (node (ref "U2") (pin "103") (pinfunction "PB2/PWM/SPI2_MOSI/EINT16_103") (pintype "bidirectional"))
    )
    (net (code "146") (name "/PB3{slash}IR_TX") (class "Default")
      (node (ref "P1") (pin "10") (pinfunction "10_10") (pintype "passive"))
      (node (ref "U2") (pin "150") (pinfunction "PB3/IR_TX/SPI2_MISO/EINT17_150") (pintype "bidirectional"))
    )
    (net (code "147") (name "/PB4{slash}IR_RX") (class "Default")
      (node (ref "P1") (pin "48") (pinfunction "48_48") (pintype "passive"))
      (node (ref "U2") (pin "104") (pinfunction "PB4/IR_RX/EINT18_104") (pintype "bidirectional"))
    )
    (net (code "148") (name "/PC0{slash}SPI0_MOSI") (class "Default")
      (node (ref "P4") (pin "31") (pinfunction "31_31") (pintype "passive"))
      (node (ref "U2") (pin "8") (pinfunction "PC0/NWE/SPI0_MOSI_8") (pintype "bidirectional"))
      (node (ref "U9") (pin "18") (pinfunction "WE#_18") (pintype "input"))
    )
    (net (code "149") (name "/PC1{slash}SPI0_MISO") (class "Default")
      (node (ref "P4") (pin "34") (pinfunction "34_34") (pintype "passive"))
      (node (ref "U2") (pin "7") (pinfunction "PC1/NALE/SPI0_MISO_7") (pintype "bidirectional"))
      (node (ref "U9") (pin "17") (pinfunction "ALE_17") (pintype "input"))
    )
    (net (code "150") (name "/PC2{slash}SPI0_CLK") (class "Default")
      (node (ref "P4") (pin "33") (pinfunction "33_33") (pintype "passive"))
      (node (ref "U2") (pin "6") (pinfunction "PC2/NCLE/SPI0_CLK_6") (pintype "bidirectional"))
      (node (ref "U9") (pin "16") (pinfunction "CLE_16") (pintype "input"))
    )
    (net (code "151") (name "/PC3{slash}SPI0_CS0") (class "Default")
      (node (ref "P4") (pin "36") (pinfunction "36_36") (pintype "passive"))
      (node (ref "U2") (pin "3") (pinfunction "PC3/NCE1/SPI0_CS0_3") (pintype "bidirectional"))
    )
    (net (code "152") (name "/PC4") (class "Default")
      (node (ref "P1") (pin "8") (pinfunction "8_8") (pintype "passive"))
      (node (ref "R51") (pin "1") (pintype "passive"))
      (node (ref "U2") (pin "2") (pinfunction "PC4/NCE0_2") (pintype "bidirectional"))
      (node (ref "U9") (pin "9") (pinfunction "CE#_9") (pintype "input"))
    )
    (net (code "153") (name "/PC5") (class "Default")
      (node (ref "F24") (pin "1") (pinfunction "1_1") (pintype "passive"))
      (node (ref "J10") (pin "10") (pinfunction "Card_Detect2_10") (pintype "passive"))
      (node (ref "J10") (pin "9") (pinfunction "Card_Detect1_9") (pintype "passive"))
      (node (ref "P1") (pin "7") (pinfunction "7_7") (pintype "passive"))
      (node (ref "RA27") (pin "8") (pinfunction "8_8") (pintype "passive"))
      (node (ref "U2") (pin "1") (pinfunction "PC5/NRE_1") (pintype "bidirectional"))
      (node (ref "U9") (pin "8") (pinfunction "RE#_8") (pintype "input"))
    )
    (net (code "154") (name "/PC6{slash}SDC2_CMD") (class "Default")
      (node (ref "P1") (pin "12") (pinfunction "12_12") (pintype "passive"))
      (node (ref "R50") (pin "1") (pintype "passive"))
      (node (ref "RA28") (pin "6") (pinfunction "6_6") (pintype "passive"))
      (node (ref "U2") (pin "176") (pinfunction "PC6/NRB0/SDC2_CMD_176") (pintype "bidirectional"))
      (node (ref "U9") (pin "7") (pinfunction "R/B#_7") (pintype "output"))
    )
    (net (code "155") (name "/PC7{slash}SDC2_CLK") (class "Default")
      (node (ref "P1") (pin "11") (pinfunction "11_11") (pintype "passive"))
      (node (ref "RA28") (pin "5") (pinfunction "5_5") (pintype "passive"))
      (node (ref "U2") (pin "175") (pinfunction "PC7/NRB1/SDC2_CLK_175") (pintype "bidirectional"))
    )
    (net (code "156") (name "/PC8{slash}SDC2_D0") (class "Default")
      (node (ref "P1") (pin "14") (pinfunction "14_14") (pintype "passive"))
      (node (ref "RA29") (pin "7") (pinfunction "7_7") (pintype "passive"))
      (node (ref "U2") (pin "174") (pinfunction "PC8/NDQ0/SDC2_D0_174") (pintype "bidirectional"))
      (node (ref "U9") (pin "29") (pinfunction "I/O0_29") (pintype "bidirectional"))
    )
    (net (code "157") (name "/PC9{slash}SDC2_D1") (class "Default")
      (node (ref "P1") (pin "13") (pinfunction "13_13") (pintype "passive"))
      (node (ref "RA29") (pin "8") (pinfunction "8_8") (pintype "passive"))
      (node (ref "U2") (pin "172") (pinfunction "PC9/NDQ1/SDC2_D1_172") (pintype "bidirectional"))
      (node (ref "U9") (pin "30") (pinfunction "I/O1_30") (pintype "bidirectional"))
    )
    (net (code "158") (name "/PC10{slash}SDC2_D2") (class "Default")
      (node (ref "P1") (pin "16") (pinfunction "16_16") (pintype "passive"))
      (node (ref "RA28") (pin "8") (pinfunction "8_8") (pintype "passive"))
      (node (ref "U2") (pin "171") (pinfunction "PC10/NDQ2/SDC2_D2_171") (pintype "bidirectional"))
      (node (ref "U9") (pin "31") (pinfunction "I/O2_31") (pintype "bidirectional"))
    )
    (net (code "159") (name "/PC11{slash}SDC2_D3") (class "Default")
      (node (ref "P1") (pin "15") (pinfunction "15_15") (pintype "passive"))
      (node (ref "RA28") (pin "7") (pinfunction "7_7") (pintype "passive"))
      (node (ref "U2") (pin "170") (pinfunction "PC11/NDQ3/SDC2_D3_170") (pintype "bidirectional"))
      (node (ref "U9") (pin "32") (pinfunction "I/O3_32") (pintype "bidirectional"))
    )
    (net (code "160") (name "/PC12{slash}SDC2_D4") (class "Default")
      (node (ref "P1") (pin "18") (pinfunction "18_18") (pintype "passive"))
      (node (ref "U2") (pin "168") (pinfunction "PC12/NDQ4/SDC2_D4_168") (pintype "bidirectional"))
      (node (ref "U9") (pin "41") (pinfunction "I/O4_41") (pintype "bidirectional"))
    )
    (net (code "161") (name "/PC13{slash}SDC2_D5") (class "Default")
      (node (ref "P1") (pin "17") (pinfunction "17_17") (pintype "passive"))
      (node (ref "U2") (pin "167") (pinfunction "PC13/NDQ5/SDC2_D5_167") (pintype "bidirectional"))
      (node (ref "U9") (pin "42") (pinfunction "I/O5_42") (pintype "bidirectional"))
    )
    (net (code "162") (name "/PC14{slash}SDC2_D6") (class "Default")
      (node (ref "P1") (pin "20") (pinfunction "20_20") (pintype "passive"))
      (node (ref "U2") (pin "166") (pinfunction "PC14/NDQ6/SDC2_D6_166") (pintype "bidirectional"))
      (node (ref "U9") (pin "43") (pinfunction "I/O6_43") (pintype "bidirectional"))
    )
    (net (code "163") (name "/PC15{slash}SDC2_D7") (class "Default")
      (node (ref "P1") (pin "19") (pinfunction "19_19") (pintype "passive"))
      (node (ref "U2") (pin "165") (pinfunction "PC15/NDQ7/SDC2_D7_165") (pintype "bidirectional"))
      (node (ref "U9") (pin "44") (pinfunction "I/O7_44") (pintype "bidirectional"))
    )
    (net (code "164") (name "/PC19") (class "Default")
      (node (ref "P1") (pin "9") (pinfunction "9_9") (pintype "passive"))
      (node (ref "U2") (pin "162") (pinfunction "PC19/NDQS_162") (pintype "bidirectional"))
    )
    (net (code "165") (name "/PE0{slash}CSI_PLCK") (class "Default")
      (node (ref "P1") (pin "39") (pinfunction "39_39") (pintype "passive"))
      (node (ref "RA18") (pin "1") (pinfunction "1_1") (pintype "passive"))
    )
    (net (code "166") (name "/PE1{slash}CSI_MCLK") (class "Default")
      (node (ref "P1") (pin "40") (pinfunction "40_40") (pintype "passive"))
      (node (ref "RA18") (pin "2") (pinfunction "2_2") (pintype "passive"))
    )
    (net (code "167") (name "/PE2{slash}CSI_HSYNC") (class "Default")
      (node (ref "P1") (pin "37") (pinfunction "37_37") (pintype "passive"))
      (node (ref "RA18") (pin "3") (pinfunction "3_3") (pintype "passive"))
    )
    (net (code "168") (name "/PE3{slash}CSI_VSYNC") (class "Default")
      (node (ref "P1") (pin "38") (pinfunction "38_38") (pintype "passive"))
      (node (ref "RA18") (pin "4") (pinfunction "4_4") (pintype "passive"))
    )
    (net (code "169") (name "/PE4{slash}CSI_D0") (class "Default")
      (node (ref "P1") (pin "35") (pinfunction "35_35") (pintype "passive"))
      (node (ref "RA19") (pin "1") (pinfunction "1_1") (pintype "passive"))
    )
    (net (code "170") (name "/PE5{slash}CSI_D1") (class "Default")
      (node (ref "P1") (pin "36") (pinfunction "36_36") (pintype "passive"))
      (node (ref "RA19") (pin "2") (pinfunction "2_2") (pintype "passive"))
    )
    (net (code "171") (name "/PE6{slash}CSI_D2") (class "Default")
      (node (ref "P1") (pin "33") (pinfunction "33_33") (pintype "passive"))
      (node (ref "RA19") (pin "3") (pinfunction "3_3") (pintype "passive"))
    )
    (net (code "172") (name "/PE7{slash}CSI_D3") (class "Default")
      (node (ref "P1") (pin "34") (pinfunction "34_34") (pintype "passive"))
      (node (ref "RA19") (pin "4") (pinfunction "4_4") (pintype "passive"))
    )
    (net (code "173") (name "/PE8{slash}CSI_D4") (class "Default")
      (node (ref "P1") (pin "31") (pinfunction "31_31") (pintype "passive"))
      (node (ref "RA20") (pin "1") (pinfunction "1_1") (pintype "passive"))
    )
    (net (code "174") (name "/PE9{slash}CSI_D5") (class "Default")
      (node (ref "P1") (pin "32") (pinfunction "32_32") (pintype "passive"))
      (node (ref "RA20") (pin "2") (pinfunction "2_2") (pintype "passive"))
    )
    (net (code "175") (name "/PE10{slash}CSI_D6") (class "Default")
      (node (ref "P1") (pin "29") (pinfunction "29_29") (pintype "passive"))
      (node (ref "RA20") (pin "3") (pinfunction "3_3") (pintype "passive"))
    )
    (net (code "176") (name "/PE11{slash}CSI_D7") (class "Default")
      (node (ref "P1") (pin "30") (pinfunction "30_30") (pintype "passive"))
      (node (ref "RA20") (pin "4") (pinfunction "4_4") (pintype "passive"))
    )
    (net (code "177") (name "/PG1") (class "Default")
      (node (ref "P1") (pin "23") (pinfunction "23_23") (pintype "passive"))
      (node (ref "R14") (pin "2") (pintype "passive"))
      (node (ref "R19") (pin "1") (pintype "passive"))
      (node (ref "U2") (pin "154") (pinfunction "PG1/EINT1_154") (pintype "bidirectional"))
    )
    (net (code "178") (name "/PG2") (class "Default")
      (node (ref "F3") (pin "2") (pinfunction "2_2") (pintype "passive"))
      (node (ref "J1") (pin "4") (pinfunction "ID_4") (pintype "passive"))
      (node (ref "P1") (pin "24") (pinfunction "24_24") (pintype "passive"))
      (node (ref "U2") (pin "153") (pinfunction "PG2/EINT2_153") (pintype "bidirectional"))
    )
    (net (code "179") (name "/PH") (class "Default")
      (node (ref "C82") (pin "1") (pintype "passive"))
      (node (ref "L4") (pin "1") (pinfunction "1_1") (pintype "passive"))
      (node (ref "U5") (pin "3") (pinfunction "PH_3") (pintype "passive"))
    )
    (net (code "180") (name "/PIN2") (class "Default")
      (node (ref "U3") (pin "5") (pinfunction "GPIO2_5") (pintype "bidirectional"))
    )
    (net (code "181") (name "/PIN3") (class "Default")
      (node (ref "U3") (pin "3") (pinfunction "GPIO3_3") (pintype "bidirectional"))
    )
    (net (code "182") (name "/PWRON") (class "Default")
      (node (ref "R12") (pin "1") (pintype "passive"))
      (node (ref "SW1") (pin "2") (pinfunction "P2_2") (pintype "passive"))
    )
    (net (code "183") (name "/RESET_N") (class "Default")
      (node (ref "C70") (pin "2") (pintype "passive"))
      (node (ref "C74") (pin "2") (pintype "passive"))
      (node (ref "P1") (pin "5") (pinfunction "5_5") (pintype "passive"))
      (node (ref "P2") (pin "2") (pinfunction "2_2") (pintype "passive"))
      (node (ref "R13") (pin "2") (pintype "passive"))
      (node (ref "U2") (pin "159") (pinfunction "~{RESET_N}_159") (pintype "passive"))
      (node (ref "U3") (pin "25") (pinfunction "PWROK_25") (pintype "output"))
    )
    (net (code "184") (name "/RESET_SW") (class "Default")
      (node (ref "R15") (pin "2") (pintype "passive"))
      (node (ref "SW2") (pin "2") (pinfunction "P2_2") (pintype "passive"))
      (node (ref "U3") (pin "4") (pinfunction "~{OE}_4") (pintype "input"))
    )
    (net (code "185") (name "/SD1") (class "Default")
      (node (ref "F18") (pin "1") (pinfunction "1_1") (pintype "passive"))
      (node (ref "J10") (pin "1") (pinfunction "NC_1") (pintype "passive"))
      (node (ref "RA27") (pin "7") (pinfunction "7_7") (pintype "passive"))
      (node (ref "RA28") (pin "1") (pinfunction "1_1") (pintype "passive"))
    )
    (net (code "186") (name "/SD2") (class "Default")
      (node (ref "F19") (pin "1") (pinfunction "1_1") (pintype "passive"))
      (node (ref "J10") (pin "2") (pinfunction "CS_2") (pintype "input"))
      (node (ref "RA27") (pin "6") (pinfunction "6_6") (pintype "passive"))
      (node (ref "RA28") (pin "2") (pinfunction "2_2") (pintype "passive"))
    )
    (net (code "187") (name "/SD3") (class "Default")
      (node (ref "F20") (pin "1") (pinfunction "1_1") (pintype "passive"))
      (node (ref "J10") (pin "3") (pinfunction "DI_3") (pintype "input"))
      (node (ref "RA26") (pin "8") (pinfunction "8_8") (pintype "passive"))
      (node (ref "RA28") (pin "3") (pinfunction "3_3") (pintype "passive"))
    )
    (net (code "188") (name "/SD4") (class "Default")
      (node (ref "F21") (pin "1") (pinfunction "1_1") (pintype "passive"))
      (node (ref "J10") (pin "5") (pinfunction "SCK_5") (pintype "input"))
      (node (ref "RA26") (pin "7") (pinfunction "7_7") (pintype "passive"))
      (node (ref "RA28") (pin "4") (pinfunction "4_4") (pintype "passive"))
    )
    (net (code "189") (name "/SD5") (class "Default")
      (node (ref "F22") (pin "1") (pinfunction "1_1") (pintype "passive"))
      (node (ref "J10") (pin "7") (pinfunction "DO_7") (pintype "output"))
      (node (ref "RA26") (pin "6") (pinfunction "6_6") (pintype "passive"))
      (node (ref "RA29") (pin "2") (pinfunction "2_2") (pintype "passive"))
    )
    (net (code "190") (name "/SD6") (class "Default")
      (node (ref "F23") (pin "1") (pinfunction "1_1") (pintype "passive"))
      (node (ref "J10") (pin "8") (pinfunction "RSV_8") (pintype "passive"))
      (node (ref "RA26") (pin "5") (pinfunction "5_5") (pintype "passive"))
      (node (ref "RA29") (pin "1") (pinfunction "1_1") (pintype "passive"))
    )
    (net (code "191") (name "/SDC0_CLK") (class "Default")
      (node (ref "F14") (pin "1") (pinfunction "1_1") (pintype "passive"))
      (node (ref "J9") (pin "5") (pinfunction "SCK_5") (pintype "input"))
      (node (ref "RA22") (pin "3") (pinfunction "3_3") (pintype "passive"))
      (node (ref "RA24") (pin "7") (pinfunction "7_7") (pintype "passive"))
    )
    (net (code "192") (name "/SDC0_CMD") (class "Default")
      (node (ref "F13") (pin "1") (pinfunction "1_1") (pintype "passive"))
      (node (ref "J9") (pin "3") (pinfunction "DI_3") (pintype "input"))
      (node (ref "P2") (pin "4") (pinfunction "4_4") (pintype "passive"))
      (node (ref "RA22") (pin "4") (pinfunction "4_4") (pintype "passive"))
      (node (ref "RA24") (pin "8") (pinfunction "8_8") (pintype "passive"))
    )
    (net (code "193") (name "/SDC0_D0") (class "Default")
      (node (ref "F15") (pin "1") (pinfunction "1_1") (pintype "passive"))
      (node (ref "J9") (pin "7") (pinfunction "DO_7") (pintype "output"))
      (node (ref "P2") (pin "5") (pinfunction "5_5") (pintype "passive"))
      (node (ref "RA22") (pin "2") (pinfunction "2_2") (pintype "passive"))
      (node (ref "RA24") (pin "6") (pinfunction "6_6") (pintype "passive"))
    )
    (net (code "194") (name "/SDC0_D1") (class "Default")
      (node (ref "F16") (pin "1") (pinfunction "1_1") (pintype "passive"))
      (node (ref "J9") (pin "8") (pinfunction "RSV_8") (pintype "passive"))
      (node (ref "P2") (pin "6") (pinfunction "6_6") (pintype "passive"))
      (node (ref "RA22") (pin "1") (pinfunction "1_1") (pintype "passive"))
      (node (ref "RA24") (pin "5") (pinfunction "5_5") (pintype "passive"))
    )
    (net (code "195") (name "/SDC0_D2") (class "Default")
      (node (ref "F11") (pin "1") (pinfunction "1_1") (pintype "passive"))
      (node (ref "J9") (pin "1") (pinfunction "NC_1") (pintype "passive"))
      (node (ref "P2") (pin "3") (pinfunction "3_3") (pintype "passive"))
      (node (ref "RA23") (pin "4") (pinfunction "4_4") (pintype "passive"))
      (node (ref "RA25") (pin "7") (pinfunction "7_7") (pintype "passive"))
    )
    (net (code "196") (name "/SDC0_D3") (class "Default")
      (node (ref "F12") (pin "1") (pinfunction "1_1") (pintype "passive"))
      (node (ref "J9") (pin "2") (pinfunction "CS_2") (pintype "input"))
      (node (ref "RA23") (pin "3") (pinfunction "3_3") (pintype "passive"))
      (node (ref "RA25") (pin "6") (pinfunction "6_6") (pintype "passive"))
    )
    (net (code "197") (name "/SDC0_DETECT") (class "Default")
      (node (ref "F17") (pin "1") (pinfunction "1_1") (pintype "passive"))
      (node (ref "J9") (pin "10") (pinfunction "Card_Detect2_10") (pintype "passive"))
      (node (ref "J9") (pin "9") (pinfunction "Card_Detect1_9") (pintype "passive"))
      (node (ref "RA25") (pin "8") (pinfunction "8_8") (pintype "passive"))
      (node (ref "U2") (pin "155") (pinfunction "PG0/EINT0_155") (pintype "bidirectional"))
    )
    (net (code "198") (name "/SD_VCC") (class "Default")
      (node (ref "C153") (pin "1") (pintype "passive"))
      (node (ref "C154") (pin "2") (pintype "passive"))
      (node (ref "FB4") (pin "2") (pintype "passive"))
      (node (ref "J9") (pin "4") (pinfunction "VCC_4") (pintype "power_in"))
    )
    (net (code "199") (name "/SPI1_CLK{slash}UART3_RX") (class "Default")
      (node (ref "P4") (pin "29") (pinfunction "29_29") (pintype "passive"))
      (node (ref "U2") (pin "13") (pinfunction "PG10/SPI1_CLK/UART3_RX/EINT10_13") (pintype "bidirectional"))
    )
    (net (code "200") (name "/SPI1_CS0{slash}UART3_TX") (class "Default")
      (node (ref "P4") (pin "32") (pinfunction "32_32") (pintype "passive"))
      (node (ref "U2") (pin "12") (pinfunction "PG9/SPI1_CS0/UART3_TX/EINT9_12") (pintype "bidirectional"))
    )
    (net (code "201") (name "/SPI1_MISO") (class "Default")
      (node (ref "P4") (pin "27") (pinfunction "27_27") (pintype "passive"))
      (node (ref "U2") (pin "15") (pinfunction "PG12/SPI1_MISO/UART3_RTS/INT12_15") (pintype "bidirectional"))
    )
    (net (code "202") (name "/SPI1_MOSI") (class "Default")
      (node (ref "P4") (pin "30") (pinfunction "30_30") (pintype "passive"))
      (node (ref "U2") (pin "14") (pinfunction "PG11/SPI1_MOSI/UART3_CTS/EINT11_14") (pintype "bidirectional"))
    )
    (net (code "203") (name "/SVREF") (class "Default")
      (node (ref "C33") (pin "1") (pintype "passive"))
      (node (ref "C55") (pin "2") (pintype "passive"))
      (node (ref "C81") (pin "2") (pintype "passive"))
      (node (ref "R7") (pin "1") (pintype "passive"))
      (node (ref "R9") (pin "1") (pintype "passive"))
      (node (ref "U2") (pin "18") (pinfunction "SVREF_18") (pintype "passive"))
    )
    (net (code "204") (name "/TPX1") (class "Default")
      (node (ref "C100") (pin "2") (pintype "passive"))
      (node (ref "J4") (pin "37") (pinfunction "37_37") (pintype "passive"))
      (node (ref "J6") (pin "1") (pinfunction "1_1") (pintype "passive"))
      (node (ref "U2") (pin "89") (pinfunction "TPX1_89") (pintype "power_in"))
    )
    (net (code "205") (name "/TPX2") (class "Default")
      (node (ref "C103") (pin "2") (pintype "passive"))
      (node (ref "J4") (pin "39") (pinfunction "39_39") (pintype "passive"))
      (node (ref "J6") (pin "3") (pinfunction "3_3") (pintype "passive"))
      (node (ref "U2") (pin "87") (pinfunction "TPX2_87") (pintype "power_in"))
    )
    (net (code "206") (name "/TPY1") (class "Default")
      (node (ref "C101") (pin "2") (pintype "passive"))
      (node (ref "J4") (pin "38") (pinfunction "38_38") (pintype "passive"))
      (node (ref "J6") (pin "2") (pinfunction "2_2") (pintype "passive"))
      (node (ref "U2") (pin "90") (pinfunction "TPY1_90") (pintype "power_in"))
    )
    (net (code "207") (name "/TPY2") (class "Default")
      (node (ref "C108") (pin "2") (pintype "passive"))
      (node (ref "J4") (pin "40") (pinfunction "40_40") (pintype "passive"))
      (node (ref "J6") (pin "4") (pinfunction "4_4") (pintype "passive"))
      (node (ref "U2") (pin "88") (pinfunction "TPY2_88") (pintype "power_in"))
    )
    (net (code "208") (name "/TWI0_SCK") (class "Default")
      (node (ref "P1") (pin "45") (pinfunction "45_45") (pintype "passive"))
      (node (ref "P4") (pin "37") (pinfunction "37_37") (pintype "passive"))
      (node (ref "RA3") (pin "5") (pinfunction "5_5") (pintype "passive"))
      (node (ref "U2") (pin "101") (pinfunction "PB0/TWI0-SCK_101") (pintype "bidirectional"))
      (node (ref "U3") (pin "2") (pinfunction "SCK_2") (pintype "input"))
    )
    (net (code "209") (name "/TWI0_SDA") (class "Default")
      (node (ref "P1") (pin "46") (pinfunction "46_46") (pintype "passive"))
      (node (ref "P4") (pin "35") (pinfunction "35_35") (pintype "passive"))
      (node (ref "RA3") (pin "8") (pinfunction "8_8") (pintype "passive"))
      (node (ref "U2") (pin "102") (pinfunction "PB1/TWI0-SDA_102") (pintype "bidirectional"))
      (node (ref "U3") (pin "1") (pinfunction "SDA_1") (pintype "bidirectional"))
    )
    (net (code "210") (name "/TWI1_SCK") (class "Default")
      (node (ref "P1") (pin "43") (pinfunction "43_43") (pintype "passive"))
      (node (ref "RA3") (pin "7") (pinfunction "7_7") (pintype "passive"))
      (node (ref "U2") (pin "105") (pinfunction "PB15/TWI1_SCK_105") (pintype "bidirectional"))
    )
    (net (code "211") (name "/TWI1_SDA") (class "Default")
      (node (ref "P1") (pin "44") (pinfunction "44_44") (pintype "passive"))
      (node (ref "RA3") (pin "6") (pinfunction "6_6") (pintype "passive"))
      (node (ref "U2") (pin "106") (pinfunction "PB16/TWI1_SDA_106") (pintype "bidirectional"))
    )
    (net (code "212") (name "/TWI2_SCK") (class "Default")
      (node (ref "P1") (pin "25") (pinfunction "25_25") (pintype "passive"))
      (node (ref "R41") (pin "1") (pintype "passive"))
      (node (ref "U2") (pin "161") (pinfunction "PB17/TWI2_SCK_161") (pintype "bidirectional"))
    )
    (net (code "213") (name "/TWI2_SDA") (class "Default")
      (node (ref "P1") (pin "26") (pinfunction "26_26") (pintype "passive"))
      (node (ref "R40") (pin "1") (pintype "passive"))
      (node (ref "U2") (pin "160") (pinfunction "PB18/TWI2_SDA_160") (pintype "bidirectional"))
    )
    (net (code "214") (name "/UART1_RX") (class "Default")
      (node (ref "D10") (pin "3") (pinfunction "C_3") (pintype "passive"))
      (node (ref "P1") (pin "22") (pinfunction "22_22") (pintype "passive"))
      (node (ref "P3") (pin "1") (pinfunction "1_1") (pintype "passive"))
      (node (ref "U2") (pin "151") (pinfunction "PG4/UART1_RX/EINT4_151") (pintype "bidirectional"))
    )
    (net (code "215") (name "/UART1_TX") (class "Default")
      (node (ref "D11") (pin "3") (pinfunction "C_3") (pintype "passive"))
      (node (ref "P1") (pin "21") (pinfunction "21_21") (pintype "passive"))
      (node (ref "P3") (pin "2") (pinfunction "2_2") (pintype "passive"))
      (node (ref "U2") (pin "152") (pinfunction "PG3/UART1_TX/EINT3_152") (pintype "bidirectional"))
    )
    (net (code "216") (name "/UBOOT") (class "Default")
      (node (ref "R53") (pin "1") (pintype "passive"))
      (node (ref "SW5") (pin "2") (pinfunction "P2_2") (pintype "passive"))
      (node (ref "U2") (pin "157") (pinfunction "UBOOT_157") (pintype "bidirectional"))
    )
    (net (code "217") (name "/USB0") (class "Default")
      (node (ref "F2") (pin "2") (pinfunction "2_2") (pintype "passive"))
      (node (ref "J1") (pin "3") (pinfunction "D+_3") (pintype "bidirectional"))
      (node (ref "U2") (pin "94") (pinfunction "UDP0_94") (pintype "power_in"))
    )
    (net (code "218") (name "/USB0-DRV") (class "Default")
      (node (ref "R17") (pin "2") (pintype "passive"))
      (node (ref "U2") (pin "10") (pinfunction "PB10/SPI2_CS1/EINT24_10") (pintype "bidirectional"))
      (node (ref "U3") (pin "6") (pinfunction "~{VBUSEN}_6") (pintype "input"))
      (node (ref "U4") (pin "4") (pinfunction "EN_4") (pintype "input"))
    )
    (net (code "219") (name "/USB0_N") (class "Default")
      (node (ref "F1") (pin "2") (pinfunction "2_2") (pintype "passive"))
      (node (ref "J1") (pin "2") (pinfunction "D-_2") (pintype "bidirectional"))
      (node (ref "U2") (pin "93") (pinfunction "UDM0_93") (pintype "power_in"))
    )
    (net (code "220") (name "/USB1") (class "Default")
      (node (ref "F6") (pin "2") (pinfunction "2_2") (pintype "passive"))
      (node (ref "J2") (pin "3") (pinfunction "D+_3") (pintype "bidirectional"))
      (node (ref "U2") (pin "96") (pinfunction "UDP1_96") (pintype "power_in"))
    )
    (net (code "221") (name "/USB1_N") (class "Default")
      (node (ref "F5") (pin "2") (pinfunction "2_2") (pintype "passive"))
      (node (ref "J2") (pin "2") (pinfunction "D-_2") (pintype "bidirectional"))
      (node (ref "U2") (pin "95") (pinfunction "UDM1_95") (pintype "power_in"))
    )
    (net (code "222") (name "/VDD_RTC") (class "Default")
      (node (ref "C61") (pin "1") (pintype "passive"))
      (node (ref "U3") (pin "28") (pinfunction "LDO1_28") (pintype "output"))
    )
    (net (code "223") (name "/VGH") (class "Default")
      (node (ref "C148") (pin "2") (pintype "passive"))
      (node (ref "D7") (pin "A") (pinfunction "A_A") (pintype "passive"))
      (node (ref "J5") (pin "41") (pinfunction "41_41") (pintype "passive"))
      (node (ref "R72") (pin "2") (pintype "passive"))
      (node (ref "R73") (pin "1") (pintype "passive"))
    )
    (net (code "224") (name "/VGL") (class "Default")
      (node (ref "C152") (pin "2") (pintype "passive"))
      (node (ref "D9") (pin "A") (pinfunction "A_A") (pintype "passive"))
      (node (ref "J5") (pin "42") (pinfunction "42_42") (pintype "passive"))
      (node (ref "R74") (pin "2") (pintype "passive"))
      (node (ref "R78") (pin "1") (pintype "passive"))
    )
    (net (code "225") (name "/VINT") (class "Default")
      (node (ref "C56") (pin "2") (pintype "passive"))
      (node (ref "U3") (pin "26") (pinfunction "VINT_26") (pintype "power_in"))
      (node (ref "U3") (pin "27") (pinfunction "LDO1SET_27") (pintype "input"))
    )
    (net (code "226") (name "/VSENSE") (class "Default")
      (node (ref "R29") (pin "1") (pintype "passive"))
      (node (ref "R33") (pin "2") (pintype "passive"))
      (node (ref "U5") (pin "5") (pinfunction "VSENSE_5") (pintype "input"))
    )
    (net (code "227") (name "1.2V_CPU") (class "Default")
      (node (ref "C112") (pin "1") (pintype "passive"))
      (node (ref "C19") (pin "1") (pintype "passive"))
      (node (ref "C20") (pin "1") (pintype "passive"))
      (node (ref "C26") (pin "2") (pintype "passive"))
      (node (ref "C27") (pin "2") (pintype "passive"))
      (node (ref "C28") (pin "2") (pintype "passive"))
      (node (ref "C29") (pin "2") (pintype "passive"))
      (node (ref "C49") (pin "1") (pintype "passive"))
      (node (ref "C50") (pin "1") (pintype "passive"))
      (node (ref "C51") (pin "1") (pintype "passive"))
      (node (ref "C52") (pin "1") (pintype "passive"))
      (node (ref "L2") (pin "2") (pinfunction "2_2") (pintype "passive"))
      (node (ref "U2") (pin "11") (pinfunction "VDD3_CPU_11") (pintype "power_in"))
      (node (ref "U2") (pin "156") (pinfunction "VDD5_CPU_156") (pintype "power_in"))
      (node (ref "U2") (pin "16") (pinfunction "VDD4_CPU_16") (pintype "power_in"))
      (node (ref "U2") (pin "164") (pinfunction "VDD6_CPU_164") (pintype "power_in"))
      (node (ref "U2") (pin "169") (pinfunction "VDD7_CPU_169") (pintype "power_in"))
      (node (ref "U2") (pin "173") (pinfunction "VDD8_CPU_173") (pintype "power_in"))
      (node (ref "U2") (pin "4") (pinfunction "VDD1_CPU_4") (pintype "power_in"))
      (node (ref "U2") (pin "9") (pinfunction "VDD2_CPU_9") (pintype "power_in"))
      (node (ref "U3") (pin "10") (pinfunction "DCDC2_10") (pintype "input"))
    )
    (net (code "228") (name "1.2V_INT") (class "Default")
      (node (ref "C102") (pin "1") (pintype "passive"))
      (node (ref "C30") (pin "2") (pintype "passive"))
      (node (ref "C31") (pin "2") (pintype "passive"))
      (node (ref "C32") (pin "2") (pintype "passive"))
      (node (ref "C37") (pin "1") (pintype "passive"))
      (node (ref "C38") (pin "1") (pintype "passive"))
      (node (ref "C53") (pin "1") (pintype "passive"))
      (node (ref "C54") (pin "1") (pintype "passive"))
      (node (ref "L3") (pin "2") (pinfunction "2_2") (pintype "passive"))
      (node (ref "U2") (pin "109") (pinfunction "VDD4_INT_109") (pintype "power_in"))
      (node (ref "U2") (pin "149") (pinfunction "VDD5_INT_149") (pintype "power_in"))
      (node (ref "U2") (pin "35") (pinfunction "VDD1_INT_35") (pintype "power_in"))
      (node (ref "U2") (pin "73") (pinfunction "VDD2_INT_73") (pintype "power_in"))
      (node (ref "U2") (pin "98") (pinfunction "VDD3_INT_98") (pintype "power_in"))
      (node (ref "U3") (pin "17") (pinfunction "DCDC3_17") (pintype "input"))
    )
    (net (code "229") (name "1.5V") (class "Default")
      (node (ref "C1") (pin "2") (pintype "passive"))
      (node (ref "C107") (pin "2") (pintype "passive"))
      (node (ref "C13") (pin "1") (pintype "passive"))
      (node (ref "C14") (pin "1") (pintype "passive"))
      (node (ref "C15") (pin "1") (pintype "passive"))
      (node (ref "C16") (pin "1") (pintype "passive"))
      (node (ref "C17") (pin "1") (pintype "passive"))
      (node (ref "C18") (pin "1") (pintype "passive"))
      (node (ref "C2") (pin "2") (pintype "passive"))
      (node (ref "C22") (pin "1") (pintype "passive"))
      (node (ref "C33") (pin "2") (pintype "passive"))
      (node (ref "C34") (pin "1") (pintype "passive"))
      (node (ref "C35") (pin "1") (pintype "passive"))
      (node (ref "C36") (pin "1") (pintype "passive"))
      (node (ref "C39") (pin "2") (pintype "passive"))
      (node (ref "C40") (pin "1") (pintype "passive"))
      (node (ref "C41") (pin "2") (pintype "passive"))
      (node (ref "C42") (pin "1") (pintype "passive"))
      (node (ref "C43") (pin "2") (pintype "passive"))
      (node (ref "C44") (pin "1") (pintype "passive"))
      (node (ref "C46") (pin "1") (pintype "passive"))
      (node (ref "C57") (pin "1") (pintype "passive"))
      (node (ref "C59") (pin "1") (pintype "passive"))
      (node (ref "C60") (pin "1") (pintype "passive"))
      (node (ref "C62") (pin "1") (pintype "passive"))
      (node (ref "C69") (pin "1") (pintype "passive"))
      (node (ref "C7") (pin "1") (pintype "passive"))
      (node (ref "C8") (pin "1") (pintype "passive"))
      (node (ref "C87") (pin "2") (pintype "passive"))
      (node (ref "L5") (pin "2") (pinfunction "2_2") (pintype "passive"))
      (node (ref "R2") (pin "2") (pintype "passive"))
      (node (ref "R37") (pin "2") (pintype "passive"))
      (node (ref "R7") (pin "2") (pintype "passive"))
      (node (ref "U1") (pin "A1") (pinfunction "VDDQ_A1") (pintype "power_in"))
      (node (ref "U1") (pin "A8") (pinfunction "VDDQ_A8") (pintype "power_in"))
      (node (ref "U1") (pin "B2") (pinfunction "VDD_B2") (pintype "power_in"))
      (node (ref "U1") (pin "C1") (pinfunction "VDDQ_C1") (pintype "power_in"))
      (node (ref "U1") (pin "C9") (pinfunction "VDDQ_C9") (pintype "power_in"))
      (node (ref "U1") (pin "D2") (pinfunction "VDDQ_D2") (pintype "power_in"))
      (node (ref "U1") (pin "D9") (pinfunction "VDD_D9") (pintype "power_in"))
      (node (ref "U1") (pin "E9") (pinfunction "VDDQ_E9") (pintype "power_in"))
      (node (ref "U1") (pin "F1") (pinfunction "VDDQ_F1") (pintype "power_in"))
      (node (ref "U1") (pin "G7") (pinfunction "VDD_G7") (pintype "power_in"))
      (node (ref "U1") (pin "H2") (pinfunction "VDDQ_H2") (pintype "power_in"))
      (node (ref "U1") (pin "H9") (pinfunction "VDDQ_H9") (pintype "power_in"))
      (node (ref "U1") (pin "K2") (pinfunction "VDD_K2") (pintype "power_in"))
      (node (ref "U1") (pin "K8") (pinfunction "VDD_K8") (pintype "power_in"))
      (node (ref "U1") (pin "N1") (pinfunction "VDD_N1") (pintype "power_in"))
      (node (ref "U1") (pin "N9") (pinfunction "VDD_N9") (pintype "power_in"))
      (node (ref "U1") (pin "R1") (pinfunction "VDD_R1") (pintype "power_in"))
      (node (ref "U1") (pin "R9") (pinfunction "VDD_R9") (pintype "power_in"))
      (node (ref "U2") (pin "23") (pinfunction "VCC1_DRAM_23") (pintype "power_in"))
      (node (ref "U2") (pin "30") (pinfunction "VCC2_DRAM_30") (pintype "power_in"))
      (node (ref "U2") (pin "43") (pinfunction "VCC3_DRAM_43") (pintype "power_in"))
      (node (ref "U2") (pin "53") (pinfunction "VCC4_DRAM_53") (pintype "power_in"))
      (node (ref "U2") (pin "62") (pinfunction "VCC5_DRAM_62") (pintype "power_in"))
    )
    (net (code "230") (name "3.0VA") (class "Default")
      (node (ref "C58") (pin "2") (pintype "passive"))
      (node (ref "C63") (pin "1") (pintype "passive"))
      (node (ref "R39") (pin "1") (pintype "passive"))
      (node (ref "U2") (pin "81") (pinfunction "AVCC_81") (pintype "power_in"))
      (node (ref "U3") (pin "12") (pinfunction "LDO2_12") (pintype "output"))
      (node (ref "U7") (pin "1") (pinfunction "EN_1") (pintype "input"))
    )
    (net (code "231") (name "3.3V") (class "Default")
      (node (ref "C116") (pin "2") (pintype "passive"))
      (node (ref "C117") (pin "2") (pintype "passive"))
      (node (ref "C127") (pin "1") (pintype "passive"))
      (node (ref "C128") (pin "1") (pintype "passive"))
      (node (ref "C161") (pin "1") (pintype "passive"))
      (node (ref "C24") (pin "1") (pintype "passive"))
      (node (ref "C25") (pin "1") (pintype "passive"))
      (node (ref "C47") (pin "1") (pintype "passive"))
      (node (ref "C48") (pin "2") (pintype "passive"))
      (node (ref "C83") (pin "1") (pintype "passive"))
      (node (ref "C95") (pin "1") (pintype "passive"))
      (node (ref "D1") (pin "A") (pinfunction "A_A") (pintype "passive"))
      (node (ref "D10") (pin "2") (pinfunction "K_2") (pintype "passive"))
      (node (ref "D11") (pin "2") (pinfunction "K_2") (pintype "passive"))
      (node (ref "FB4") (pin "1") (pintype "passive"))
      (node (ref "FB5") (pin "1") (pintype "passive"))
      (node (ref "L6") (pin "2") (pinfunction "2_2") (pintype "passive"))
      (node (ref "P1") (pin "27") (pinfunction "27_27") (pintype "passive"))
      (node (ref "P1") (pin "3") (pinfunction "3_3") (pintype "passive"))
      (node (ref "P1") (pin "49") (pinfunction "49_49") (pintype "passive"))
      (node (ref "P2") (pin "1") (pinfunction "1_1") (pintype "passive"))
      (node (ref "P4") (pin "4") (pinfunction "4_4") (pintype "passive"))
      (node (ref "Q2") (pin "S") (pintype "passive"))
      (node (ref "R13") (pin "1") (pintype "passive"))
      (node (ref "R25") (pin "1") (pintype "passive"))
      (node (ref "R40") (pin "2") (pintype "passive"))
      (node (ref "R41") (pin "2") (pintype "passive"))
      (node (ref "R50") (pin "2") (pintype "passive"))
      (node (ref "R51") (pin "2") (pintype "passive"))
      (node (ref "R52") (pin "2") (pintype "passive"))
      (node (ref "R61") (pin "2") (pintype "passive"))
      (node (ref "R79") (pin "2") (pintype "passive"))
      (node (ref "RA24") (pin "1") (pinfunction "1_1") (pintype "passive"))
      (node (ref "RA24") (pin "2") (pinfunction "2_2") (pintype "passive"))
      (node (ref "RA24") (pin "3") (pinfunction "3_3") (pintype "passive"))
      (node (ref "RA24") (pin "4") (pinfunction "4_4") (pintype "passive"))
      (node (ref "RA25") (pin "1") (pinfunction "1_1") (pintype "passive"))
      (node (ref "RA25") (pin "2") (pinfunction "2_2") (pintype "passive"))
      (node (ref "RA25") (pin "3") (pinfunction "3_3") (pintype "passive"))
      (node (ref "RA26") (pin "1") (pinfunction "1_1") (pintype "passive"))
      (node (ref "RA26") (pin "2") (pinfunction "2_2") (pintype "passive"))
      (node (ref "RA26") (pin "3") (pinfunction "3_3") (pintype "passive"))
      (node (ref "RA26") (pin "4") (pinfunction "4_4") (pintype "passive"))
      (node (ref "RA27") (pin "1") (pinfunction "1_1") (pintype "passive"))
      (node (ref "RA27") (pin "2") (pinfunction "2_2") (pintype "passive"))
      (node (ref "RA27") (pin "3") (pinfunction "3_3") (pintype "passive"))
      (node (ref "RA3") (pin "1") (pinfunction "1_1") (pintype "passive"))
      (node (ref "RA3") (pin "2") (pinfunction "2_2") (pintype "passive"))
      (node (ref "RA3") (pin "3") (pinfunction "3_3") (pintype "passive"))
      (node (ref "RA3") (pin "4") (pinfunction "4_4") (pintype "passive"))
      (node (ref "U2") (pin "100") (pinfunction "VCC2_100") (pintype "power_in"))
      (node (ref "U2") (pin "142") (pinfunction "VCC3_142") (pintype "power_in"))
      (node (ref "U2") (pin "163") (pinfunction "VCC4_163") (pintype "power_in"))
      (node (ref "U2") (pin "5") (pinfunction "VCC1_5") (pintype "power_in"))
      (node (ref "U2") (pin "76") (pinfunction "V33_HP_76") (pintype "power_in"))
      (node (ref "U2") (pin "97") (pinfunction "V33_USB_97") (pintype "power_in"))
      (node (ref "U9") (pin "12") (pinfunction "VCC_12") (pintype "power_in"))
      (node (ref "U9") (pin "37") (pinfunction "VCC_37") (pintype "power_in"))
    )
    (net (code "232") (name "ETH_3.3V") (class "Default")
      (node (ref "C66") (pin "1") (pintype "passive"))
      (node (ref "U3") (pin "41") (pinfunction "LDO3_41") (pintype "output"))
    )
    (net (code "233") (name "GND") (class "Default")
      (node (ref "C1") (pin "1") (pintype "passive"))
      (node (ref "C10") (pin "2") (pintype "passive"))
      (node (ref "C100") (pin "1") (pintype "passive"))
      (node (ref "C101") (pin "1") (pintype "passive"))
      (node (ref "C102") (pin "2") (pintype "passive"))
      (node (ref "C103") (pin "1") (pintype "passive"))
      (node (ref "C104") (pin "1") (pintype "passive"))
      (node (ref "C105") (pin "1") (pintype "passive"))
      (node (ref "C106") (pin "2") (pintype "passive"))
      (node (ref "C107") (pin "1") (pintype "passive"))
      (node (ref "C108") (pin "1") (pintype "passive"))
      (node (ref "C109") (pin "2") (pintype "passive"))
      (node (ref "C11") (pin "1") (pintype "passive"))
      (node (ref "C110") (pin "2") (pintype "passive"))
      (node (ref "C111") (pin "2") (pintype "passive"))
      (node (ref "C112") (pin "2") (pintype "passive"))
      (node (ref "C114") (pin "1") (pintype "passive"))
      (node (ref "C115") (pin "1") (pintype "passive"))
      (node (ref "C116") (pin "1") (pintype "passive"))
      (node (ref "C117") (pin "1") (pintype "passive"))
      (node (ref "C118") (pin "2") (pintype "passive"))
      (node (ref "C12") (pin "2") (pintype "passive"))
      (node (ref "C120") (pin "2") (pintype "passive"))
      (node (ref "C126") (pin "2") (pintype "passive"))
      (node (ref "C127") (pin "2") (pintype "passive"))
      (node (ref "C128") (pin "2") (pintype "passive"))
      (node (ref "C129") (pin "2") (pintype "passive"))
      (node (ref "C13") (pin "2") (pintype "passive"))
      (node (ref "C130") (pin "1") (pintype "passive"))
      (node (ref "C131") (pin "1") (pintype "passive"))
      (node (ref "C132") (pin "1") (pintype "passive"))
      (node (ref "C133") (pin "2") (pintype "passive"))
      (node (ref "C134") (pin "2") (pintype "passive"))
      (node (ref "C135") (pin "2") (pintype "passive"))
      (node (ref "C136") (pin "1") (pintype "passive"))
      (node (ref "C137") (pin "1") (pintype "passive"))
      (node (ref "C138") (pin "2") (pintype "passive"))
      (node (ref "C139") (pin "1") (pintype "passive"))
      (node (ref "C14") (pin "2") (pintype "passive"))
      (node (ref "C142") (pin "2") (pintype "passive"))
      (node (ref "C143") (pin "1") (pintype "passive"))
      (node (ref "C144") (pin "1") (pintype "passive"))
      (node (ref "C147") (pin "1") (pintype "passive"))
      (node (ref "C148") (pin "1") (pintype "passive"))
      (node (ref "C149") (pin "1") (pintype "passive"))
      (node (ref "C15") (pin "2") (pintype "passive"))
      (node (ref "C151") (pin "1") (pintype "passive"))
      (node (ref "C152") (pin "1") (pintype "passive"))
      (node (ref "C153") (pin "2") (pintype "passive"))
      (node (ref "C154") (pin "1") (pintype "passive"))
      (node (ref "C155") (pin "2") (pintype "passive"))
      (node (ref "C156") (pin "1") (pintype "passive"))
      (node (ref "C157") (pin "1") (pintype "passive"))
      (node (ref "C158") (pin "-") (pinfunction "-_-") (pintype "passive"))
      (node (ref "C159") (pin "1") (pintype "passive"))
      (node (ref "C16") (pin "2") (pintype "passive"))
      (node (ref "C160") (pin "1") (pintype "passive"))
      (node (ref "C161") (pin "2") (pintype "passive"))
      (node (ref "C17") (pin "2") (pintype "passive"))
      (node (ref "C18") (pin "2") (pintype "passive"))
      (node (ref "C19") (pin "2") (pintype "passive"))
      (node (ref "C20") (pin "2") (pintype "passive"))
      (node (ref "C22") (pin "2") (pintype "passive"))
      (node (ref "C23") (pin "2") (pintype "passive"))
      (node (ref "C24") (pin "2") (pintype "passive"))
      (node (ref "C25") (pin "2") (pintype "passive"))
      (node (ref "C26") (pin "1") (pintype "passive"))
      (node (ref "C27") (pin "1") (pintype "passive"))
      (node (ref "C28") (pin "1") (pintype "passive"))
      (node (ref "C29") (pin "1") (pintype "passive"))
      (node (ref "C3") (pin "1") (pintype "passive"))
      (node (ref "C30") (pin "1") (pintype "passive"))
      (node (ref "C31") (pin "1") (pintype "passive"))
      (node (ref "C32") (pin "1") (pintype "passive"))
      (node (ref "C34") (pin "2") (pintype "passive"))
      (node (ref "C35") (pin "2") (pintype "passive"))
      (node (ref "C36") (pin "2") (pintype "passive"))
      (node (ref "C37") (pin "2") (pintype "passive"))
      (node (ref "C38") (pin "2") (pintype "passive"))
      (node (ref "C39") (pin "1") (pintype "passive"))
      (node (ref "C4") (pin "1") (pintype "passive"))
      (node (ref "C40") (pin "2") (pintype "passive"))
      (node (ref "C41") (pin "1") (pintype "passive"))
      (node (ref "C42") (pin "2") (pintype "passive"))
      (node (ref "C43") (pin "1") (pintype "passive"))
      (node (ref "C44") (pin "2") (pintype "passive"))
      (node (ref "C45") (pin "2") (pintype "passive"))
      (node (ref "C46") (pin "2") (pintype "passive"))
      (node (ref "C47") (pin "2") (pintype "passive"))
      (node (ref "C48") (pin "1") (pintype "passive"))
      (node (ref "C49") (pin "2") (pintype "passive"))
      (node (ref "C5") (pin "1") (pintype "passive"))
      (node (ref "C50") (pin "2") (pintype "passive"))
      (node (ref "C51") (pin "2") (pintype "passive"))
      (node (ref "C52") (pin "2") (pintype "passive"))
      (node (ref "C53") (pin "2") (pintype "passive"))
      (node (ref "C54") (pin "2") (pintype "passive"))
      (node (ref "C55") (pin "1") (pintype "passive"))
      (node (ref "C56") (pin "1") (pintype "passive"))
      (node (ref "C57") (pin "2") (pintype "passive"))
      (node (ref "C58") (pin "1") (pintype "passive"))
      (node (ref "C59") (pin "2") (pintype "passive"))
      (node (ref "C60") (pin "2") (pintype "passive"))
      (node (ref "C61") (pin "2") (pintype "passive"))
      (node (ref "C62") (pin "2") (pintype "passive"))
      (node (ref "C63") (pin "2") (pintype "passive"))
      (node (ref "C64") (pin "1") (pintype "passive"))
      (node (ref "C65") (pin "1") (pintype "passive"))
      (node (ref "C66") (pin "2") (pintype "passive"))
      (node (ref "C67") (pin "1") (pintype "passive"))
      (node (ref "C68") (pin "1") (pintype "passive"))
      (node (ref "C69") (pin "2") (pintype "passive"))
      (node (ref "C7") (pin "2") (pintype "passive"))
      (node (ref "C70") (pin "1") (pintype "passive"))
      (node (ref "C71") (pin "1") (pintype "passive"))
      (node (ref "C72") (pin "1") (pintype "passive"))
      (node (ref "C73") (pin "2") (pintype "passive"))
      (node (ref "C74") (pin "1") (pintype "passive"))
      (node (ref "C75") (pin "1") (pintype "passive"))
      (node (ref "C76") (pin "1") (pintype "passive"))
      (node (ref "C77") (pin "2") (pintype "passive"))
      (node (ref "C78") (pin "1") (pintype "passive"))
      (node (ref "C79") (pin "1") (pintype "passive"))
      (node (ref "C8") (pin "2") (pintype "passive"))
      (node (ref "C80") (pin "2") (pintype "passive"))
      (node (ref "C81") (pin "1") (pintype "passive"))
      (node (ref "C83") (pin "2") (pintype "passive"))
      (node (ref "C84") (pin "1") (pintype "passive"))
      (node (ref "C85") (pin "-") (pinfunction "-_-") (pintype "passive"))
      (node (ref "C86") (pin "1") (pintype "passive"))
      (node (ref "C87") (pin "1") (pintype "passive"))
      (node (ref "C88") (pin "1") (pintype "passive"))
      (node (ref "C89") (pin "1") (pintype "passive"))
      (node (ref "C9") (pin "2") (pintype "passive"))
      (node (ref "C90") (pin "2") (pintype "passive"))
      (node (ref "C91") (pin "2") (pintype "passive"))
      (node (ref "C92") (pin "1") (pintype "passive"))
      (node (ref "C94") (pin "1") (pintype "passive"))
      (node (ref "C95") (pin "2") (pintype "passive"))
      (node (ref "C96") (pin "1") (pintype "passive"))
      (node (ref "C97") (pin "1") (pintype "passive"))
      (node (ref "C98") (pin "2") (pintype "passive"))
      (node (ref "C99") (pin "1") (pintype "passive"))
      (node (ref "D10") (pin "1") (pinfunction "A_1") (pintype "passive"))
      (node (ref "D11") (pin "1") (pinfunction "A_1") (pintype "passive"))
      (node (ref "D7") (pin "K") (pinfunction "K_K") (pintype "passive"))
      (node (ref "D8") (pin "2") (pinfunction "K_2") (pintype "passive"))
      (node (ref "D9") (pin "K") (pinfunction "K_K") (pintype "passive"))
      (node (ref "F1") (pin "1") (pinfunction "1_1") (pintype "passive"))
      (node (ref "F10") (pin "1") (pinfunction "1_1") (pintype "passive"))
      (node (ref "F11") (pin "2") (pinfunction "2_2") (pintype "passive"))
      (node (ref "F12") (pin "2") (pinfunction "2_2") (pintype "passive"))
      (node (ref "F13") (pin "2") (pinfunction "2_2") (pintype "passive"))
      (node (ref "F14") (pin "2") (pinfunction "2_2") (pintype "passive"))
      (node (ref "F15") (pin "2") (pinfunction "2_2") (pintype "passive"))
      (node (ref "F16") (pin "2") (pinfunction "2_2") (pintype "passive"))
      (node (ref "F17") (pin "2") (pinfunction "2_2") (pintype "passive"))
      (node (ref "F18") (pin "2") (pinfunction "2_2") (pintype "passive"))
      (node (ref "F19") (pin "2") (pinfunction "2_2") (pintype "passive"))
      (node (ref "F2") (pin "1") (pinfunction "1_1") (pintype "passive"))
      (node (ref "F20") (pin "2") (pinfunction "2_2") (pintype "passive"))
      (node (ref "F21") (pin "2") (pinfunction "2_2") (pintype "passive"))
      (node (ref "F22") (pin "2") (pinfunction "2_2") (pintype "passive"))
      (node (ref "F23") (pin "2") (pinfunction "2_2") (pintype "passive"))
      (node (ref "F24") (pin "2") (pinfunction "2_2") (pintype "passive"))
      (node (ref "F3") (pin "1") (pinfunction "1_1") (pintype "passive"))
      (node (ref "F4") (pin "1") (pinfunction "1_1") (pintype "passive"))
      (node (ref "F5") (pin "1") (pinfunction "1_1") (pintype "passive"))
      (node (ref "F6") (pin "1") (pinfunction "1_1") (pintype "passive"))
      (node (ref "F7") (pin "1") (pinfunction "1_1") (pintype "passive"))
      (node (ref "F8") (pin "1") (pinfunction "1_1") (pintype "passive"))
      (node (ref "F9") (pin "1") (pinfunction "1_1") (pintype "passive"))
      (node (ref "J1") (pin "5") (pinfunction "GND_5") (pintype "power_in"))
      (node (ref "J1") (pin "6") (pinfunction "S1_6") (pintype "passive"))
      (node (ref "J1") (pin "7") (pinfunction "S2_7") (pintype "power_in"))
      (node (ref "J1") (pin "8") (pinfunction "S3_8") (pintype "power_in"))
      (node (ref "J1") (pin "9") (pinfunction "S4_9") (pintype "power_in"))
      (node (ref "J10") (pin "11") (pinfunction "GND_Shield_11") (pintype "passive"))
      (node (ref "J10") (pin "12") (pinfunction "GND_Shield_12") (pintype "passive"))
      (node (ref "J10") (pin "6") (pinfunction "GND_6") (pintype "power_in"))
      (node (ref "J2") (pin "4") (pinfunction "GND_4") (pintype "power_in"))
      (node (ref "J2") (pin "5") (pinfunction "S1_5") (pintype "power_in"))
      (node (ref "J2") (pin "6") (pinfunction "S2_6") (pintype "passive"))
      (node (ref "J3") (pin "1") (pinfunction "1_1") (pintype "power_in"))
      (node (ref "J3") (pin "5") (pinfunction "5_5") (pintype "power_in"))
      (node (ref "J4") (pin "29") (pinfunction "29_29") (pintype "passive"))
      (node (ref "J4") (pin "3") (pinfunction "3_3") (pintype "passive"))
      (node (ref "J4") (pin "36") (pinfunction "36_36") (pintype "passive"))
      (node (ref "J4") (pin "41") (pinfunction "MH1_41") (pintype "passive"))
      (node (ref "J4") (pin "42") (pinfunction "MH2_42") (pintype "passive"))
      (node (ref "J5") (pin "36") (pinfunction "36_36") (pintype "passive"))
      (node (ref "J5") (pin "38") (pinfunction "38_38") (pintype "passive"))
      (node (ref "J5") (pin "48") (pinfunction "48_48") (pintype "passive"))
      (node (ref "J5") (pin "5") (pinfunction "5_5") (pintype "passive"))
      (node (ref "J5") (pin "51") (pinfunction "MH1_51") (pintype "passive"))
      (node (ref "J5") (pin "52") (pinfunction "MH2_52") (pintype "passive"))
      (node (ref "J8") (pin "2") (pinfunction "2_2") (pintype "passive"))
      (node (ref "J8") (pin "3") (pinfunction "3_3") (pintype "passive"))
      (node (ref "J9") (pin "11") (pinfunction "GND_Shield_11") (pintype "passive"))
      (node (ref "J9") (pin "12") (pinfunction "GND_Shield_12") (pintype "passive"))
      (node (ref "J9") (pin "6") (pinfunction "GND_6") (pintype "power_in"))
      (node (ref "P1") (pin "28") (pinfunction "28_28") (pintype "passive"))
      (node (ref "P1") (pin "4") (pinfunction "4_4") (pintype "passive"))
      (node (ref "P1") (pin "41") (pinfunction "41_41") (pintype "passive"))
      (node (ref "P1") (pin "42") (pinfunction "42_42") (pintype "passive"))
      (node (ref "P1") (pin "50") (pinfunction "50_50") (pintype "passive"))
      (node (ref "P1") (pin "6") (pinfunction "6_6") (pintype "passive"))
      (node (ref "P2") (pin "7") (pinfunction "7_7") (pintype "passive"))
      (node (ref "P3") (pin "3") (pinfunction "3_3") (pintype "passive"))
      (node (ref "P4") (pin "2") (pinfunction "2_2") (pintype "passive"))
      (node (ref "P6") (pin "2") (pinfunction "2_2") (pintype "passive"))
      (node (ref "Q3") (pin "2") (pinfunction "E_2") (pintype "passive"))
      (node (ref "R1") (pin "1") (pintype "passive"))
      (node (ref "R10") (pin "1") (pintype "passive"))
      (node (ref "R11") (pin "1") (pintype "passive"))
      (node (ref "R15") (pin "1") (pintype "passive"))
      (node (ref "R17") (pin "1") (pintype "passive"))
      (node (ref "R19") (pin "2") (pintype "passive"))
      (node (ref "R21") (pin "1") (pintype "passive"))
      (node (ref "R22") (pin "1") (pintype "passive"))
      (node (ref "R3") (pin "2") (pintype "passive"))
      (node (ref "R30") (pin "2") (pintype "passive"))
      (node (ref "R32") (pin "1") (pintype "passive"))
      (node (ref "R33") (pin "1") (pintype "passive"))
      (node (ref "R42") (pin "1") (pintype "passive"))
      (node (ref "R54") (pin "2") (pintype "passive"))
      (node (ref "R55") (pin "2") (pintype "passive"))
      (node (ref "R56") (pin "2") (pintype "passive"))
      (node (ref "R57") (pin "2") (pintype "passive"))
      (node (ref "R58") (pin "1") (pintype "passive"))
      (node (ref "R64") (pin "2") (pintype "passive"))
      (node (ref "R65") (pin "2") (pintype "passive"))
      (node (ref "R68") (pin "1") (pintype "passive"))
      (node (ref "R71") (pin "1") (pintype "passive"))
      (node (ref "R73") (pin "2") (pintype "passive"))
      (node (ref "R75") (pin "1") (pintype "passive"))
      (node (ref "R76") (pin "1") (pintype "passive"))
      (node (ref "R77") (pin "1") (pintype "passive"))
      (node (ref "R78") (pin "2") (pintype "passive"))
      (node (ref "R9") (pin "2") (pintype "passive"))
      (node (ref "SW1") (pin "1") (pinfunction "P1_1") (pintype "passive"))
      (node (ref "SW3") (pin "1") (pinfunction "P1_1") (pintype "passive"))
      (node (ref "SW4") (pin "1") (pinfunction "P1_1") (pintype "passive"))
      (node (ref "SW5") (pin "1") (pinfunction "P1_1") (pintype "passive"))
      (node (ref "U1") (pin "A9") (pinfunction "VSS_A9") (pintype "power_in"))
      (node (ref "U1") (pin "B1") (pinfunction "VSSQ_B1") (pintype "power_in"))
      (node (ref "U1") (pin "B3") (pinfunction "VSS_B3") (pintype "power_in"))
      (node (ref "U1") (pin "B9") (pinfunction "VSSQ_B9") (pintype "power_in"))
      (node (ref "U1") (pin "D1") (pinfunction "VSSQ_D1") (pintype "power_in"))
      (node (ref "U1") (pin "D8") (pinfunction "VSSQ_D8") (pintype "power_in"))
      (node (ref "U1") (pin "E1") (pinfunction "VSS_E1") (pintype "power_in"))
      (node (ref "U1") (pin "E2") (pinfunction "VSSQ_E2") (pintype "power_in"))
      (node (ref "U1") (pin "E8") (pinfunction "VSSQ_E8") (pintype "power_in"))
      (node (ref "U1") (pin "F9") (pinfunction "VSSQ_F9") (pintype "power_in"))
      (node (ref "U1") (pin "G1") (pinfunction "VSSQ_G1") (pintype "power_in"))
      (node (ref "U1") (pin "G8") (pinfunction "VSS_G8") (pintype "power_in"))
      (node (ref "U1") (pin "G9") (pinfunction "VSSQ_G9") (pintype "power_in"))
      (node (ref "U1") (pin "J2") (pinfunction "VSS_J2") (pintype "power_in"))
      (node (ref "U1") (pin "J8") (pinfunction "VSS_J8") (pintype "power_in"))
      (node (ref "U1") (pin "L2") (pinfunction "CS_N_L2") (pintype "input"))
      (node (ref "U1") (pin "M1") (pinfunction "VSS_M1") (pintype "power_in"))
      (node (ref "U1") (pin "M9") (pinfunction "VSS_M9") (pintype "power_in"))
      (node (ref "U1") (pin "P1") (pinfunction "VSS_P1") (pintype "input"))
      (node (ref "U1") (pin "P9") (pinfunction "VSS_P9") (pintype "power_in"))
      (node (ref "U1") (pin "T1") (pinfunction "VSS_T1") (pintype "power_in"))
      (node (ref "U1") (pin "T9") (pinfunction "VSS_T9") (pintype "power_in"))
      (node (ref "U10") (pin "2") (pinfunction "GND_2") (pintype "power_in"))
      (node (ref "U11") (pin "4") (pinfunction "PGND_4") (pintype "power_in"))
      (node (ref "U12") (pin "4") (pinfunction "PGND_4") (pintype "power_in"))
      (node (ref "U13") (pin "4") (pinfunction "GND_4") (pintype "power_in"))
      (node (ref "U2") (pin "79") (pinfunction "AGND_79") (pintype "power_in"))
      (node (ref "U2") (pin "GND_PAD") (pinfunction "GND_GND_PAD") (pintype "power_in"))
      (node (ref "U3") (pin "16") (pinfunction "PGND3_16") (pintype "input"))
      (node (ref "U3") (pin "22") (pinfunction "AGND_22") (pintype "power_in"))
      (node (ref "U3") (pin "46") (pinfunction "PGND1_46") (pintype "power_in"))
      (node (ref "U3") (pin "49") (pinfunction "TH_PAD_49") (pintype "power_in"))
      (node (ref "U3") (pin "9") (pinfunction "PGND2_9") (pintype "input"))
      (node (ref "U4") (pin "2") (pinfunction "GND_2") (pintype "power_in"))
      (node (ref "U5") (pin "4") (pinfunction "GND_4") (pintype "power_in"))
      (node (ref "U5") (pin "9") (pinfunction "PAD_9") (pintype "power_in"))
      (node (ref "U6") (pin "2") (pinfunction "GND_2") (pintype "power_in"))
      (node (ref "U7") (pin "2") (pinfunction "GND_2") (pintype "power_in"))
      (node (ref "U9") (pin "13") (pinfunction "VSS_13") (pintype "power_in"))
      (node (ref "U9") (pin "36") (pinfunction "VSS_36") (pintype "power_in"))
    )
    (net (code "234") (name "IPSOUT") (class "Default")
      (node (ref "C104") (pin "2") (pintype "passive"))
      (node (ref "C105") (pin "2") (pintype "passive"))
      (node (ref "C114") (pin "2") (pintype "passive"))
      (node (ref "C115") (pin "2") (pintype "passive"))
      (node (ref "C12") (pin "1") (pintype "passive"))
      (node (ref "C130") (pin "2") (pintype "passive"))
      (node (ref "C131") (pin "2") (pintype "passive"))
      (node (ref "C137") (pin "2") (pintype "passive"))
      (node (ref "C138") (pin "1") (pintype "passive"))
      (node (ref "C144") (pin "2") (pintype "passive"))
      (node (ref "C23") (pin "1") (pintype "passive"))
      (node (ref "C4") (pin "2") (pintype "passive"))
      (node (ref "C45") (pin "1") (pintype "passive"))
      (node (ref "C67") (pin "2") (pintype "passive"))
      (node (ref "L7") (pin "1") (pinfunction "1_1") (pintype "passive"))
      (node (ref "L8") (pin "1") (pinfunction "1_1") (pintype "passive"))
      (node (ref "L9") (pin "1") (pinfunction "1_1") (pintype "passive"))
      (node (ref "LED1") (pin "A") (pinfunction "A_A") (pintype "passive"))
      (node (ref "SW2") (pin "1") (pinfunction "P1_1") (pintype "passive"))
      (node (ref "U10") (pin "4") (pinfunction "VIN_4") (pintype "power_in"))
      (node (ref "U11") (pin "6") (pinfunction "IN_6") (pintype "power_in"))
      (node (ref "U11") (pin "7") (pinfunction "FREQ_7") (pintype "input"))
      (node (ref "U12") (pin "6") (pinfunction "IN_6") (pintype "power_in"))
      (node (ref "U12") (pin "7") (pinfunction "FREQ_7") (pintype "input"))
      (node (ref "U13") (pin "1") (pinfunction "VIN_1") (pintype "power_in"))
      (node (ref "U3") (pin "13") (pinfunction "LDO24IN_13") (pintype "power_in"))
      (node (ref "U3") (pin "14") (pinfunction "VIN3_14") (pintype "power_in"))
      (node (ref "U3") (pin "21") (pinfunction "APS_21") (pintype "power_in"))
      (node (ref "U3") (pin "34") (pinfunction "IPSOUT_34") (pintype "passive"))
      (node (ref "U3") (pin "35") (pinfunction "IPSOUT_35") (pintype "passive"))
      (node (ref "U3") (pin "40") (pinfunction "LDO3IN_40") (pintype "output"))
      (node (ref "U3") (pin "44") (pinfunction "VIN1_44") (pintype "power_in"))
      (node (ref "U3") (pin "7") (pinfunction "VIN2_7") (pintype "power_in"))
      (node (ref "U7") (pin "4") (pinfunction "VIN_4") (pintype "power_in"))
    )
    (net (code "235") (name "LCD_AVDD") (class "Default")
      (node (ref "C134") (pin "1") (pintype "passive"))
      (node (ref "C139") (pin "2") (pintype "passive"))
      (node (ref "D4") (pin "K") (pinfunction "K_K") (pintype "passive"))
      (node (ref "D6") (pin "1") (pinfunction "A_1") (pintype "passive"))
      (node (ref "J5") (pin "43") (pinfunction "43_43") (pintype "passive"))
      (node (ref "P4") (pin "1") (pinfunction "1_1") (pintype "passive"))
      (node (ref "R59") (pin "1") (pintype "passive"))
      (node (ref "R60") (pin "1") (pintype "passive"))
      (node (ref "R69") (pin "2") (pintype "passive"))
    )
    (net (code "236") (name "LCD_VCC") (class "Default")
      (node (ref "C159") (pin "2") (pintype "passive"))
      (node (ref "C160") (pin "2") (pintype "passive"))
      (node (ref "J4") (pin "4") (pinfunction "4_4") (pintype "passive"))
      (node (ref "J5") (pin "7") (pinfunction "7_7") (pintype "passive"))
      (node (ref "Q2") (pin "D") (pintype "passive"))
      (node (ref "R23") (pin "1") (pintype "passive"))
      (node (ref "R44") (pin "1") (pintype "passive"))
      (node (ref "R45") (pin "1") (pintype "passive"))
      (node (ref "R46") (pin "1") (pintype "passive"))
      (node (ref "R47") (pin "1") (pintype "passive"))
      (node (ref "R48") (pin "1") (pintype "passive"))
      (node (ref "R49") (pin "1") (pintype "passive"))
    )
    (net (code "237") (name "MAIN_IN") (class "Default")
      (node (ref "C158") (pin "+") (pinfunction "+_+") (pintype "passive"))
      (node (ref "C84") (pin "2") (pintype "passive"))
      (node (ref "D12") (pin "K") (pinfunction "K_K") (pintype "passive"))
      (node (ref "F4") (pin "2") (pinfunction "2_2") (pintype "passive"))
      (node (ref "P1") (pin "2") (pinfunction "2_2") (pintype "passive"))
      (node (ref "U5") (pin "2") (pinfunction "VIN_2") (pintype "power_in"))
    )
    (net (code "238") (name "Net-(C5-Pad2)") (class "Default")
      (node (ref "C5") (pin "2") (pintype "passive"))
      (node (ref "R5") (pin "1") (pintype "passive"))
    )
    (net (code "239") (name "Net-(C11-Pad2)") (class "Default")
      (node (ref "C11") (pin "2") (pintype "passive"))
      (node (ref "R6") (pin "1") (pintype "passive"))
    )
    (net (code "240") (name "Net-(C90-Pad1)") (class "Default")
      (node (ref "C90") (pin "1") (pintype "passive"))
      (node (ref "R26") (pin "1") (pintype "passive"))
      (node (ref "R27") (pin "2") (pintype "passive"))
    )
    (net (code "241") (name "Net-(C96-Pad2)") (class "Default")
      (node (ref "C96") (pin "2") (pintype "passive"))
      (node (ref "R28") (pin "1") (pintype "passive"))
    )
    (net (code "242") (name "Net-(C106-Pad1)") (class "Default")
      (node (ref "C106") (pin "1") (pintype "passive"))
      (node (ref "C132") (pin "2") (pintype "passive"))
      (node (ref "C133") (pin "1") (pintype "passive"))
      (node (ref "D3") (pin "K") (pinfunction "K_K") (pintype "passive"))
      (node (ref "Q1") (pin "S") (pintype "passive"))
      (node (ref "R66") (pin "2") (pintype "passive"))
    )
    (net (code "243") (name "Net-(C109-Pad1)") (class "Default")
      (node (ref "C109") (pin "1") (pintype "passive"))
      (node (ref "R34") (pin "1") (pintype "passive"))
    )
    (net (code "244") (name "Net-(C110-Pad1)") (class "Default")
      (node (ref "C110") (pin "1") (pintype "passive"))
      (node (ref "R35") (pin "1") (pintype "passive"))
    )
    (net (code "245") (name "Net-(C111-Pad1)") (class "Default")
      (node (ref "C111") (pin "1") (pintype "passive"))
      (node (ref "R36") (pin "1") (pintype "passive"))
    )
    (net (code "246") (name "Net-(C136-Pad2)") (class "Default")
      (node (ref "C136") (pin "2") (pintype "passive"))
      (node (ref "R67") (pin "1") (pintype "passive"))
    )
    (net (code "247") (name "Net-(C143-Pad2)") (class "Default")
      (node (ref "C143") (pin "2") (pintype "passive"))
      (node (ref "R70") (pin "1") (pintype "passive"))
    )
    (net (code "248") (name "Net-(D1-PadK)") (class "Default")
      (node (ref "D1") (pin "K") (pinfunction "K_K") (pintype "passive"))
      (node (ref "R16") (pin "1") (pintype "passive"))
    )
    (net (code "249") (name "Net-(D6-C)") (class "Default")
      (node (ref "C145") (pin "1") (pintype "passive"))
      (node (ref "D6") (pin "3") (pinfunction "C_3") (pintype "passive"))
    )
    (net (code "250") (name "Net-(D6-K)") (class "Default")
      (node (ref "C147") (pin "2") (pintype "passive"))
      (node (ref "D6") (pin "2") (pinfunction "K_2") (pintype "passive"))
      (node (ref "R72") (pin "1") (pintype "passive"))
    )
    (net (code "251") (name "Net-(D8-A)") (class "Default")
      (node (ref "C151") (pin "2") (pintype "passive"))
      (node (ref "D8") (pin "1") (pinfunction "A_1") (pintype "passive"))
      (node (ref "R74") (pin "1") (pintype "passive"))
    )
    (net (code "252") (name "Net-(D8-C)") (class "Default")
      (node (ref "C150") (pin "1") (pintype "passive"))
      (node (ref "D8") (pin "3") (pinfunction "C_3") (pintype "passive"))
    )
    (net (code "253") (name "Net-(D12-PadA)") (class "Default")
      (node (ref "D12") (pin "A") (pinfunction "A_A") (pintype "passive"))
      (node (ref "J8") (pin "4") (pinfunction "4_4") (pintype "passive"))
    )
    (net (code "254") (name "Net-(J2-VBus)") (class "Default")
      (node (ref "FB2") (pin "2") (pintype "passive"))
      (node (ref "J2") (pin "1") (pinfunction "VBus_1") (pintype "power_in"))
    )
    (net (code "255") (name "Net-(J10-VCC)") (class "Default")
      (node (ref "C155") (pin "1") (pintype "passive"))
      (node (ref "C156") (pin "2") (pintype "passive"))
      (node (ref "FB5") (pin "2") (pintype "passive"))
      (node (ref "J10") (pin "4") (pinfunction "VCC_4") (pintype "power_in"))
    )
    (net (code "256") (name "Net-(LED1-PadK)") (class "Default")
      (node (ref "LED1") (pin "K") (pinfunction "K_K") (pintype "passive"))
      (node (ref "R8") (pin "1") (pintype "passive"))
    )
    (net (code "257") (name "Net-(Q3-C)") (class "Default")
      (node (ref "Q2") (pin "G") (pintype "passive"))
      (node (ref "Q3") (pin "3") (pinfunction "C_3") (pintype "passive"))
      (node (ref "R79") (pin "1") (pintype "passive"))
    )
    (net (code "258") (name "Net-(R24-Pad1)") (class "Default")
      (node (ref "R24") (pin "1") (pintype "passive"))
      (node (ref "R29") (pin "2") (pintype "passive"))
    )
    (net (code "259") (name "Net-(SW4-P2)") (class "Default")
      (node (ref "R43") (pin "1") (pintype "passive"))
      (node (ref "R53") (pin "2") (pintype "passive"))
      (node (ref "SW4") (pin "2") (pinfunction "P2_2") (pintype "passive"))
    )
    (net (code "260") (name "Net-(U1A-ZQ)") (class "Default")
      (node (ref "R10") (pin "2") (pintype "passive"))
      (node (ref "U1") (pin "L8") (pinfunction "ZQ_L8") (pintype "input"))
    )
    (net (code "261") (name "Net-(U1B-VREFCA)") (class "Default")
      (node (ref "C2") (pin "1") (pintype "passive"))
      (node (ref "C3") (pin "2") (pintype "passive"))
      (node (ref "R2") (pin "1") (pintype "passive"))
      (node (ref "R3") (pin "1") (pintype "passive"))
      (node (ref "U1") (pin "H1") (pinfunction "VREFDQ_H1") (pintype "input"))
      (node (ref "U1") (pin "M8") (pinfunction "VREFCA_M8") (pintype "input"))
    )
    (net (code "262") (name "Net-(U2-DZQ)") (class "Default")
      (node (ref "R22") (pin "2") (pintype "passive"))
      (node (ref "U2") (pin "17") (pinfunction "DZQ_17") (pintype "passive"))
    )
    (net (code "263") (name "Net-(U2-HPBP)") (class "Default")
      (node (ref "C97") (pin "2") (pintype "passive"))
      (node (ref "C98") (pin "1") (pintype "passive"))
      (node (ref "U2") (pin "75") (pinfunction "HPBP_75") (pintype "power_in"))
    )
    (net (code "264") (name "Net-(U2-MICIN1)") (class "Default")
      (node (ref "C93") (pin "2") (pintype "passive"))
      (node (ref "U2") (pin "84") (pinfunction "MICIN1_84") (pintype "power_in"))
    )
    (net (code "265") (name "Net-(U2-PD2{slash}LCD_D2)") (class "Default")
      (node (ref "RA13") (pin "8") (pinfunction "8_8") (pintype "passive"))
      (node (ref "U2") (pin "148") (pinfunction "PD2/LCD_D2_148") (pintype "bidirectional"))
    )
    (net (code "266") (name "Net-(U2-PD3{slash}LCD_D3)") (class "Default")
      (node (ref "RA13") (pin "7") (pinfunction "7_7") (pintype "passive"))
      (node (ref "U2") (pin "147") (pinfunction "PD3/LCD_D3_147") (pintype "output"))
    )
    (net (code "267") (name "Net-(U2-PD4{slash}LCD_D4)") (class "Default")
      (node (ref "RA13") (pin "6") (pinfunction "6_6") (pintype "passive"))
      (node (ref "U2") (pin "146") (pinfunction "PD4/LCD_D4_146") (pintype "output"))
    )
    (net (code "268") (name "Net-(U2-PD5{slash}LCD_D5)") (class "Default")
      (node (ref "RA13") (pin "5") (pinfunction "5_5") (pintype "passive"))
      (node (ref "U2") (pin "145") (pinfunction "PD5/LCD_D5_145") (pintype "output"))
    )
    (net (code "269") (name "Net-(U2-PD6{slash}LCD_D6)") (class "Default")
      (node (ref "RA30") (pin "4") (pinfunction "4_4") (pintype "passive"))
      (node (ref "U2") (pin "144") (pinfunction "PD6/LCD_D6_144") (pintype "output"))
    )
    (net (code "270") (name "Net-(U2-PD7{slash}LCD_D7)") (class "Default")
      (node (ref "RA30") (pin "3") (pinfunction "3_3") (pintype "passive"))
      (node (ref "U2") (pin "143") (pinfunction "PD7/LCD_D7_143") (pintype "output"))
    )
    (net (code "271") (name "Net-(U2-PD10{slash}LCD_D10)") (class "Default")
      (node (ref "RA16") (pin "6") (pinfunction "6_6") (pintype "passive"))
      (node (ref "U2") (pin "141") (pinfunction "PD10/LCD_D10_141") (pintype "output"))
    )
    (net (code "272") (name "Net-(U2-PD11{slash}LCD_D11)") (class "Default")
      (node (ref "RA16") (pin "5") (pinfunction "5_5") (pintype "passive"))
      (node (ref "U2") (pin "140") (pinfunction "PD11/LCD_D11_140") (pintype "output"))
    )
    (net (code "273") (name "Net-(U2-PD12{slash}LCD_D12)") (class "Default")
      (node (ref "RA14") (pin "8") (pinfunction "8_8") (pintype "passive"))
      (node (ref "U2") (pin "139") (pinfunction "PD12/LCD_D12_139") (pintype "output"))
    )
    (net (code "274") (name "Net-(U2-PD13{slash}LCD_D13)") (class "Default")
      (node (ref "RA14") (pin "7") (pinfunction "7_7") (pintype "passive"))
      (node (ref "U2") (pin "138") (pinfunction "PD13/LCD_D13_138") (pintype "output"))
    )
    (net (code "275") (name "Net-(U2-PD14{slash}LCD_D14)") (class "Default")
      (node (ref "RA14") (pin "6") (pinfunction "6_6") (pintype "passive"))
      (node (ref "U2") (pin "137") (pinfunction "PD14/LCD_D14_137") (pintype "output"))
    )
    (net (code "276") (name "Net-(U2-PD15{slash}LCD_D15)") (class "Default")
      (node (ref "RA14") (pin "5") (pinfunction "5_5") (pintype "passive"))
      (node (ref "U2") (pin "136") (pinfunction "PD15/LCD_D15_136") (pintype "output"))
    )
    (net (code "277") (name "Net-(U2-PD18{slash}LCD_D18)") (class "Default")
      (node (ref "RA15") (pin "8") (pinfunction "8_8") (pintype "passive"))
      (node (ref "U2") (pin "135") (pinfunction "PD18/LCD_D18_135") (pintype "output"))
    )
    (net (code "278") (name "Net-(U2-PD19{slash}LCD_D19)") (class "Default")
      (node (ref "RA15") (pin "7") (pinfunction "7_7") (pintype "passive"))
      (node (ref "U2") (pin "134") (pinfunction "PD19/LCD_D19_134") (pintype "output"))
    )
    (net (code "279") (name "Net-(U2-PD20{slash}LCD_D20)") (class "Default")
      (node (ref "RA15") (pin "6") (pinfunction "6_6") (pintype "passive"))
      (node (ref "U2") (pin "133") (pinfunction "PD20/LCD_D20_133") (pintype "output"))
    )
    (net (code "280") (name "Net-(U2-PD21{slash}LCD_D21)") (class "Default")
      (node (ref "RA15") (pin "5") (pinfunction "5_5") (pintype "passive"))
      (node (ref "U2") (pin "132") (pinfunction "PD21/LCD_D21_132") (pintype "output"))
    )
    (net (code "281") (name "Net-(U2-PD22{slash}LCD_D22)") (class "Default")
      (node (ref "RA16") (pin "8") (pinfunction "8_8") (pintype "passive"))
      (node (ref "U2") (pin "131") (pinfunction "PD22/LCD_D22_131") (pintype "output"))
    )
    (net (code "282") (name "Net-(U2-PD23{slash}LCD_CLK)") (class "Default")
      (node (ref "RA17") (pin "8") (pinfunction "8_8") (pintype "passive"))
      (node (ref "U2") (pin "129") (pinfunction "PD23/LCD_CLK_129") (pintype "output"))
    )
    (net (code "283") (name "Net-(U2-PD23{slash}LCD_D23)") (class "Default")
      (node (ref "RA16") (pin "7") (pinfunction "7_7") (pintype "passive"))
      (node (ref "U2") (pin "130") (pinfunction "PD23/LCD_D23_130") (pintype "output"))
    )
    (net (code "284") (name "Net-(U2-PD25{slash}LCD_DE)") (class "Default")
      (node (ref "RA17") (pin "5") (pinfunction "5_5") (pintype "passive"))
      (node (ref "U2") (pin "128") (pinfunction "PD25/LCD_DE_128") (pintype "output"))
    )
    (net (code "285") (name "Net-(U2-PD26{slash}LCD_HSYNC)") (class "Default")
      (node (ref "RA17") (pin "7") (pinfunction "7_7") (pintype "passive"))
      (node (ref "U2") (pin "127") (pinfunction "PD26/LCD_HSYNC_127") (pintype "output"))
    )
    (net (code "286") (name "Net-(U2-PD27{slash}LCD_VSYNC)") (class "Default")
      (node (ref "RA17") (pin "6") (pinfunction "6_6") (pintype "passive"))
      (node (ref "U2") (pin "126") (pinfunction "PD27/LCD_VSYNC_126") (pintype "output"))
    )
    (net (code "287") (name "Net-(U2-PE0{slash}CSI_PCLK{slash}SPI2_CS0{slash}EINT14)") (class "Default")
      (node (ref "RA18") (pin "8") (pinfunction "8_8") (pintype "passive"))
      (node (ref "U2") (pin "114") (pinfunction "PE0/CSI_PCLK/SPI2_CS0/EINT14_114") (pintype "output"))
    )
    (net (code "288") (name "Net-(U2-PE1{slash}CSI_MCLK{slash}SPI2_CLK{slash}EINT15)") (class "Default")
      (node (ref "RA18") (pin "7") (pinfunction "7_7") (pintype "passive"))
      (node (ref "U2") (pin "115") (pinfunction "PE1/CSI_MCLK/SPI2_CLK/EINT15_115") (pintype "output"))
    )
    (net (code "289") (name "Net-(U2-PE2{slash}CSI_HSYNC{slash}SPI2_MOSI)") (class "Default")
      (node (ref "RA18") (pin "6") (pinfunction "6_6") (pintype "passive"))
      (node (ref "U2") (pin "116") (pinfunction "PE2/CSI_HSYNC/SPI2_MOSI_116") (pintype "output"))
    )
    (net (code "290") (name "Net-(U2-PE3{slash}CSI_VSYNC{slash}SPI2_MISO)") (class "Default")
      (node (ref "RA18") (pin "5") (pinfunction "5_5") (pintype "passive"))
      (node (ref "U2") (pin "117") (pinfunction "PE3/CSI_VSYNC/SPI2_MISO_117") (pintype "output"))
    )
    (net (code "291") (name "Net-(U2-PE4{slash}CSI_D0{slash}SDC2_D0)") (class "Default")
      (node (ref "RA19") (pin "8") (pinfunction "8_8") (pintype "passive"))
      (node (ref "U2") (pin "118") (pinfunction "PE4/CSI_D0/SDC2_D0_118") (pintype "output"))
    )
    (net (code "292") (name "Net-(U2-PE5{slash}CSI_D1{slash}SDC2_D1)") (class "Default")
      (node (ref "RA19") (pin "7") (pinfunction "7_7") (pintype "passive"))
      (node (ref "U2") (pin "119") (pinfunction "PE5/CSI_D1/SDC2_D1_119") (pintype "output"))
    )
    (net (code "293") (name "Net-(U2-PE6{slash}CSI_D2{slash}SDC2_D2)") (class "Default")
      (node (ref "RA19") (pin "6") (pinfunction "6_6") (pintype "passive"))
      (node (ref "U2") (pin "120") (pinfunction "PE6/CSI_D2/SDC2_D2_120") (pintype "output"))
    )
    (net (code "294") (name "Net-(U2-PE7{slash}CSI_D3{slash}SDC2_D3)") (class "Default")
      (node (ref "RA19") (pin "5") (pinfunction "5_5") (pintype "passive"))
      (node (ref "U2") (pin "121") (pinfunction "PE7/CSI_D3/SDC2_D3_121") (pintype "output"))
    )
    (net (code "295") (name "Net-(U2-PE8{slash}CSI_D4{slash}SDC2_CMD)") (class "Default")
      (node (ref "RA20") (pin "8") (pinfunction "8_8") (pintype "passive"))
      (node (ref "U2") (pin "122") (pinfunction "PE8/CSI_D4/SDC2_CMD_122") (pintype "output"))
    )
    (net (code "296") (name "Net-(U2-PE9{slash}CSI_D5{slash}SDC2_CLK)") (class "Default")
      (node (ref "RA20") (pin "7") (pinfunction "7_7") (pintype "passive"))
      (node (ref "U2") (pin "123") (pinfunction "PE9/CSI_D5/SDC2_CLK_123") (pintype "output"))
    )
    (net (code "297") (name "Net-(U2-PE10{slash}CSI_D6{slash}UART1_TX)") (class "Default")
      (node (ref "RA20") (pin "6") (pinfunction "6_6") (pintype "passive"))
      (node (ref "U2") (pin "124") (pinfunction "PE10/CSI_D6/UART1_TX_124") (pintype "output"))
    )
    (net (code "298") (name "Net-(U2-PE11{slash}CSI_D6{slash}UART1_RX)") (class "Default")
      (node (ref "RA20") (pin "5") (pinfunction "5_5") (pintype "passive"))
      (node (ref "U2") (pin "125") (pinfunction "PE11/CSI_D6/UART1_RX_125") (pintype "output"))
    )
    (net (code "299") (name "Net-(U2-PF0{slash}SDC0_D1{slash}JTAG_TMS)") (class "Default")
      (node (ref "RA22") (pin "8") (pinfunction "8_8") (pintype "passive"))
      (node (ref "U2") (pin "107") (pinfunction "PF0/SDC0_D1/JTAG_TMS_107") (pintype "output"))
    )
    (net (code "300") (name "Net-(U2-PF1{slash}SDC0_D0{slash}JTAG_TDI)") (class "Default")
      (node (ref "RA22") (pin "7") (pinfunction "7_7") (pintype "passive"))
      (node (ref "U2") (pin "108") (pinfunction "PF1/SDC0_D0/JTAG_TDI_108") (pintype "output"))
    )
    (net (code "301") (name "Net-(U2-PF2{slash}SDC0_CLK{slash}UART0_TX)") (class "Default")
      (node (ref "RA22") (pin "6") (pinfunction "6_6") (pintype "passive"))
      (node (ref "U2") (pin "110") (pinfunction "PF2/SDC0_CLK/UART0_TX_110") (pintype "bidirectional"))
    )
    (net (code "302") (name "Net-(U2-PF3{slash}SDC0_CMD{slash}JTAG_TDO)") (class "Default")
      (node (ref "RA22") (pin "5") (pinfunction "5_5") (pintype "passive"))
      (node (ref "U2") (pin "111") (pinfunction "PF3/SDC0_CMD/JTAG_TDO_111") (pintype "bidirectional"))
    )
    (net (code "303") (name "Net-(U2-PF4{slash}SDC0_D3{slash}UART0_RX)") (class "Default")
      (node (ref "RA23") (pin "6") (pinfunction "6_6") (pintype "passive"))
      (node (ref "U2") (pin "112") (pinfunction "PF4/SDC0_D3/UART0_RX_112") (pintype "bidirectional"))
    )
    (net (code "304") (name "Net-(U2-PF5{slash}SDC0_D2{slash}JTAG_TCK)") (class "Default")
      (node (ref "RA23") (pin "5") (pinfunction "5_5") (pintype "passive"))
      (node (ref "U2") (pin "113") (pinfunction "PF5/SDC0_D2/JTAG_TCK_113") (pintype "bidirectional"))
    )
    (net (code "305") (name "Net-(U2-VMIC)") (class "Default")
      (node (ref "C91") (pin "1") (pintype "passive"))
      (node (ref "R27") (pin "1") (pintype "passive"))
      (node (ref "U2") (pin "85") (pinfunction "VMIC_85") (pintype "power_in"))
    )
    (net (code "306") (name "Net-(U2-VRA1)") (class "Default")
      (node (ref "C78") (pin "2") (pintype "passive"))
      (node (ref "U2") (pin "83") (pinfunction "VRA1_83") (pintype "power_in"))
    )
    (net (code "307") (name "Net-(U2-VRA2)") (class "Default")
      (node (ref "C79") (pin "2") (pintype "passive"))
      (node (ref "C80") (pin "1") (pintype "passive"))
      (node (ref "R21") (pin "2") (pintype "passive"))
      (node (ref "U2") (pin "82") (pinfunction "VRA2_82") (pintype "power_in"))
    )
    (net (code "308") (name "Net-(U2-VRP)") (class "Default")
      (node (ref "C76") (pin "2") (pintype "passive"))
      (node (ref "C77") (pin "1") (pintype "passive"))
      (node (ref "U2") (pin "80") (pinfunction "VRP_80") (pintype "power_in"))
    )
    (net (code "309") (name "Net-(U2-X24MIN)") (class "Default")
      (node (ref "C65") (pin "2") (pintype "passive"))
      (node (ref "U2") (pin "92") (pinfunction "X24MIN_92") (pintype "power_in"))
      (node (ref "XT1") (pin "2") (pinfunction "OUT_2") (pintype "passive"))
    )
    (net (code "310") (name "Net-(U2-X24MOUT)") (class "Default")
      (node (ref "C68") (pin "2") (pintype "passive"))
      (node (ref "U2") (pin "91") (pinfunction "X24MOUT_91") (pintype "power_in"))
      (node (ref "XT1") (pin "1") (pinfunction "IN_1") (pintype "passive"))
    )
    (net (code "311") (name "Net-(U3-BIAS)") (class "Default")
      (node (ref "R11") (pin "2") (pintype "passive"))
      (node (ref "U3") (pin "23") (pinfunction "BIAS_23") (pintype "bidirectional"))
    )
    (net (code "312") (name "Net-(U3-CHGLED)") (class "Default")
      (node (ref "R8") (pin "2") (pintype "passive"))
      (node (ref "U3") (pin "36") (pinfunction "CHGLED_36") (pintype "output"))
    )
    (net (code "313") (name "Net-(U3-CHSENSE)") (class "Default")
      (node (ref "C6") (pin "1") (pintype "passive"))
      (node (ref "C9") (pin "1") (pintype "passive"))
      (node (ref "L1") (pin "2") (pinfunction "2_2") (pintype "passive"))
      (node (ref "R4") (pin "1") (pintype "passive"))
      (node (ref "U3") (pin "43") (pinfunction "CHSENSE_43") (pintype "input"))
    )
    (net (code "314") (name "Net-(U3-LDO4)") (class "Default")
      (node (ref "C73") (pin "1") (pintype "passive"))
      (node (ref "U3") (pin "11") (pinfunction "LDO4_11") (pintype "output"))
    )
    (net (code "315") (name "Net-(U3-LX1)") (class "Default")
      (node (ref "L1") (pin "1") (pinfunction "1_1") (pintype "passive"))
      (node (ref "U3") (pin "45") (pinfunction "LX1_45") (pintype "bidirectional"))
    )
    (net (code "316") (name "Net-(U3-LX2)") (class "Default")
      (node (ref "L2") (pin "1") (pinfunction "1_1") (pintype "passive"))
      (node (ref "U3") (pin "8") (pinfunction "LX2_8") (pintype "bidirectional"))
    )
    (net (code "317") (name "Net-(U3-LX3)") (class "Default")
      (node (ref "L3") (pin "1") (pinfunction "1_1") (pintype "passive"))
      (node (ref "U3") (pin "15") (pinfunction "LX3_15") (pintype "bidirectional"))
    )
    (net (code "318") (name "Net-(U3-PWRON)") (class "Default")
      (node (ref "C75") (pin "2") (pintype "passive"))
      (node (ref "R12") (pin "2") (pintype "passive"))
      (node (ref "U3") (pin "47") (pinfunction "PWRON_47") (pintype "input"))
    )
    (net (code "319") (name "Net-(U3-TS)") (class "Default")
      (node (ref "R1") (pin "2") (pintype "passive"))
      (node (ref "U3") (pin "37") (pinfunction "TS_37") (pintype "input"))
    )
    (net (code "320") (name "Net-(U3-VREF)") (class "Default")
      (node (ref "C64") (pin "2") (pintype "passive"))
      (node (ref "U3") (pin "24") (pinfunction "VREF_24") (pintype "output"))
    )
    (net (code "321") (name "Net-(U4-OUT)") (class "Default")
      (node (ref "C72") (pin "2") (pintype "passive"))
      (node (ref "FB1") (pin "1") (pintype "passive"))
      (node (ref "R14") (pin "1") (pintype "passive"))
      (node (ref "U4") (pin "1") (pinfunction "OUT_1") (pintype "power_in"))
    )
    (net (code "322") (name "Net-(U5-RT)") (class "Default")
      (node (ref "R32") (pin "2") (pintype "passive"))
      (node (ref "U5") (pin "8") (pinfunction "RT_8") (pintype "passive"))
    )
    (net (code "323") (name "Net-(U6-EN)") (class "Default")
      (node (ref "R25") (pin "2") (pintype "passive"))
      (node (ref "U6") (pin "4") (pinfunction "EN_4") (pintype "input"))
    )
    (net (code "324") (name "Net-(U6-OUT)") (class "Default")
      (node (ref "C89") (pin "2") (pintype "passive"))
      (node (ref "FB2") (pin "1") (pintype "passive"))
      (node (ref "U6") (pin "1") (pinfunction "OUT_1") (pintype "power_in"))
    )
    (net (code "325") (name "Net-(U7-FB)") (class "Default")
      (node (ref "R37") (pin "1") (pintype "passive"))
      (node (ref "R42") (pin "2") (pintype "passive"))
      (node (ref "U7") (pin "5") (pinfunction "FB_5") (pintype "input"))
    )
    (net (code "326") (name "Net-(U7-SW)") (class "Default")
      (node (ref "L5") (pin "1") (pinfunction "1_1") (pintype "passive"))
      (node (ref "U7") (pin "3") (pinfunction "SW_3") (pintype "power_in"))
    )
    (net (code "327") (name "Net-(U10-FB)") (class "Default")
      (node (ref "R52") (pin "1") (pintype "passive"))
      (node (ref "R58") (pin "2") (pintype "passive"))
      (node (ref "U10") (pin "5") (pinfunction "FB_5") (pintype "input"))
    )
    (net (code "328") (name "Net-(U10-SW)") (class "Default")
      (node (ref "L6") (pin "1") (pinfunction "1_1") (pintype "passive"))
      (node (ref "U10") (pin "3") (pinfunction "SW_3") (pintype "power_in"))
    )
    (net (code "329") (name "Net-(U11-COMP)") (class "Default")
      (node (ref "R67") (pin "2") (pintype "passive"))
      (node (ref "U11") (pin "1") (pinfunction "COMP_1") (pintype "passive"))
    )
    (net (code "330") (name "Net-(U11-FB)") (class "Default")
      (node (ref "R66") (pin "1") (pintype "passive"))
      (node (ref "R68") (pin "2") (pintype "passive"))
      (node (ref "U11") (pin "2") (pinfunction "FB_2") (pintype "input"))
    )
    (net (code "331") (name "Net-(U11-SS)") (class "Default")
      (node (ref "C135") (pin "1") (pintype "passive"))
      (node (ref "U11") (pin "8") (pinfunction "SS_8") (pintype "input"))
    )
    (net (code "332") (name "Net-(U11-SW)") (class "Default")
      (node (ref "D3") (pin "A") (pinfunction "A_A") (pintype "passive"))
      (node (ref "L7") (pin "2") (pinfunction "2_2") (pintype "passive"))
      (node (ref "U11") (pin "5") (pinfunction "SW_5") (pintype "power_in"))
    )
    (net (code "333") (name "Net-(U12-COMP)") (class "Default")
      (node (ref "R70") (pin "2") (pintype "passive"))
      (node (ref "U12") (pin "1") (pinfunction "COMP_1") (pintype "passive"))
    )
    (net (code "334") (name "Net-(U12-FB)") (class "Default")
      (node (ref "R69") (pin "1") (pintype "passive"))
      (node (ref "R71") (pin "2") (pintype "passive"))
      (node (ref "U12") (pin "2") (pinfunction "FB_2") (pintype "input"))
    )
    (net (code "335") (name "Net-(U12-SS)") (class "Default")
      (node (ref "C142") (pin "1") (pintype "passive"))
      (node (ref "U12") (pin "8") (pinfunction "SS_8") (pintype "input"))
    )
    (net (code "336") (name "Net-(U13-COMP)") (class "Default")
      (node (ref "C149") (pin "2") (pintype "passive"))
      (node (ref "U13") (pin "5") (pinfunction "COMP_5") (pintype "passive"))
    )
    (net (code "337") (name "Net-(U13-SW)") (class "Default")
      (node (ref "D5") (pin "A") (pinfunction "A_A") (pintype "passive"))
      (node (ref "L9") (pin "2") (pinfunction "2_2") (pintype "passive"))
      (node (ref "U13") (pin "3") (pinfunction "SW_3") (pintype "power_in"))
    )
    (net (code "338") (name "VBAT") (class "Default")
      (node (ref "C10") (pin "1") (pintype "passive"))
      (node (ref "C157") (pin "2") (pintype "passive"))
      (node (ref "C6") (pin "2") (pintype "passive"))
      (node (ref "P6") (pin "1") (pinfunction "1_1") (pintype "passive"))
      (node (ref "R4") (pin "2") (pintype "passive"))
      (node (ref "U3") (pin "38") (pinfunction "BAT_38") (pintype "power_in"))
      (node (ref "U3") (pin "39") (pinfunction "BAT_39") (pintype "power_in"))
      (node (ref "U3") (pin "42") (pinfunction "BATSENSE_42") (pintype "input"))
    )
    (net (code "339") (name "unconnected-(J3-Pad2)") (class "Default")
      (node (ref "J3") (pin "2") (pinfunction "2_2") (pintype "power_in"))
    )
    (net (code "340") (name "unconnected-(J3-Pad4)") (class "Default")
      (node (ref "J3") (pin "4") (pinfunction "4_4") (pintype "power_in"))
    )
    (net (code "341") (name "unconnected-(J4-Pad35)") (class "Default")
      (node (ref "J4") (pin "35") (pinfunction "35_35") (pintype "passive"))
    )
    (net (code "342") (name "unconnected-(J5-Pad1)") (class "Default")
      (node (ref "J5") (pin "1") (pinfunction "1_1") (pintype "passive"))
    )
    (net (code "343") (name "unconnected-(J5-Pad4)") (class "Default")
      (node (ref "J5") (pin "4") (pinfunction "4_4") (pintype "passive"))
    )
    (net (code "344") (name "unconnected-(J5-Pad45)") (class "Default")
      (node (ref "J5") (pin "45") (pinfunction "45_45") (pintype "passive"))
    )
    (net (code "345") (name "unconnected-(J5-Pad49)") (class "Default")
      (node (ref "J5") (pin "49") (pinfunction "49_49") (pintype "passive"))
    )
    (net (code "346") (name "unconnected-(J5-Pad50)") (class "Default")
      (node (ref "J5") (pin "50") (pinfunction "50_50") (pintype "passive"))
    )
    (net (code "347") (name "unconnected-(J6-Pad5)") (class "Default")
      (node (ref "J6") (pin "5") (pinfunction "5_5") (pintype "passive"))
    )
    (net (code "348") (name "unconnected-(J6-Pad6)") (class "Default")
      (node (ref "J6") (pin "6") (pinfunction "6_6") (pintype "passive"))
    )
    (net (code "349") (name "unconnected-(J7-Pad4)") (class "Default")
      (node (ref "J7") (pin "4") (pinfunction "4_4") (pintype "power_in"))
    )
    (net (code "350") (name "unconnected-(P4-Pad28)") (class "Default")
      (node (ref "P4") (pin "28") (pinfunction "28_28") (pintype "passive"))
    )
    (net (code "351") (name "unconnected-(P4-Pad38)") (class "Default")
      (node (ref "P4") (pin "38") (pinfunction "38_38") (pintype "passive"))
    )
    (net (code "352") (name "unconnected-(U1C-NC-PadJ1)") (class "Default")
      (node (ref "U1") (pin "J1") (pinfunction "NC_J1") (pintype "passive"))
    )
    (net (code "353") (name "unconnected-(U1C-NC-PadJ9)") (class "Default")
      (node (ref "U1") (pin "J9") (pinfunction "NC_J9") (pintype "passive"))
    )
    (net (code "354") (name "unconnected-(U1C-NC-PadL1)") (class "Default")
      (node (ref "U1") (pin "L1") (pinfunction "NC_L1") (pintype "passive"))
    )
    (net (code "355") (name "unconnected-(U1C-NC-PadL9)") (class "Default")
      (node (ref "U1") (pin "L9") (pinfunction "NC_L9") (pintype "passive"))
    )
    (net (code "356") (name "unconnected-(U1C-NC-PadM7)") (class "Default")
      (node (ref "U1") (pin "M7") (pinfunction "NC_M7") (pintype "passive"))
    )
    (net (code "357") (name "unconnected-(U2-NC-Pad99)") (class "Default")
      (node (ref "U2") (pin "99") (pinfunction "NC_99") (pintype "power_in"))
    )
    (net (code "358") (name "unconnected-(U3-BACKUP-Pad30)") (class "Default")
      (node (ref "U3") (pin "30") (pinfunction "BACKUP_30") (pintype "bidirectional"))
    )
    (net (code "359") (name "unconnected-(U3-DC3SET-Pad29)") (class "Default")
      (node (ref "U3") (pin "29") (pinfunction "DC3SET_29") (pintype "input"))
    )
    (net (code "360") (name "unconnected-(U4-~{OC}-Pad3)") (class "Default")
      (node (ref "U4") (pin "3") (pinfunction "~{OC}_3") (pintype "open_collector"))
    )
    (net (code "361") (name "unconnected-(U5-EN-Pad7)") (class "Default")
      (node (ref "U5") (pin "7") (pinfunction "EN_7") (pintype "input"))
    )
    (net (code "362") (name "unconnected-(U6-~{OC}-Pad3)") (class "Default")
      (node (ref "U6") (pin "3") (pinfunction "~{OC}_3") (pintype "open_collector"))
    )
    (net (code "363") (name "unconnected-(U9-NC-Pad1)") (class "Default")
      (node (ref "U9") (pin "1") (pinfunction "NC_1") (pintype "passive"))
    )
    (net (code "364") (name "unconnected-(U9-NC-Pad2)") (class "Default")
      (node (ref "U9") (pin "2") (pinfunction "NC_2") (pintype "passive"))
    )
    (net (code "365") (name "unconnected-(U9-NC-Pad3)") (class "Default")
      (node (ref "U9") (pin "3") (pinfunction "NC_3") (pintype "passive"))
    )
    (net (code "366") (name "unconnected-(U9-NC-Pad4)") (class "Default")
      (node (ref "U9") (pin "4") (pinfunction "NC_4") (pintype "passive"))
    )
    (net (code "367") (name "unconnected-(U9-NC-Pad5)") (class "Default")
      (node (ref "U9") (pin "5") (pinfunction "NC_5") (pintype "passive"))
    )
    (net (code "368") (name "unconnected-(U9-NC-Pad11)") (class "Default")
      (node (ref "U9") (pin "11") (pinfunction "NC_11") (pintype "passive"))
    )
    (net (code "369") (name "unconnected-(U9-NC-Pad14)") (class "Default")
      (node (ref "U9") (pin "14") (pinfunction "NC_14") (pintype "passive"))
    )
    (net (code "370") (name "unconnected-(U9-NC-Pad15)") (class "Default")
      (node (ref "U9") (pin "15") (pinfunction "NC_15") (pintype "passive"))
    )
    (net (code "371") (name "unconnected-(U9-NC-Pad23)") (class "Default")
      (node (ref "U9") (pin "23") (pinfunction "NC_23") (pintype "passive"))
    )
    (net (code "372") (name "unconnected-(U9-NC-Pad24)") (class "Default")
      (node (ref "U9") (pin "24") (pinfunction "NC_24") (pintype "passive"))
    )
    (net (code "373") (name "unconnected-(U9-NC-Pad25)") (class "Default")
      (node (ref "U9") (pin "25") (pinfunction "NC_25") (pintype "passive"))
    )
    (net (code "374") (name "unconnected-(U9-NC-Pad26)") (class "Default")
      (node (ref "U9") (pin "26") (pinfunction "NC_26") (pintype "passive"))
    )
    (net (code "375") (name "unconnected-(U9-NC-Pad27)") (class "Default")
      (node (ref "U9") (pin "27") (pinfunction "NC_27") (pintype "passive"))
    )
    (net (code "376") (name "unconnected-(U9-NC-Pad28)") (class "Default")
      (node (ref "U9") (pin "28") (pinfunction "NC_28") (pintype "passive"))
    )
    (net (code "377") (name "unconnected-(U9-NC-Pad33)") (class "Default")
      (node (ref "U9") (pin "33") (pinfunction "NC_33") (pintype "passive"))
    )
    (net (code "378") (name "unconnected-(U9-NC-Pad34)") (class "Default")
      (node (ref "U9") (pin "34") (pinfunction "NC_34") (pintype "passive"))
    )
    (net (code "379") (name "unconnected-(U9-NC-Pad35)") (class "Default")
      (node (ref "U9") (pin "35") (pinfunction "NC_35") (pintype "passive"))
    )
    (net (code "380") (name "unconnected-(U9-NC-Pad39)") (class "Default")
      (node (ref "U9") (pin "39") (pinfunction "NC_39") (pintype "passive"))
    )
    (net (code "381") (name "unconnected-(U9-NC-Pad40)") (class "Default")
      (node (ref "U9") (pin "40") (pinfunction "NC_40") (pintype "passive"))
    )
    (net (code "382") (name "unconnected-(U9-NC-Pad45)") (class "Default")
      (node (ref "U9") (pin "45") (pinfunction "NC_45") (pintype "passive"))
    )
    (net (code "383") (name "unconnected-(U9-NC-Pad46)") (class "Default")
      (node (ref "U9") (pin "46") (pinfunction "NC_46") (pintype "passive"))
    )
    (net (code "384") (name "unconnected-(U9-NC-Pad47)") (class "Default")
      (node (ref "U9") (pin "47") (pinfunction "NC_47") (pintype "passive"))
    )
    (net (code "385") (name "unconnected-(U9-NC-Pad48)") (class "Default")
      (node (ref "U9") (pin "48") (pinfunction "NC_48") (pintype "passive"))
    )
    (net (code "386") (name "unconnected-(U9-NC{slash}CS2#-Pad10)") (class "Default")
      (node (ref "U9") (pin "10") (pinfunction "NC/CS2#_10") (pintype "passive"))
    )
    (net (code "387") (name "unconnected-(U9-NC{slash}DNU-Pad20)") (class "Default")
      (node (ref "U9") (pin "20") (pinfunction "NC/DNU_20") (pintype "passive"))
    )
    (net (code "388") (name "unconnected-(U9-NC{slash}DNU-Pad21)") (class "Default")
      (node (ref "U9") (pin "21") (pinfunction "NC/DNU_21") (pintype "passive"))
    )
    (net (code "389") (name "unconnected-(U9-NC{slash}DNU-Pad22)") (class "Default")
      (node (ref "U9") (pin "22") (pinfunction "NC/DNU_22") (pintype "passive"))
    )
    (net (code "390") (name "unconnected-(U9-NC{slash}PRE-Pad38)") (class "Default")
      (node (ref "U9") (pin "38") (pinfunction "NC/PRE_38") (pintype "passive"))
    )
    (net (code "391") (name "unconnected-(U9-NC{slash}R{slash}B2#-Pad6)") (class "Default")
      (node (ref "U9") (pin "6") (pinfunction "NC/R/B2#_6") (pintype "passive"))
    )
  )
)
